# MT-MONITOR_V1_0_0.net
KiCad netlist of a schematic drawn in Altium Designer
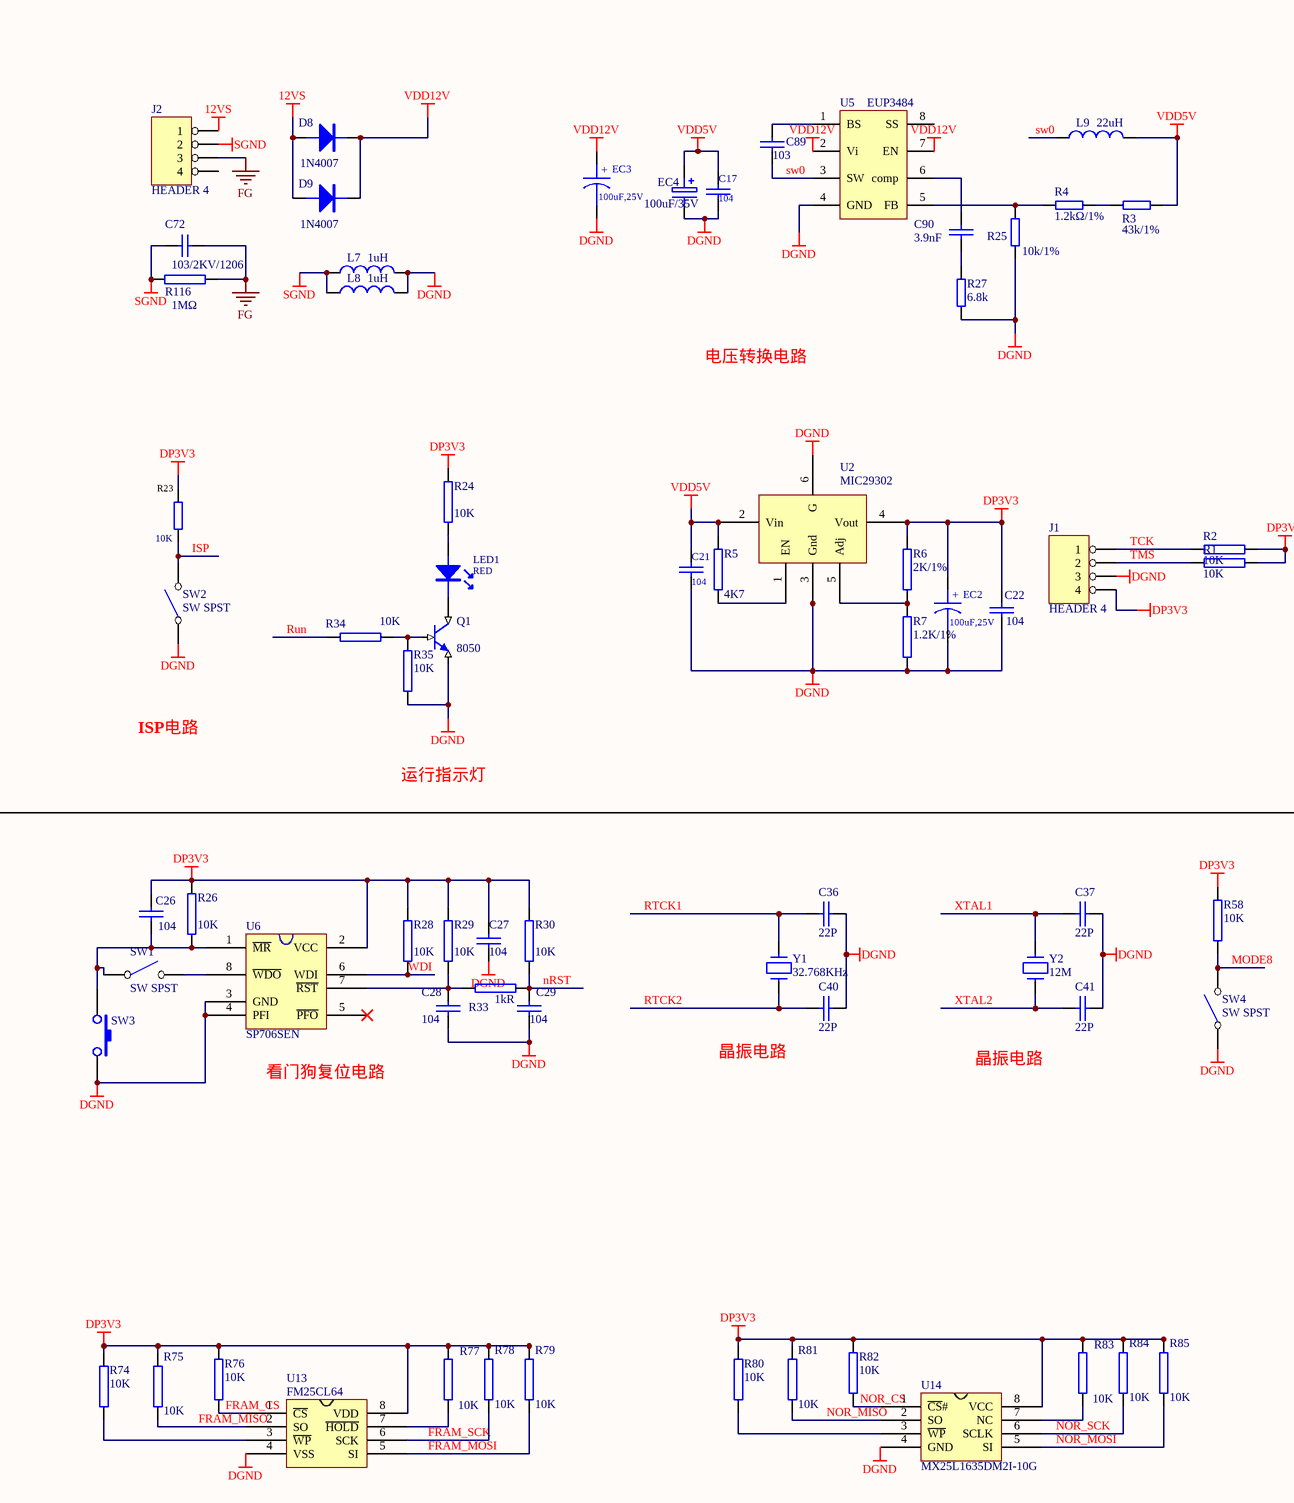
[diagram p0: MT-MONITOR V1.0.0.SchDoc, top left]
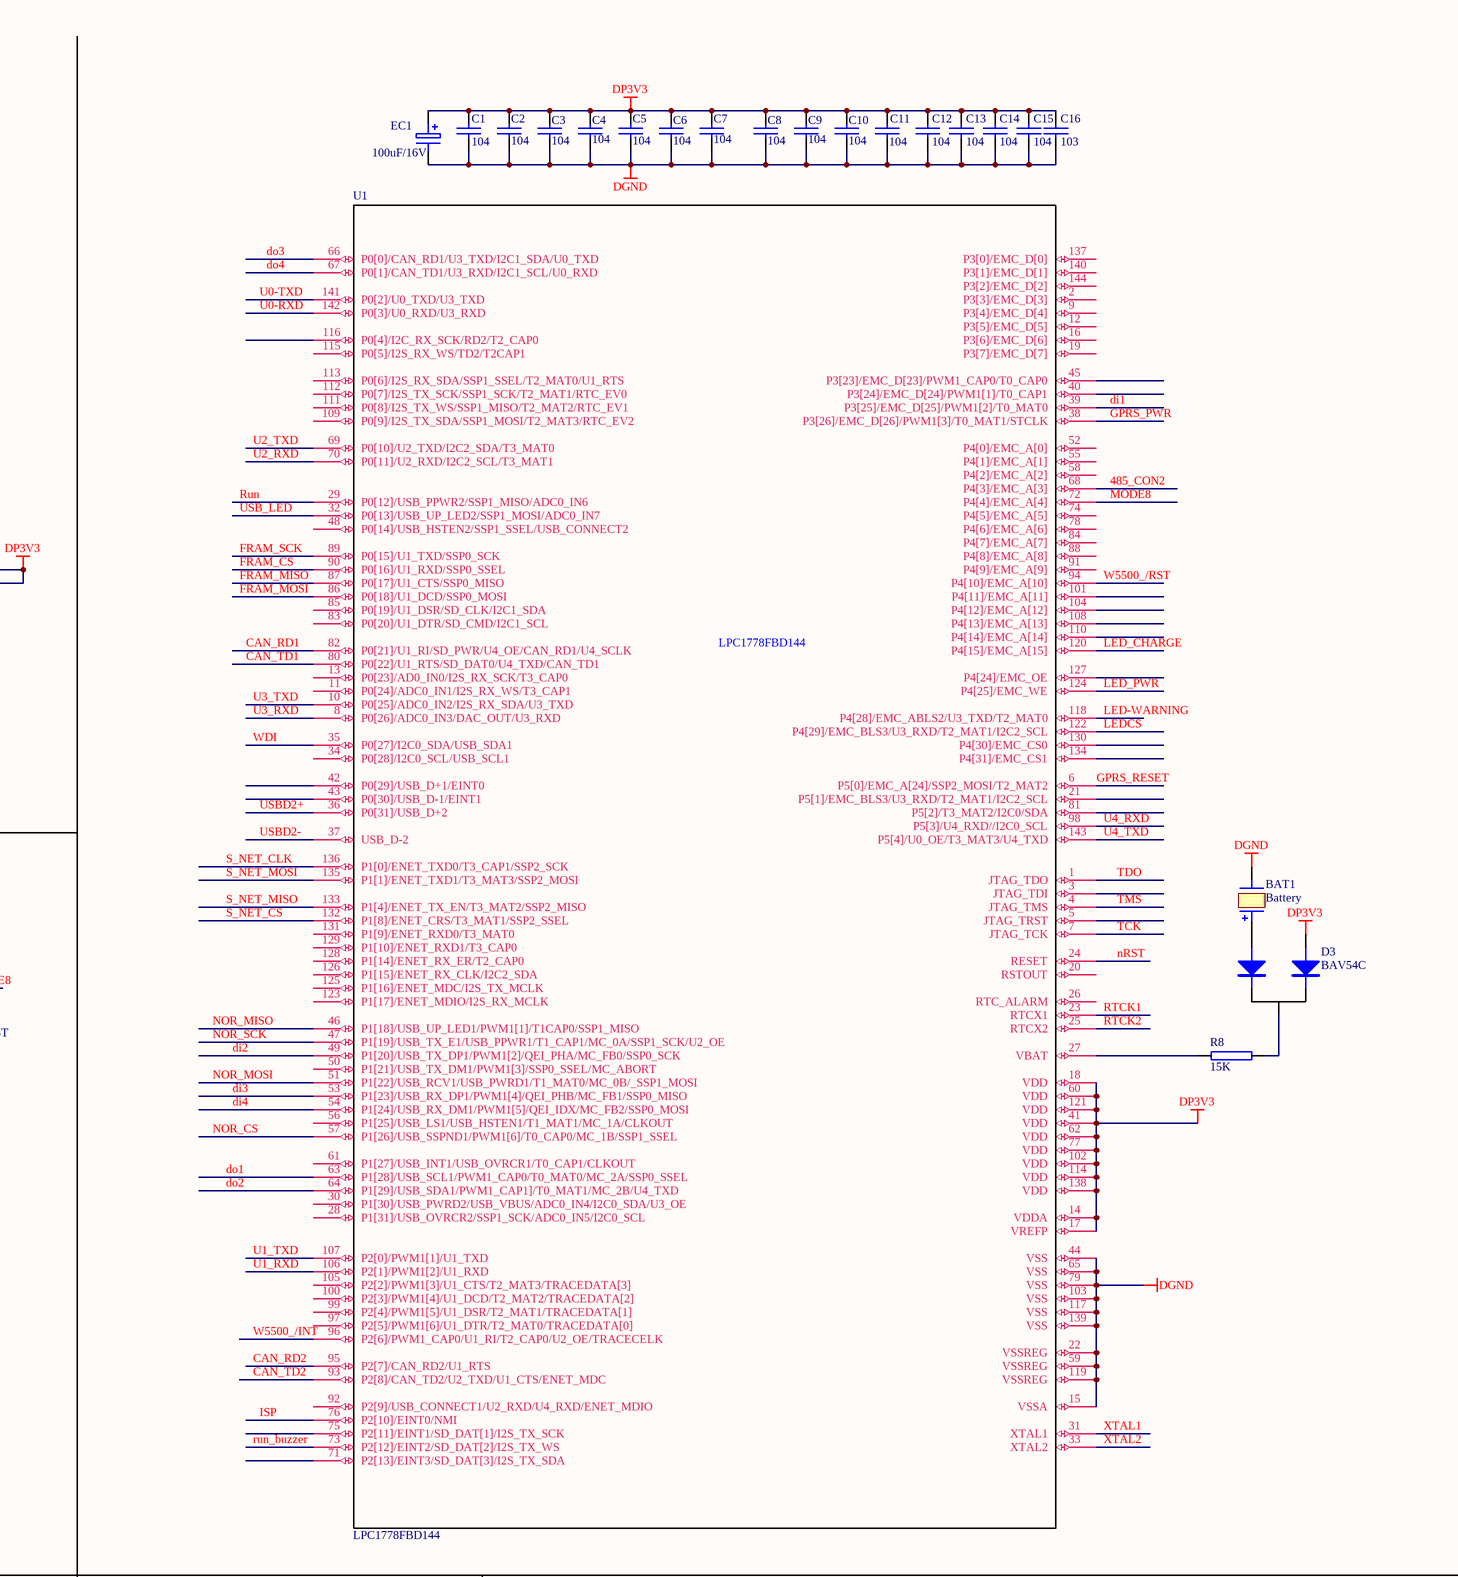
[diagram p1: MT-MONITOR V1.0.0.SchDoc, top middle]
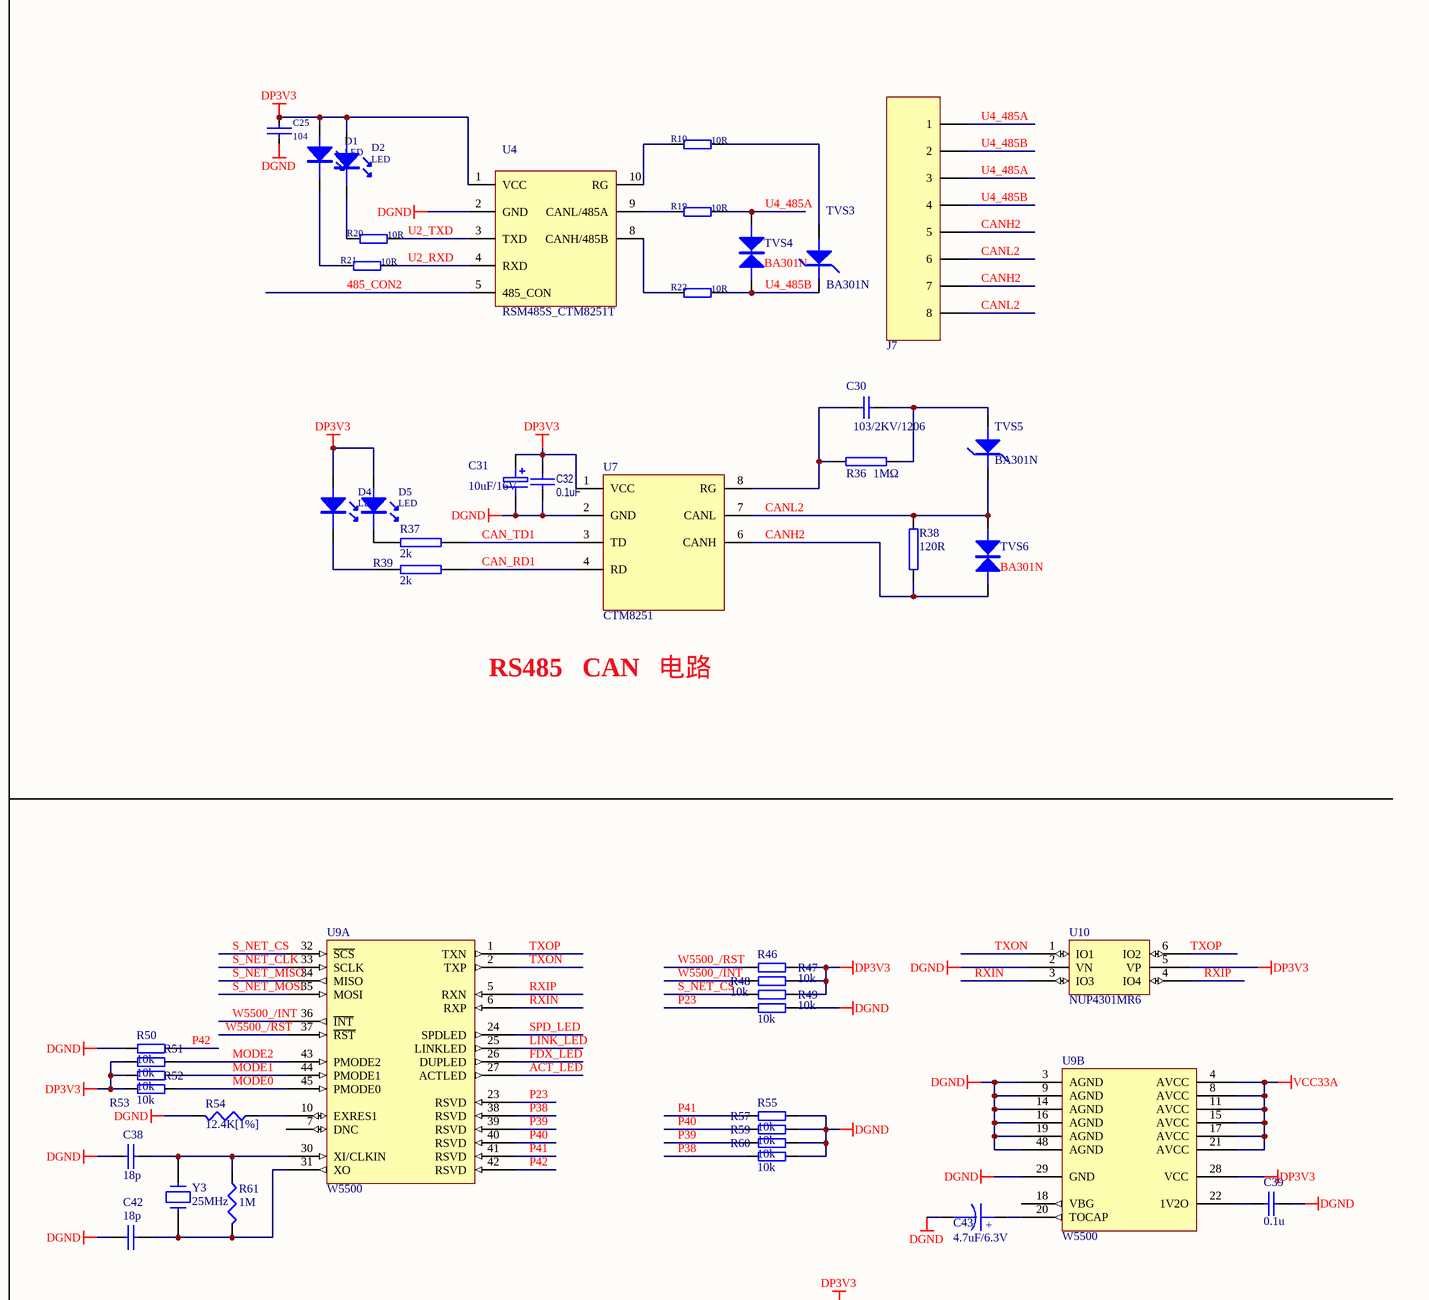
[diagram p2: MT-MONITOR V1.0.0.SchDoc, top right]
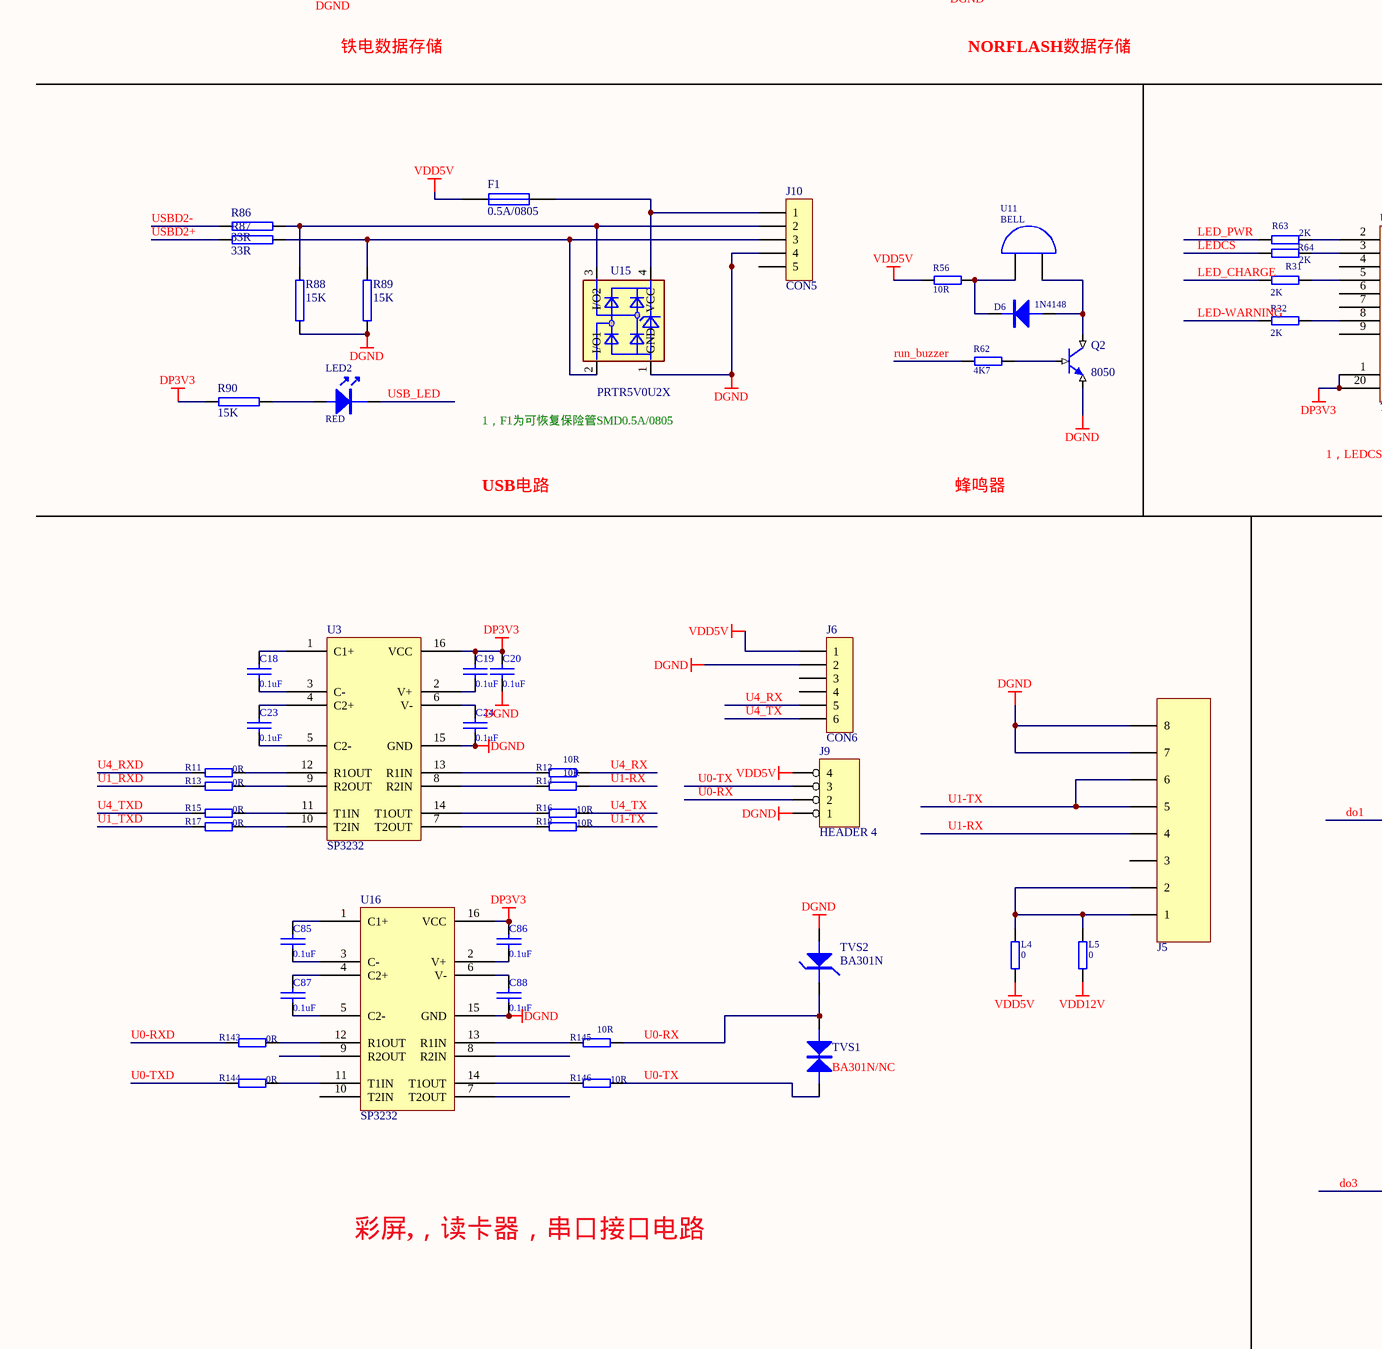
[diagram p3: MT-MONITOR V1.0.0.SchDoc, bottom left]
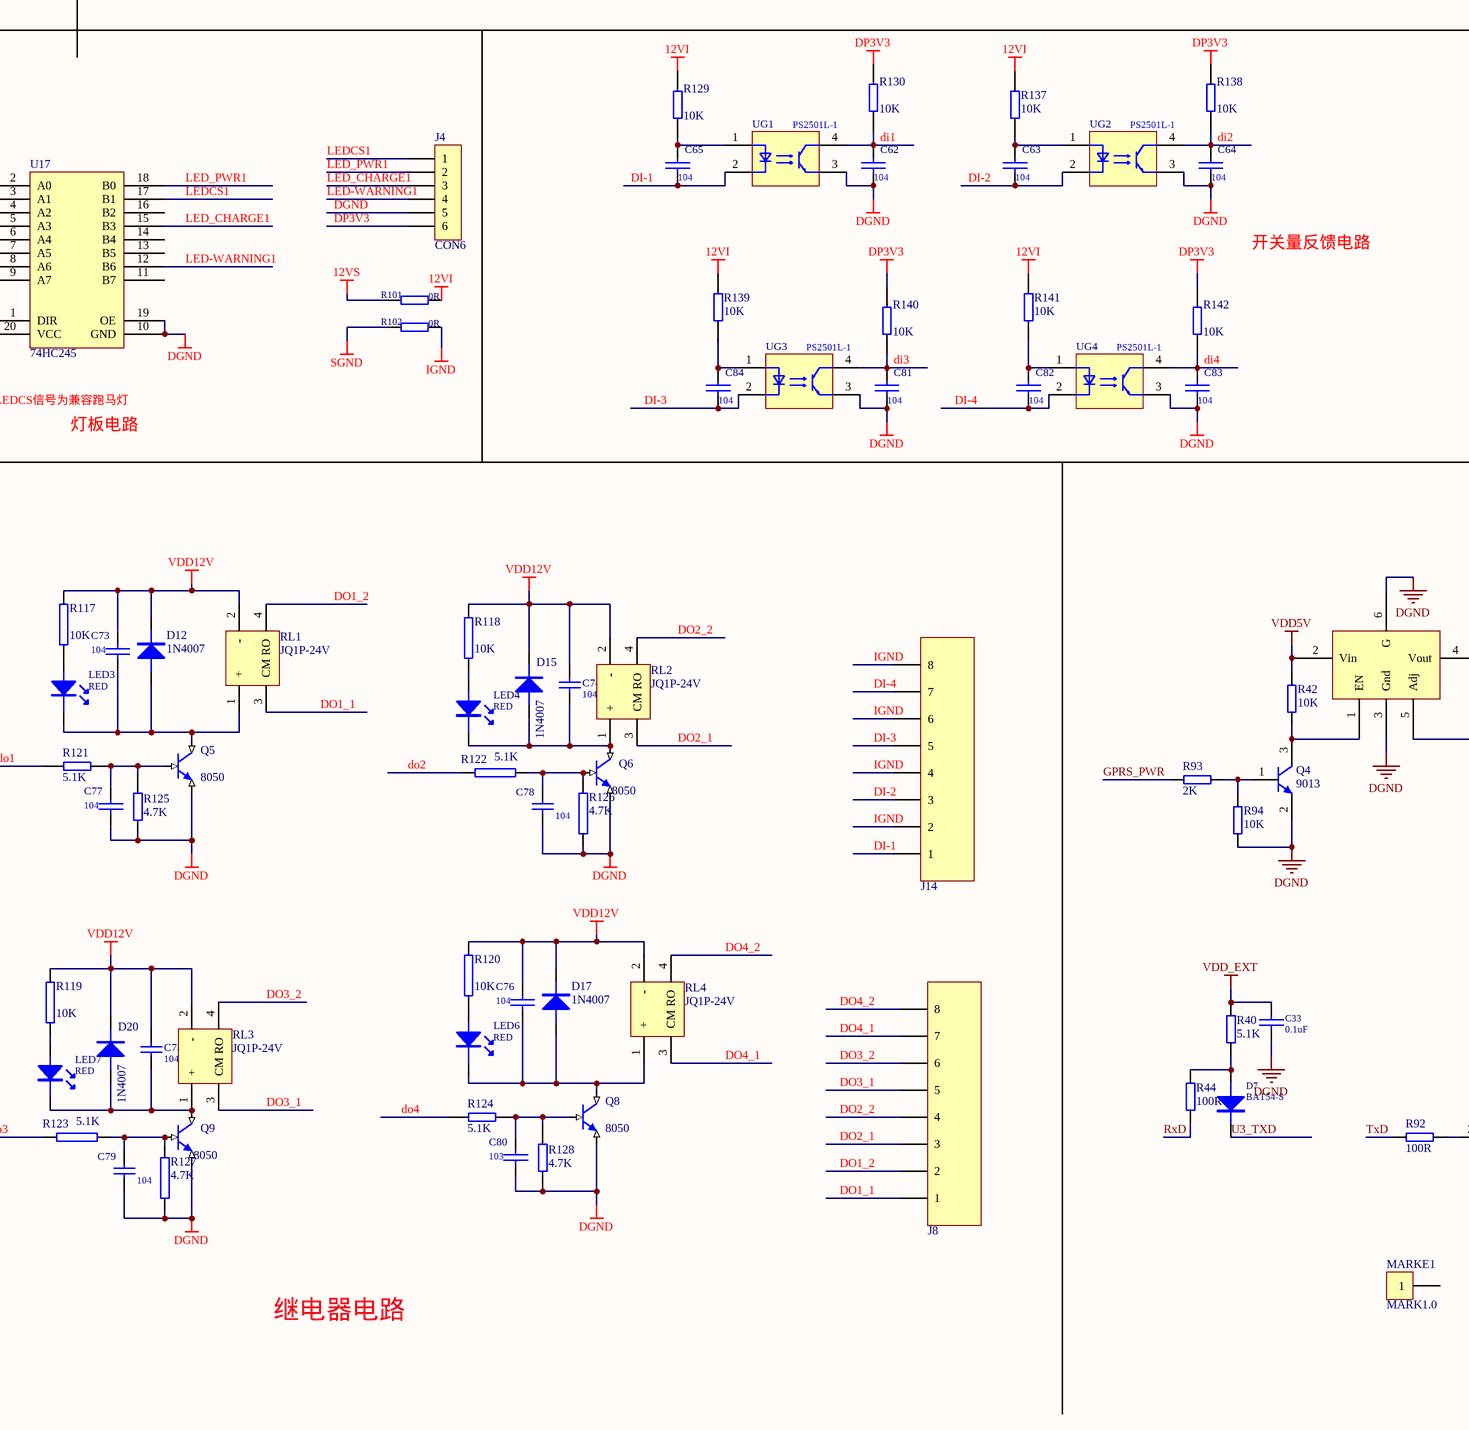
[diagram p4: MT-MONITOR V1.0.0.SchDoc, bottom middle]
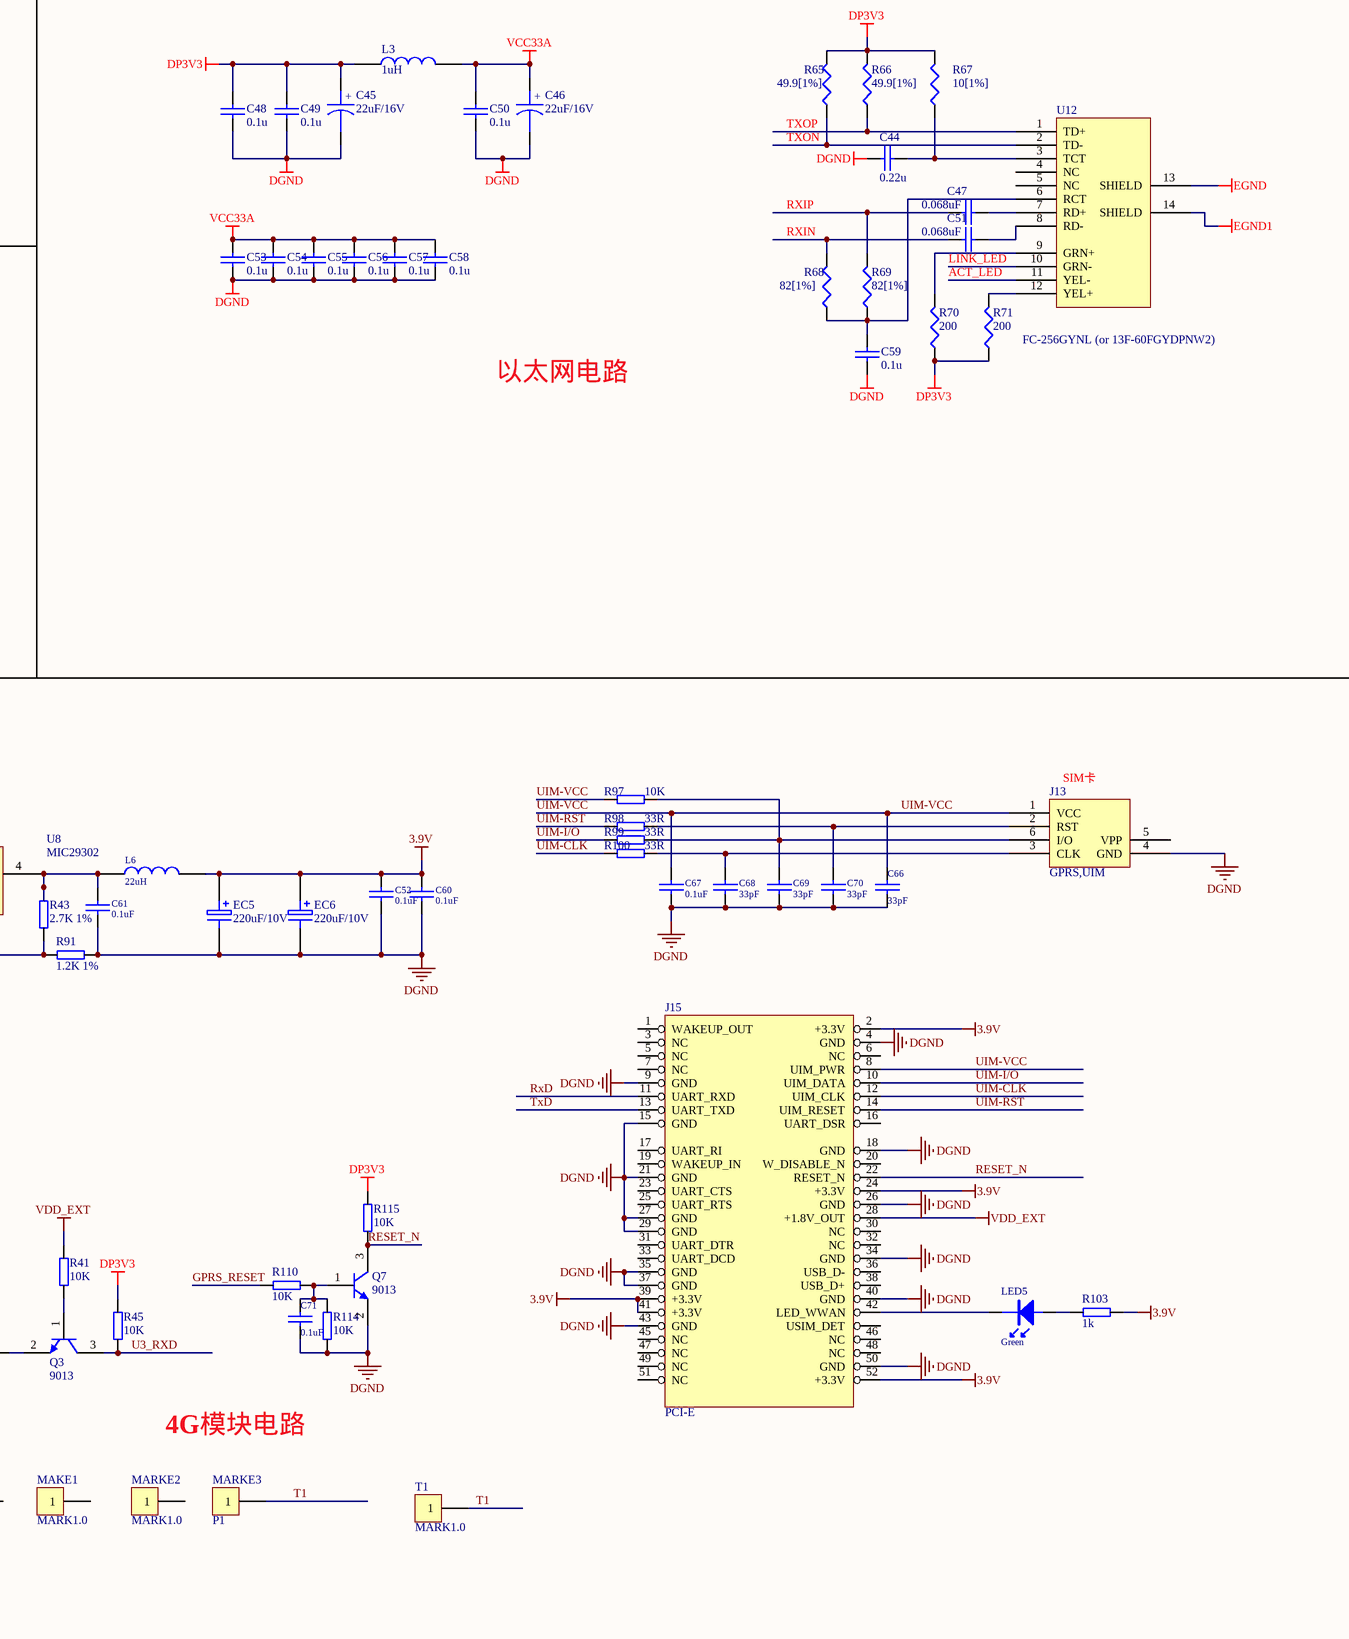
[diagram p5: MT-MONITOR V1.0.0.SchDoc, bottom right]

(export (version "E")
  (design (tool "Eeschema 10.0.6"))
  (components
    (comp (ref "BAT1") (value "Battery") (footprint "battery") (libsource (lib "MT") (part "Battery")))
    (comp (ref "C1") (value "104") (footprint "0603C") (libsource (lib "*") (part "CAP1")))
    (comp (ref "C2") (value "104") (footprint "0603C") (libsource (lib "*") (part "CAP1")))
    (comp (ref "C3") (value "104") (footprint "0603C") (libsource (lib "*") (part "CAP1")))
    (comp (ref "C4") (value "104") (footprint "0603C") (libsource (lib "*") (part "CAP1")))
    (comp (ref "C5") (value "104") (footprint "0603C") (libsource (lib "*") (part "CAP1")))
    (comp (ref "C6") (value "104") (footprint "0603C") (libsource (lib "*") (part "CAP1")))
    (comp (ref "C7") (value "104") (footprint "0603C") (libsource (lib "*") (part "CAP1")))
    (comp (ref "C8") (value "104") (footprint "0603C") (libsource (lib "*") (part "CAP1")))
    (comp (ref "C9") (value "104") (footprint "0603C") (libsource (lib "*") (part "CAP1")))
    (comp (ref "C10") (value "104") (footprint "0603C") (libsource (lib "*") (part "CAP1")))
    (comp (ref "C11") (value "104") (footprint "0603C") (libsource (lib "*") (part "CAP1")))
    (comp (ref "C12") (value "104") (footprint "0603C") (libsource (lib "") (part "CAP1_1")))
    (comp (ref "C13") (value "104") (footprint "0603C") (libsource (lib "*") (part "CAP1")))
    (comp (ref "C14") (value "104") (footprint "0603C") (libsource (lib "*") (part "CAP1")))
    (comp (ref "C15") (value "104") (footprint "0603C") (libsource (lib "*") (part "CAP1")))
    (comp (ref "C16") (value "103") (footprint "0603C") (libsource (lib "*") (part "CAP1")))
    (comp (ref "C17")
      (value "104")
      (footprint "0603C")
      (description "Capacitor")
      (libsource (lib "*") (part "CAP"))
    )
    (comp (ref "C18")
      (value "0.1uF")
      (footprint "0603C")
      (description "Capacitor")
      (libsource (lib "*") (part "CAP"))
    )
    (comp (ref "C19")
      (value "0.1uF")
      (footprint "0603C")
      (description "Capacitor")
      (libsource (lib "*") (part "CAP"))
    )
    (comp (ref "C20")
      (value "0.1uF")
      (footprint "0603C")
      (description "Capacitor")
      (libsource (lib "*") (part "CAP"))
    )
    (comp (ref "C21")
      (value "104")
      (footprint "0603C")
      (description "Capacitor")
      (libsource (lib "*") (part "CAP"))
    )
    (comp (ref "C22")
      (value "104")
      (footprint "0603C")
      (description "CAP")
      (libsource (lib "*") (part "CAP1"))
    )
    (comp (ref "C23")
      (value "0.1uF")
      (footprint "0603C")
      (description "Capacitor")
      (libsource (lib "*") (part "CAP"))
    )
    (comp (ref "C24")
      (value "0.1uF")
      (footprint "0603C")
      (description "Capacitor")
      (libsource (lib "*") (part "CAP"))
    )
    (comp (ref "C25") (value "104") (footprint "0603C") (libsource (lib "*") (part "CAP_1")))
    (comp (ref "C26")
      (value "104")
      (footprint "0603C")
      (description "CAP")
      (libsource (lib "*") (part "CAP1"))
    )
    (comp (ref "C27")
      (value "104")
      (footprint "0603C")
      (description "CAP")
      (libsource (lib "*") (part "CAP1"))
    )
    (comp (ref "C28")
      (value "104")
      (footprint "0603C")
      (description "CAP")
      (libsource (lib "*") (part "CAP1"))
    )
    (comp (ref "C29")
      (value "104")
      (footprint "0603C")
      (description "CAP")
      (libsource (lib "*") (part "CAP1"))
    )
    (comp (ref "C30")
      (value "103/2KV/1206")
      (footprint "1206C")
      (description "C0603")
      (fields (field (name "PUBLISHER") "*"))
      (libsource (lib "*") (part "0.1uF"))
    )
    (comp (ref "C31") (value "10uF/16V") (footprint "CA1206") (libsource (lib "*") (part "CAP2")))
    (comp (ref "C32")
      (value "0.1uF")
      (footprint "0603C")
      (description "Capacitor")
      (libsource (lib "*") (part "CAP"))
    )
    (comp (ref "C33")
      (value "0.1uF")
      (footprint "C0603")
      (description "CAP")
      (libsource (lib "MYSCHLIB") (part "CAP"))
    )
    (comp (ref "C36") (value "22P") (footprint "0603C") (libsource (lib "*") (part "CAP1")))
    (comp (ref "C37") (value "22P") (footprint "0603C") (libsource (lib "*") (part "CAP1")))
    (comp (ref "C38")
      (value "18p")
      (footprint "0603C")
      (description "Capacitor")
      (libsource (lib "*") (part "CAP"))
    )
    (comp (ref "C39")
      (value "0.1u")
      (footprint "0603C")
      (description "Capacitor")
      (libsource (lib "*") (part "CAP"))
    )
    (comp (ref "C40") (value "22P") (footprint "0603C") (libsource (lib "*") (part "CAP1")))
    (comp (ref "C41") (value "22P") (footprint "0603C") (libsource (lib "*") (part "CAP1")))
    (comp (ref "C42")
      (value "18p")
      (footprint "0603C")
      (description "Capacitor")
      (libsource (lib "*") (part "CAP"))
    )
    (comp (ref "C43")
      (value "4.7uF/6.3V")
      (footprint "CA1206")
      (description "Capacitor")
      (libsource (lib "*") (part "CAPACITOR POL"))
    )
    (comp (ref "C44")
      (value "0.22u")
      (footprint "0603C")
      (description "Capacitor")
      (libsource (lib "*") (part "CAP"))
    )
    (comp (ref "C45")
      (value "22uF/16V")
      (footprint "CA1206")
      (description "Capacitor")
      (libsource (lib "*") (part "CAPACITOR POL"))
    )
    (comp (ref "C46")
      (value "22uF/16V")
      (footprint "CA1206")
      (description "Capacitor")
      (libsource (lib "*") (part "CAPACITOR POL"))
    )
    (comp (ref "C47")
      (value "0.068uF")
      (footprint "0603C")
      (description "Capacitor")
      (libsource (lib "*") (part "CAP"))
    )
    (comp (ref "C48")
      (value "0.1u")
      (footprint "0603C")
      (description "Capacitor")
      (libsource (lib "*") (part "CAP"))
    )
    (comp (ref "C49")
      (value "0.1u")
      (footprint "0603C")
      (description "Capacitor")
      (libsource (lib "*") (part "CAP"))
    )
    (comp (ref "C50")
      (value "0.1u")
      (footprint "0603C")
      (description "Capacitor")
      (libsource (lib "*") (part "CAP"))
    )
    (comp (ref "C51")
      (value "0.068uF")
      (footprint "0603C")
      (description "Capacitor")
      (libsource (lib "*") (part "CAP"))
    )
    (comp (ref "C52")
      (value "0.1uF")
      (footprint "C0603")
      (description "CAP")
      (libsource (lib "MYSCHLIB") (part "CAP"))
    )
    (comp (ref "C53")
      (value "0.1u")
      (footprint "0603C")
      (description "Capacitor")
      (libsource (lib "*") (part "CAP"))
    )
    (comp (ref "C54")
      (value "0.1u")
      (footprint "0603C")
      (description "Capacitor")
      (libsource (lib "*") (part "CAP"))
    )
    (comp (ref "C55")
      (value "0.1u")
      (footprint "0603C")
      (description "Capacitor")
      (libsource (lib "*") (part "CAP"))
    )
    (comp (ref "C56")
      (value "0.1u")
      (footprint "0603C")
      (description "Capacitor")
      (libsource (lib "*") (part "CAP"))
    )
    (comp (ref "C57")
      (value "0.1u")
      (footprint "0603C")
      (description "Capacitor")
      (libsource (lib "*") (part "CAP"))
    )
    (comp (ref "C58")
      (value "0.1u")
      (footprint "0603C")
      (description "Capacitor")
      (libsource (lib "*") (part "CAP"))
    )
    (comp (ref "C59")
      (value "0.1u")
      (footprint "0603C")
      (description "Capacitor")
      (libsource (lib "*") (part "CAP"))
    )
    (comp (ref "C60")
      (value "0.1uF")
      (footprint "C0603")
      (description "CAP")
      (libsource (lib "MYSCHLIB") (part "CAP"))
    )
    (comp (ref "C61")
      (value "0.1uF")
      (footprint "C0603")
      (description "CAP")
      (libsource (lib "MYSCHLIB") (part "CAP"))
    )
    (comp (ref "C62")
      (value "104")
      (footprint "0603C")
      (description "Capacitor")
      (libsource (lib "*") (part "CAP"))
    )
    (comp (ref "C63")
      (value "104")
      (footprint "0603C")
      (description "Capacitor")
      (libsource (lib "*") (part "CAP"))
    )
    (comp (ref "C64")
      (value "104")
      (footprint "0603C")
      (description "Capacitor")
      (libsource (lib "*") (part "CAP"))
    )
    (comp (ref "C65")
      (value "104")
      (footprint "0603C")
      (description "Capacitor")
      (libsource (lib "*") (part "CAP"))
    )
    (comp (ref "C66")
      (value "33pF")
      (footprint "C0603")
      (description "CAP")
      (libsource (lib "MYSCHLIB") (part "CAP"))
    )
    (comp (ref "C67")
      (value "0.1uF")
      (footprint "C0603")
      (description "CAP")
      (libsource (lib "MYSCHLIB") (part "CAP"))
    )
    (comp (ref "C68")
      (value "33pF")
      (footprint "C0603")
      (description "CAP")
      (libsource (lib "MYSCHLIB") (part "CAP"))
    )
    (comp (ref "C69")
      (value "33pF")
      (footprint "C0603")
      (description "CAP")
      (libsource (lib "MYSCHLIB") (part "CAP"))
    )
    (comp (ref "C70")
      (value "33pF")
      (footprint "C0603")
      (description "CAP")
      (libsource (lib "MYSCHLIB") (part "CAP"))
    )
    (comp (ref "C71")
      (value "0.1uF")
      (footprint "C0603")
      (description "CAP")
      (libsource (lib "MYSCHLIB") (part "CAP"))
    )
    (comp (ref "C72")
      (value "103/2KV/1206")
      (footprint "1206C")
      (description "C0603")
      (fields (field (name "PUBLISHER") "*"))
      (libsource (lib "*") (part "0.1uF"))
    )
    (comp (ref "C73")
      (value "104")
      (footprint "0603C")
      (description "Capacitor")
      (libsource (lib "*") (part "CAP"))
    )
    (comp (ref "C74")
      (value "104")
      (footprint "0603C")
      (description "Capacitor")
      (fields (field (name "PUBLISHER") "*"))
      (libsource (lib "*") (part "Cap"))
    )
    (comp (ref "C75")
      (value "104")
      (footprint "0603C")
      (description "Capacitor")
      (fields (field (name "PUBLISHER") "*"))
      (libsource (lib "*") (part "Cap"))
    )
    (comp (ref "C76")
      (value "104")
      (footprint "0603C")
      (description "Capacitor")
      (libsource (lib "*") (part "CAP"))
    )
    (comp (ref "C77")
      (value "104")
      (footprint "0603C")
      (description "Capacitor")
      (libsource (lib "*") (part "CAP"))
    )
    (comp (ref "C78")
      (value "104")
      (footprint "0603C")
      (description "Capacitor")
      (fields (field (name "PUBLISHER") "*"))
      (libsource (lib "*") (part "Cap"))
    )
    (comp (ref "C79")
      (value "104")
      (footprint "0603C")
      (description "Capacitor")
      (fields (field (name "PUBLISHER") "*"))
      (libsource (lib "*") (part "Cap"))
    )
    (comp (ref "C80")
      (value "103")
      (footprint "0603C")
      (description "Capacitor")
      (libsource (lib "*") (part "CAP"))
    )
    (comp (ref "C81")
      (value "104")
      (footprint "0603C")
      (description "Capacitor")
      (libsource (lib "*") (part "CAP"))
    )
    (comp (ref "C82")
      (value "104")
      (footprint "0603C")
      (description "Capacitor")
      (libsource (lib "*") (part "CAP"))
    )
    (comp (ref "C83")
      (value "104")
      (footprint "0603C")
      (description "Capacitor")
      (libsource (lib "*") (part "CAP"))
    )
    (comp (ref "C84")
      (value "104")
      (footprint "0603C")
      (description "Capacitor")
      (libsource (lib "*") (part "CAP"))
    )
    (comp (ref "C85")
      (value "0.1uF")
      (footprint "0603C")
      (description "Capacitor")
      (libsource (lib "*") (part "CAP"))
    )
    (comp (ref "C86")
      (value "0.1uF")
      (footprint "0603C")
      (description "Capacitor")
      (libsource (lib "*") (part "CAP"))
    )
    (comp (ref "C87")
      (value "0.1uF")
      (footprint "0603C")
      (description "Capacitor")
      (libsource (lib "*") (part "CAP"))
    )
    (comp (ref "C88")
      (value "0.1uF")
      (footprint "0603C")
      (description "Capacitor")
      (libsource (lib "*") (part "CAP"))
    )
    (comp (ref "C89") (value "103") (footprint "0603C") (libsource (lib "*") (part "CAP")))
    (comp (ref "C90") (value "3.9nF") (footprint "0603C") (libsource (lib "*") (part "CAP")))
    (comp (ref "D1") (value "LED") (footprint "D0805") (libsource (lib "*") (part "LED")))
    (comp (ref "D2") (value "LED") (footprint "D0805") (libsource (lib "*") (part "LED")))
    (comp (ref "D3") (value "BAV54C") (footprint "SOT23") (libsource (lib "MT") (part "BAV54C")))
    (comp (ref "D4") (value "LED") (footprint "D0805") (libsource (lib "*") (part "LED")))
    (comp (ref "D5") (value "LED") (footprint "D0805") (libsource (lib "*") (part "LED")))
    (comp (ref "D6") (value "1N4148") (footprint "1206D") (libsource (lib "*") (part "DIODE")))
    (comp (ref "D7") (value "BAT54-S") (footprint "SOT23") (libsource (lib "MYSCHLIB") (part "DIODE")))
    (comp (ref "D8") (value "1N4007") (footprint "1206D") (libsource (lib "*") (part "DIODE")))
    (comp (ref "D9") (value "1N4007") (footprint "1206D") (libsource (lib "*") (part "DIODE")))
    (comp (ref "D12") (value "1N4007") (footprint "1206D") (libsource (lib "*") (part "DIODE")))
    (comp (ref "D15") (value "1N4007") (footprint "1206D") (libsource (lib "*") (part "DIODE")))
    (comp (ref "D17") (value "1N4007") (footprint "1206D") (libsource (lib "*") (part "DIODE")))
    (comp (ref "D20") (value "1N4007") (footprint "1206D") (libsource (lib "*") (part "DIODE")))
    (comp (ref "EC1") (value "100uF/16V") (footprint "C100UF16VEJ") (libsource (lib "*") (part "CAP2")))
    (comp (ref "EC2")
      (value "100uF,25V")
      (footprint "C100UF16VEJ")
      (description "Capacitor")
      (libsource (lib "*") (part "CAPACITOR POL"))
    )
    (comp (ref "EC3")
      (value "100uF,25V")
      (footprint "C100UF16VEJ")
      (description "Capacitor")
      (libsource (lib "*") (part "CAPACITOR POL"))
    )
    (comp (ref "EC4") (value "100uF/35V") (footprint "C100UF16VEJ") (libsource (lib "*") (part "CAP2")))
    (comp (ref "EC5")
      (value "220uF/10V")
      (footprint "C100UF16V")
      (libsource (lib "MYSCHLIB") (part "ELECTRO2"))
    )
    (comp (ref "EC6")
      (value "220uF/10V")
      (footprint "C100UF16V")
      (libsource (lib "MYSCHLIB") (part "ELECTRO2"))
    )
    (comp (ref "F1")
      (value "0.5A/0805")
      (footprint "0805R")
      (description "Fuse")
      (libsource (lib "EasyCortex M3-1752") (part "FUSE1"))
    )
    (comp (ref "J1")
      (value "HEADER 4")
      (footprint "COM-2.54mm-90")
      (description "4 Pin Header")
      (libsource (lib "") (part "4 HEADER_1"))
    )
    (comp (ref "J2")
      (value "HEADER 4")
      (footprint "KF2EDG-4P-3.81mm")
      (description "4 Pin Header")
      (libsource (lib "") (part "4 HEADER_1"))
    )
    (comp (ref "J4")
      (value "CON6")
      (footprint "CON6-2.54mm-90")
      (description "Connector")
      (libsource (lib "*") (part "CON6"))
    )
    (comp (ref "J5") (value "CON8") (footprint "HY-8A-2.00mm") (libsource (lib "ueee20160531") (part "CON8")))
    (comp (ref "J6")
      (value "CON6")
      (footprint "CON6-2.54mm-90")
      (description "Connector")
      (libsource (lib "*") (part "CON6"))
    )
    (comp (ref "J7") (value "CON8") (footprint "KF2EDG-8P-3.81mm") (libsource (lib "直流原理图库") (part "CON8")))
    (comp (ref "J8") (value "CON8") (footprint "KF2EDG-8P-3.81mm") (libsource (lib "") (part "CON8_1")))
    (comp (ref "J9")
      (value "HEADER 4")
      (footprint "KF2EDG-4P-3.81mm")
      (description "4 Pin Header")
      (libsource (lib "直流原理图库") (part "4 HEADER"))
    )
    (comp (ref "J10")
      (value "CON5")
      (footprint "USB-A")
      (description "Connector")
      (libsource (lib "*") (part "CON5"))
    )
    (comp (ref "J13") (value "GPRS,UIM") (footprint "SIM6-AUTO") (libsource (lib "MYSCHLIB") (part "UIM6")))
    (comp (ref "J14") (value "CON8") (footprint "KF2EDG-8P-3.81mm") (libsource (lib "") (part "CON8_1")))
    (comp (ref "J15") (value "PCI-E") (footprint "MC2716") (libsource (lib "直流原理图库") (part "PCI-E")))
    (comp (ref "L3") (value "1uH") (footprint "0805R") (libsource (lib "") (part "INDUCTOR_1")))
    (comp (ref "L4")
      (value "0")
      (footprint "CON02_2.54")
      (description "RES")
      (libsource (lib "*") (part "RES-1"))
    )
    (comp (ref "L5")
      (value "0")
      (footprint "CON02_2.54")
      (description "RES")
      (libsource (lib "*") (part "RES-1"))
    )
    (comp (ref "L6") (value "22uH") (footprint "LC7*7*3_L") (libsource (lib "MYSCHLIB") (part "INDUCTOR")))
    (comp (ref "L7") (value "1uH") (footprint "1206R") (libsource (lib "*") (part "INDUCTOR")))
    (comp (ref "L8") (value "1uH") (footprint "1206R") (libsource (lib "*") (part "INDUCTOR")))
    (comp (ref "L9") (value "22uH") (footprint "LC7*7*3_L") (libsource (lib "*") (part "INDUCTOR")))
    (comp (ref "LED1") (value "RED") (footprint "D0805") (libsource (lib "*") (part "LED")))
    (comp (ref "LED2") (value "RED") (footprint "D0805") (libsource (lib "*") (part "LED")))
    (comp (ref "LED3") (value "RED") (footprint "D0805") (libsource (lib "*") (part "LED")))
    (comp (ref "LED4") (value "RED") (footprint "D0805") (libsource (lib "*") (part "LED")))
    (comp (ref "LED5") (value "Green") (footprint "D0805") (libsource (lib "MYSCHLIB") (part "LED")))
    (comp (ref "LED6") (value "RED") (footprint "D0805") (libsource (lib "*") (part "LED")))
    (comp (ref "LED7") (value "RED") (footprint "D0805") (libsource (lib "*") (part "LED")))
    (comp (ref "MAKE1")
      (value "MARK1.0")
      (footprint "MARK1.0")
      (description "Connector")
      (libsource (lib "*") (part "CON1"))
    )
    (comp (ref "MARKE1")
      (value "MARK1.0")
      (footprint "MARK1.0")
      (description "Connector")
      (libsource (lib "*") (part "CON1"))
    )
    (comp (ref "MARKE2")
      (value "MARK1.0")
      (footprint "MARK1.0")
      (description "Connector")
      (libsource (lib "*") (part "CON1"))
    )
    (comp (ref "MARKE3")
      (value "P1")
      (footprint "IPEX")
      (description "Connector")
      (libsource (lib "*") (part "CON1"))
    )
    (comp (ref "Q1") (value "8050") (footprint "SOT23") (libsource (lib "*") (part "NPN")))
    (comp (ref "Q2") (value "8050") (footprint "SOT23") (libsource (lib "*") (part "NPN")))
    (comp (ref "Q3") (value "9013") (footprint "SOT23") (libsource (lib "MYSCHLIB") (part "NPN")))
    (comp (ref "Q4") (value "9013") (footprint "SOT23") (libsource (lib "MYSCHLIB") (part "NPN")))
    (comp (ref "Q5") (value "8050") (footprint "SOT23") (libsource (lib "*") (part "NPN")))
    (comp (ref "Q6") (value "8050") (footprint "SOT23") (libsource (lib "*") (part "NPN")))
    (comp (ref "Q7") (value "9013") (footprint "SOT23") (libsource (lib "MYSCHLIB") (part "NPN")))
    (comp (ref "Q8") (value "8050") (footprint "SOT23") (libsource (lib "*") (part "NPN")))
    (comp (ref "Q9") (value "8050") (footprint "SOT23") (libsource (lib "*") (part "NPN")))
    (comp (ref "R1") (value "10K") (footprint "0603R") (libsource (lib "*") (part "RES1")))
    (comp (ref "R2") (value "10K") (footprint "0603R") (libsource (lib "*") (part "RES1")))
    (comp (ref "R3") (value "43k/1%") (footprint "0603R") (libsource (lib "*") (part "R_S")))
    (comp (ref "R4") (value "1.2kΩ/1%") (footprint "0603R") (libsource (lib "*") (part "R_S")))
    (comp (ref "R5") (value "4K7") (footprint "0603R") (libsource (lib "*") (part "RES1")))
    (comp (ref "R6") (value "2K/1%") (footprint "0603R") (libsource (lib "*") (part "RES1")))
    (comp (ref "R7") (value "1.2K/1%") (footprint "0603R") (libsource (lib "*") (part "RES1")))
    (comp (ref "R8") (value "15K") (footprint "0603R") (libsource (lib "*") (part "RES1")))
    (comp (ref "R10")
      (value "10R")
      (footprint "0603R")
      (description "RES")
      (libsource (lib "*") (part "RES-1"))
    )
    (comp (ref "R11")
      (value "0R")
      (footprint "0603R")
      (description "RES")
      (libsource (lib "*") (part "RES-1"))
    )
    (comp (ref "R12")
      (value "10R")
      (footprint "0603R")
      (description "RES")
      (libsource (lib "*") (part "RES-1"))
    )
    (comp (ref "R13")
      (value "0R")
      (footprint "0603R")
      (description "RES")
      (libsource (lib "*") (part "RES-1"))
    )
    (comp (ref "R14")
      (value "10R")
      (footprint "0603R")
      (description "RES")
      (libsource (lib "*") (part "RES-1"))
    )
    (comp (ref "R15")
      (value "0R")
      (footprint "0603R")
      (description "RES")
      (libsource (lib "*") (part "RES-1"))
    )
    (comp (ref "R16")
      (value "10R")
      (footprint "0603R")
      (description "RES")
      (libsource (lib "*") (part "RES-1"))
    )
    (comp (ref "R17")
      (value "0R")
      (footprint "0603R")
      (description "RES")
      (libsource (lib "*") (part "RES-1"))
    )
    (comp (ref "R18")
      (value "10R")
      (footprint "0603R")
      (description "RES")
      (libsource (lib "*") (part "RES-1"))
    )
    (comp (ref "R19")
      (value "10R")
      (footprint "0603R")
      (description "RES")
      (libsource (lib "*") (part "RES-1"))
    )
    (comp (ref "R20")
      (value "10R")
      (footprint "0603R")
      (description "RES")
      (libsource (lib "*") (part "RES-1"))
    )
    (comp (ref "R21")
      (value "10R")
      (footprint "0603R")
      (description "RES")
      (libsource (lib "*") (part "RES-1"))
    )
    (comp (ref "R22")
      (value "10R")
      (footprint "0603R")
      (description "RES")
      (libsource (lib "*") (part "RES-1"))
    )
    (comp (ref "R23")
      (value "10K")
      (footprint "0603R")
      (description "RES")
      (libsource (lib "*") (part "RES-1"))
    )
    (comp (ref "R24") (value "10K") (footprint "0603R") (libsource (lib "*") (part "RES1")))
    (comp (ref "R25") (value "10k/1%") (footprint "0603R") (libsource (lib "*") (part "R_S")))
    (comp (ref "R26") (value "10K") (footprint "0603R") (libsource (lib "*") (part "RES1")))
    (comp (ref "R27") (value "6.8k") (footprint "0603R") (libsource (lib "*") (part "R_S")))
    (comp (ref "R28") (value "10K") (footprint "0603R") (libsource (lib "*") (part "RES1")))
    (comp (ref "R29") (value "10K") (footprint "0603R") (libsource (lib "*") (part "RES1")))
    (comp (ref "R30") (value "10K") (footprint "0603R") (libsource (lib "*") (part "RES1")))
    (comp (ref "R31")
      (value "2K")
      (footprint "0603R")
      (description "RES")
      (libsource (lib "*") (part "RES-1"))
    )
    (comp (ref "R32")
      (value "2K")
      (footprint "0603R")
      (description "RES")
      (libsource (lib "*") (part "RES-1"))
    )
    (comp (ref "R33") (value "1kR") (footprint "0603R") (libsource (lib "*") (part "RES1")))
    (comp (ref "R34") (value "10K") (footprint "0603R") (libsource (lib "*") (part "RES1")))
    (comp (ref "R35") (value "10K") (footprint "0603R") (libsource (lib "*") (part "RES1")))
    (comp (ref "R36")
      (value "1MΩ")
      (footprint "1206R")
      (fields (field (name "Comment") "1M"))
      (libsource (lib "") (part "RES2_1"))
    )
    (comp (ref "R37") (value "2k") (footprint "0603R") (libsource (lib "*") (part "RES2")))
    (comp (ref "R38") (value "120R") (footprint "1206R") (libsource (lib "") (part "RES2_1")))
    (comp (ref "R39") (value "2k") (footprint "0603R") (libsource (lib "*") (part "RES2")))
    (comp (ref "R40") (value "5.1K") (footprint "R0603") (libsource (lib "MYSCHLIB") (part "RES")))
    (comp (ref "R41") (value "10K") (footprint "R0603") (libsource (lib "MYSCHLIB") (part "RES")))
    (comp (ref "R42") (value "10K") (footprint "R0603") (libsource (lib "MYSCHLIB") (part "RES")))
    (comp (ref "R43") (value "2.7K 1%") (footprint "R0603") (libsource (lib "MYSCHLIB") (part "RES")))
    (comp (ref "R44") (value "100R") (footprint "R0603") (libsource (lib "MYSCHLIB") (part "RES")))
    (comp (ref "R45") (value "10K") (footprint "R0603") (libsource (lib "MYSCHLIB") (part "RES")))
    (comp (ref "R46")
      (value "10k")
      (footprint "0603R")
      (description "RES")
      (libsource (lib "*") (part "RES-1"))
    )
    (comp (ref "R47")
      (value "10k")
      (footprint "0603R")
      (description "RES")
      (libsource (lib "*") (part "RES-1"))
    )
    (comp (ref "R48")
      (value "10k")
      (footprint "0603R")
      (description "RES")
      (libsource (lib "*") (part "RES-1"))
    )
    (comp (ref "R49")
      (value "10k")
      (footprint "0603R")
      (description "RES")
      (libsource (lib "*") (part "RES-1"))
    )
    (comp (ref "R50")
      (value "10k")
      (footprint "0603R")
      (description "RES")
      (libsource (lib "*") (part "RES-1"))
    )
    (comp (ref "R51")
      (value "10k")
      (footprint "0603R")
      (description "RES")
      (libsource (lib "*") (part "RES-1"))
    )
    (comp (ref "R52")
      (value "10k")
      (footprint "0603R")
      (description "RES")
      (libsource (lib "*") (part "RES-1"))
    )
    (comp (ref "R53")
      (value "10k")
      (footprint "0603R")
      (description "RES")
      (libsource (lib "*") (part "RES-1"))
    )
    (comp (ref "R54") (value "12.4K[1%]") (footprint "0603R") (libsource (lib "") (part "RES1_2")))
    (comp (ref "R55")
      (value "10k")
      (footprint "0603R")
      (description "RES")
      (libsource (lib "*") (part "RES-1"))
    )
    (comp (ref "R56")
      (value "10R")
      (footprint "0603R")
      (description "RES")
      (libsource (lib "*") (part "RES-1"))
    )
    (comp (ref "R57")
      (value "10k")
      (footprint "0603R")
      (description "RES")
      (libsource (lib "*") (part "RES-1"))
    )
    (comp (ref "R58") (value "10K") (footprint "0603R") (libsource (lib "*") (part "RES1")))
    (comp (ref "R59")
      (value "10k")
      (footprint "0603R")
      (description "RES")
      (libsource (lib "*") (part "RES-1"))
    )
    (comp (ref "R60")
      (value "10k")
      (footprint "0603R")
      (description "RES")
      (libsource (lib "*") (part "RES-1"))
    )
    (comp (ref "R61") (value "1M") (footprint "0603R") (libsource (lib "") (part "RES1_2")))
    (comp (ref "R62")
      (value "4K7")
      (footprint "0603R")
      (description "RES")
      (libsource (lib "*") (part "RES-1"))
    )
    (comp (ref "R63")
      (value "2K")
      (footprint "0603R")
      (description "RES")
      (libsource (lib "*") (part "RES-1"))
    )
    (comp (ref "R64")
      (value "2K")
      (footprint "0603R")
      (description "RES")
      (libsource (lib "*") (part "RES-1"))
    )
    (comp (ref "R65") (value "49.9[1%]") (footprint "0603R") (libsource (lib "") (part "RES1_2")))
    (comp (ref "R66") (value "49.9[1%]") (footprint "0603R") (libsource (lib "") (part "RES1_2")))
    (comp (ref "R67") (value "10[1%]") (footprint "0603R") (libsource (lib "") (part "RES1_2")))
    (comp (ref "R68") (value "82[1%]") (footprint "0603R") (libsource (lib "") (part "RES1_2")))
    (comp (ref "R69") (value "82[1%]") (footprint "0603R") (libsource (lib "") (part "RES1_2")))
    (comp (ref "R70") (value "200") (footprint "0603R") (libsource (lib "") (part "RES1_2")))
    (comp (ref "R71") (value "200") (footprint "0603R") (libsource (lib "") (part "RES1_2")))
    (comp (ref "R74") (value "10K") (footprint "0603R") (libsource (lib "UEEE160329") (part "RES1")))
    (comp (ref "R75") (value "10K") (footprint "0603R") (libsource (lib "UEEE160329") (part "RES1")))
    (comp (ref "R76") (value "10K") (footprint "0603R") (libsource (lib "UEEE160329") (part "RES1")))
    (comp (ref "R77") (value "10K") (footprint "0603R") (libsource (lib "UEEE160329") (part "RES1")))
    (comp (ref "R78") (value "10K") (footprint "0603R") (libsource (lib "UEEE160329") (part "RES1")))
    (comp (ref "R79") (value "10K") (footprint "0603R") (libsource (lib "UEEE160329") (part "RES1")))
    (comp (ref "R80") (value "10K") (footprint "0603R") (libsource (lib "UEEE160329") (part "RES1")))
    (comp (ref "R81") (value "10K") (footprint "0603R") (libsource (lib "UEEE160329") (part "RES1")))
    (comp (ref "R82") (value "10K") (footprint "0603R") (libsource (lib "UEEE160329") (part "RES1")))
    (comp (ref "R83") (value "10K") (footprint "0603R") (libsource (lib "UEEE160329") (part "RES1")))
    (comp (ref "R84") (value "10K") (footprint "0603R") (libsource (lib "UEEE160329") (part "RES1")))
    (comp (ref "R85") (value "10K") (footprint "0603R") (libsource (lib "UEEE160329") (part "RES1")))
    (comp (ref "R86") (value "33R") (footprint "0603R") (libsource (lib "UEEE160329") (part "RES2")))
    (comp (ref "R87") (value "33R") (footprint "0603R") (libsource (lib "UEEE160329") (part "RES2")))
    (comp (ref "R88") (value "15K") (footprint "0603R") (libsource (lib "UEEE160329") (part "RES2")))
    (comp (ref "R89") (value "15K") (footprint "0603R") (libsource (lib "UEEE160329") (part "RES2")))
    (comp (ref "R90") (value "15K") (footprint "0603R") (libsource (lib "UEEE160329") (part "RES2")))
    (comp (ref "R91") (value "1.2K 1%") (footprint "R0603") (libsource (lib "MYSCHLIB") (part "RES")))
    (comp (ref "R92") (value "100R") (footprint "R0603") (libsource (lib "MYSCHLIB") (part "RES")))
    (comp (ref "R93") (value "2K") (footprint "R0603") (libsource (lib "MYSCHLIB") (part "RES")))
    (comp (ref "R94") (value "10K") (footprint "R0603") (libsource (lib "MYSCHLIB") (part "RES")))
    (comp (ref "R97") (value "10K") (footprint "R0603") (libsource (lib "MYSCHLIB") (part "RES")))
    (comp (ref "R98") (value "33R") (footprint "R0603") (libsource (lib "MYSCHLIB") (part "RES")))
    (comp (ref "R99") (value "33R") (footprint "R0603") (libsource (lib "MYSCHLIB") (part "RES")))
    (comp (ref "R100") (value "33R") (footprint "R0603") (libsource (lib "MYSCHLIB") (part "RES")))
    (comp (ref "R101")
      (value "0R")
      (footprint "0603R")
      (description "RES")
      (libsource (lib "*") (part "RES-1"))
    )
    (comp (ref "R102")
      (value "0R")
      (footprint "0603R")
      (description "RES")
      (libsource (lib "*") (part "RES-1"))
    )
    (comp (ref "R103") (value "1k") (footprint "R0603") (libsource (lib "MYSCHLIB") (part "RES")))
    (comp (ref "R110") (value "10K") (footprint "R0603") (libsource (lib "MYSCHLIB") (part "RES")))
    (comp (ref "R114") (value "10K") (footprint "R0603") (libsource (lib "MYSCHLIB") (part "RES")))
    (comp (ref "R115") (value "10K") (footprint "R0603") (libsource (lib "MYSCHLIB") (part "RES")))
    (comp (ref "R116")
      (value "1MΩ")
      (footprint "1206R")
      (fields (field (name "Comment") "1M"))
      (libsource (lib "") (part "RES2_1"))
    )
    (comp (ref "R117") (value "10K") (footprint "0603R") (libsource (lib "*") (part "RES1")))
    (comp (ref "R118") (value "10K") (footprint "0603R") (libsource (lib "*") (part "RES1")))
    (comp (ref "R119") (value "10K") (footprint "0603R") (libsource (lib "*") (part "RES1")))
    (comp (ref "R120") (value "10K") (footprint "0603R") (libsource (lib "*") (part "RES1")))
    (comp (ref "R121") (value "5.1K") (footprint "0603R") (libsource (lib "") (part "RES1_1")))
    (comp (ref "R122") (value "5.1K") (footprint "0603R") (libsource (lib "*") (part "RES1")))
    (comp (ref "R123") (value "5.1K") (footprint "0603R") (libsource (lib "*") (part "RES1")))
    (comp (ref "R124") (value "5.1K") (footprint "0603R") (libsource (lib "") (part "RES1_1")))
    (comp (ref "R125") (value "4.7K") (footprint "0603R") (libsource (lib "") (part "RES1_1")))
    (comp (ref "R126") (value "4.7K") (footprint "0603R") (libsource (lib "*") (part "RES1")))
    (comp (ref "R127") (value "4.7K") (footprint "0603R") (libsource (lib "*") (part "RES1")))
    (comp (ref "R128") (value "4.7K") (footprint "0603R") (libsource (lib "") (part "RES1_1")))
    (comp (ref "R129") (value "10K") (footprint "0603R") (libsource (lib "") (part "RES1_1")))
    (comp (ref "R130") (value "10K") (footprint "0603R") (libsource (lib "") (part "RES1_1")))
    (comp (ref "R137") (value "10K") (footprint "0603R") (libsource (lib "") (part "RES1_1")))
    (comp (ref "R138") (value "10K") (footprint "0603R") (libsource (lib "") (part "RES1_1")))
    (comp (ref "R139") (value "10K") (footprint "0603R") (libsource (lib "") (part "RES1_1")))
    (comp (ref "R140") (value "10K") (footprint "0603R") (libsource (lib "") (part "RES1_1")))
    (comp (ref "R141") (value "10K") (footprint "0603R") (libsource (lib "") (part "RES1_1")))
    (comp (ref "R142") (value "10K") (footprint "0603R") (libsource (lib "") (part "RES1_1")))
    (comp (ref "R143")
      (value "0R")
      (footprint "0603R")
      (description "RES")
      (libsource (lib "*") (part "RES-1"))
    )
    (comp (ref "R144")
      (value "0R")
      (footprint "0603R")
      (description "RES")
      (libsource (lib "*") (part "RES-1"))
    )
    (comp (ref "R145")
      (value "10R")
      (footprint "0603R")
      (description "RES")
      (libsource (lib "*") (part "RES-1"))
    )
    (comp (ref "R146")
      (value "10R")
      (footprint "0603R")
      (description "RES")
      (libsource (lib "*") (part "RES-1"))
    )
    (comp (ref "RL1")
      (value "JQ1P-24V")
      (footprint "HF32F-12V")
      (libsource (lib "UEEE20160408") (part "JQ1P-12V"))
    )
    (comp (ref "RL2")
      (value "JQ1P-24V")
      (footprint "HF32F-12V")
      (libsource (lib "UEEE20160408") (part "JQ1P-12V"))
    )
    (comp (ref "RL3")
      (value "JQ1P-24V")
      (footprint "HF32F-12V")
      (libsource (lib "UEEE20160408") (part "JQ1P-12V"))
    )
    (comp (ref "RL4")
      (value "JQ1P-24V")
      (footprint "HF32F-12V")
      (libsource (lib "UEEE20160408") (part "JQ1P-12V"))
    )
    (comp (ref "SW1") (value "SW SPST") (footprint "SW1") (libsource (lib "*") (part "SW SPST")))
    (comp (ref "SW2") (value "SW SPST") (footprint "SW1") (libsource (lib "*") (part "SW SPST")))
    (comp (ref "SW3") (value "按键") (footprint "SW") (libsource (lib "*") (part "SW-PB")))
    (comp (ref "SW4") (value "SW SPST") (footprint "SW1") (libsource (lib "*") (part "SW SPST")))
    (comp (ref "T1")
      (value "MARK1.0")
      (footprint "TXZ-GSM")
      (description "Connector")
      (libsource (lib "*") (part "CON1"))
    )
    (comp (ref "TVS1") (value "BA301N/NC") (footprint "3528TVS") (libsource (lib "*") (part "TVS")))
    (comp (ref "TVS2") (value "BA301N") (footprint "3528TVS") (libsource (lib "*") (part "TVS-D")))
    (comp (ref "TVS3") (value "BA301N") (footprint "3528TVS") (libsource (lib "*") (part "TVS-D")))
    (comp (ref "TVS4") (value "BA301N") (footprint "3528TVS") (libsource (lib "*") (part "TVS")))
    (comp (ref "TVS5") (value "BA301N") (footprint "3528TVS") (libsource (lib "*") (part "TVS-D")))
    (comp (ref "TVS6") (value "BA301N") (footprint "3528TVS") (libsource (lib "*") (part "TVS")))
    (comp (ref "U1")
      (value "LPC1778FBD144")
      (footprint "LC-LQFP-144_20x20x05P")
      (libsource (lib "直流原理图库") (part "LPC1778LQFP144"))
    )
    (comp (ref "U2") (value "MIC29302") (footprint "TO5B") (libsource (lib "*") (part "MIC29302")))
    (comp (ref "U3") (value "SP3232") (footprint "SO-16") (libsource (lib "*") (part "MAX232ESE")))
    (comp (ref "U4")
      (value "RSM485S_CTM8251T")
      (footprint "RSM485")
      (libsource (lib "*") (part "RSM485S_CTM8251T"))
    )
    (comp (ref "U5") (value "EUP3484") (footprint "SOP8") (libsource (lib "*") (part "EUP3484")))
    (comp (ref "U6") (value "SP706SEN") (footprint "SOP8") (libsource (lib "*") (part "SP706SEN")))
    (comp (ref "U7") (value "CTM8251") (footprint "CTM8251KT") (libsource (lib "直流原理图库") (part "CTM8251")))
    (comp (ref "U8") (value "MIC29302") (footprint "TO5B") (libsource (lib "MYSCHLIB") (part "MIC29302")))
    (comp (ref "U9") (value "W5500") (footprint "W5500") (libsource (lib "*") (part "W5500")))
    (comp (ref "U10")
      (value "NUP4301MR6")
      (footprint "TSOP-6")
      (description "NUP4301MR6T1")
      (libsource (lib "*") (part "NUP4301"))
    )
    (comp (ref "U11")
      (value "BELL")
      (footprint "BUZ")
      (description "Bell")
      (libsource (lib "*") (part "BELL"))
    )
    (comp (ref "U12")
      (value "FC-256GYNL (or 13F-60FGYDPNW2)")
      (footprint "RJ45-2")
      (description "LU1T516")
      (libsource (lib "*") (part "LU1T516"))
    )
    (comp (ref "U13") (value "FM25CL64") (footprint "SOP8") (libsource (lib "*") (part "FM25CL64")))
    (comp (ref "U14")
      (value "MX25L1635DM2I-10G")
      (footprint "MX25L1635E")
      (libsource (lib "*") (part "MX25L1635EM2I-10G"))
    )
    (comp (ref "U15") (value "PRTR5V0U2X") (footprint "SOT-143B") (libsource (lib "*") (part "PRTR5V0U2X_1")))
    (comp (ref "U16") (value "SP3232") (footprint "SO-16") (libsource (lib "*") (part "MAX232ESE")))
    (comp (ref "U17") (value "74HC245") (footprint "TSSOP20") (libsource (lib "*") (part "74HC245")))
    (comp (ref "UG1") (value "PS2501L-1") (footprint "DIP-4") (libsource (lib "*") (part "PS2501-1")))
    (comp (ref "UG2") (value "PS2501L-1") (footprint "DIP-4") (libsource (lib "*") (part "PS2501-1")))
    (comp (ref "UG3") (value "PS2501L-1") (footprint "DIP-4") (libsource (lib "*") (part "PS2501-1")))
    (comp (ref "UG4") (value "PS2501L-1") (footprint "DIP-4") (libsource (lib "*") (part "PS2501-1")))
    (comp (ref "Y1") (value "32.768KHz") (footprint "ZS-32.768") (libsource (lib "") (part "CRYSTAL_1")))
    (comp (ref "Y2") (value "12M") (footprint "ZS_SMD") (libsource (lib "") (part "CRYSTAL_1")))
    (comp (ref "Y3")
      (value "25MHz")
      (footprint "ZS_SMD")
      (description "Crystal")
      (libsource (lib "*") (part "CRYSTAL"))
    )
  )
  (nets
    (net (code "1") (name "/485_CON2") (class "Default")
      (node (ref "U1") (pin "68") (pinfunction "P4[3]/EMC_A[3]_68") (pintype "bidirectional"))
      (node (ref "U4") (pin "5") (pinfunction "485_CON_5") (pintype "passive"))
    )
    (net (code "2") (name "/ACT_LED") (class "Default")
      (node (ref "U12") (pin "11") (pinfunction "YEL-_11") (pintype "passive"))
      (node (ref "U9") (pin "27") (pinfunction "ACTLED_27") (pintype "output"))
    )
    (net (code "3") (name "/CANH2") (class "Default")
      (node (ref "J7") (pin "5") (pinfunction "5_5") (pintype "passive"))
      (node (ref "J7") (pin "7") (pinfunction "7_7") (pintype "passive"))
      (node (ref "R38") (pin "2") (pinfunction "2_2") (pintype "passive"))
      (node (ref "TVS6") (pin "1") (pintype "passive"))
      (node (ref "U7") (pin "6") (pinfunction "CANH_6") (pintype "passive"))
    )
    (net (code "4") (name "/CANL2") (class "Default")
      (node (ref "J7") (pin "6") (pinfunction "6_6") (pintype "passive"))
      (node (ref "J7") (pin "8") (pinfunction "8_8") (pintype "passive"))
      (node (ref "R38") (pin "1") (pinfunction "1_1") (pintype "passive"))
      (node (ref "TVS5") (pin "2") (pintype "passive"))
      (node (ref "TVS6") (pin "2") (pintype "passive"))
      (node (ref "U7") (pin "7") (pinfunction "CANL_7") (pintype "passive"))
    )
    (net (code "5") (name "/CAN_RD1") (class "Default")
      (node (ref "R39") (pin "2") (pinfunction "2_2") (pintype "passive"))
      (node (ref "U1") (pin "82") (pinfunction "P0[21]/U1_RI/SD_PWR/U4_OE/CAN_RD1/U4_SCLK_82") (pintype "bidirectional"))
      (node (ref "U7") (pin "4") (pinfunction "RD_4") (pintype "passive"))
    )
    (net (code "6") (name "/CAN_RD2") (class "Default")
      (node (ref "U1") (pin "95") (pinfunction "P2[7]/CAN_RD2/U1_RTS_95") (pintype "bidirectional"))
    )
    (net (code "7") (name "/CAN_TD1") (class "Default")
      (node (ref "R37") (pin "2") (pinfunction "2_2") (pintype "passive"))
      (node (ref "U1") (pin "80") (pinfunction "P0[22]/U1_RTS/SD_DAT0/U4_TXD/CAN_TD1_80") (pintype "bidirectional"))
      (node (ref "U7") (pin "3") (pinfunction "TD_3") (pintype "passive"))
    )
    (net (code "8") (name "/CAN_TD2") (class "Default")
      (node (ref "U1") (pin "93") (pinfunction "P2[8]/CAN_TD2/U2_TXD/U1_CTS/ENET_MDC_93") (pintype "bidirectional"))
    )
    (net (code "9") (name "/DI-1") (class "Default")
      (node (ref "C65") (pin "2") (pintype "passive"))
      (node (ref "J14") (pin "1") (pinfunction "1_1") (pintype "passive"))
      (node (ref "UG1") (pin "2") (pintype "passive"))
    )
    (net (code "10") (name "/DI-2") (class "Default")
      (node (ref "C63") (pin "2") (pintype "passive"))
      (node (ref "J14") (pin "3") (pinfunction "3_3") (pintype "passive"))
      (node (ref "UG2") (pin "2") (pintype "passive"))
    )
    (net (code "11") (name "/DI-3") (class "Default")
      (node (ref "C84") (pin "2") (pintype "passive"))
      (node (ref "J14") (pin "5") (pinfunction "5_5") (pintype "passive"))
      (node (ref "UG3") (pin "2") (pintype "passive"))
    )
    (net (code "12") (name "/DI-4") (class "Default")
      (node (ref "C82") (pin "2") (pintype "passive"))
      (node (ref "J14") (pin "7") (pinfunction "7_7") (pintype "passive"))
      (node (ref "UG4") (pin "2") (pintype "passive"))
    )
    (net (code "13") (name "/DO1_1") (class "Default")
      (node (ref "J8") (pin "1") (pinfunction "1_1") (pintype "passive"))
      (node (ref "RL1") (pin "3") (pinfunction "CM_3") (pintype "passive"))
    )
    (net (code "14") (name "/DO1_2") (class "Default")
      (node (ref "J8") (pin "2") (pinfunction "2_2") (pintype "passive"))
      (node (ref "RL1") (pin "4") (pinfunction "RO_4") (pintype "passive"))
    )
    (net (code "15") (name "/DO2_1") (class "Default")
      (node (ref "J8") (pin "3") (pinfunction "3_3") (pintype "passive"))
      (node (ref "RL2") (pin "3") (pinfunction "CM_3") (pintype "passive"))
    )
    (net (code "16") (name "/DO2_2") (class "Default")
      (node (ref "J8") (pin "4") (pinfunction "4_4") (pintype "passive"))
      (node (ref "RL2") (pin "4") (pinfunction "RO_4") (pintype "passive"))
    )
    (net (code "17") (name "/DO3_1") (class "Default")
      (node (ref "J8") (pin "5") (pinfunction "5_5") (pintype "passive"))
      (node (ref "RL3") (pin "3") (pinfunction "CM_3") (pintype "passive"))
    )
    (net (code "18") (name "/DO3_2") (class "Default")
      (node (ref "J8") (pin "6") (pinfunction "6_6") (pintype "passive"))
      (node (ref "RL3") (pin "4") (pinfunction "RO_4") (pintype "passive"))
    )
    (net (code "19") (name "/DO4_1") (class "Default")
      (node (ref "J8") (pin "7") (pinfunction "7_7") (pintype "passive"))
      (node (ref "RL4") (pin "3") (pinfunction "CM_3") (pintype "passive"))
    )
    (net (code "20") (name "/DO4_2") (class "Default")
      (node (ref "J8") (pin "8") (pinfunction "8_8") (pintype "passive"))
      (node (ref "RL4") (pin "4") (pinfunction "RO_4") (pintype "passive"))
    )
    (net (code "21") (name "/FDX_LED") (class "Default")
      (node (ref "U9") (pin "26") (pinfunction "DUPLED_26") (pintype "output"))
    )
    (net (code "22") (name "/FRAM_CS") (class "Default")
      (node (ref "R76") (pin "2") (pinfunction "2_2") (pintype "passive"))
      (node (ref "U1") (pin "90") (pinfunction "P0[16]/U1_RXD/SSP0_SSEL_90") (pintype "bidirectional"))
      (node (ref "U13") (pin "1") (pinfunction "~{CS}_1") (pintype "passive"))
    )
    (net (code "23") (name "/FRAM_MISO") (class "Default")
      (node (ref "R75") (pin "2") (pinfunction "2_2") (pintype "passive"))
      (node (ref "U1") (pin "87") (pinfunction "P0[17]/U1_CTS/SSP0_MISO_87") (pintype "bidirectional"))
      (node (ref "U13") (pin "2") (pinfunction "SO_2") (pintype "passive"))
    )
    (net (code "24") (name "/FRAM_MOSI") (class "Default")
      (node (ref "R79") (pin "2") (pinfunction "2_2") (pintype "passive"))
      (node (ref "U1") (pin "86") (pinfunction "P0[18]/U1_DCD/SSP0_MOSI_86") (pintype "bidirectional"))
      (node (ref "U13") (pin "5") (pinfunction "SI_5") (pintype "passive"))
    )
    (net (code "25") (name "/FRAM_SCK") (class "Default")
      (node (ref "R78") (pin "2") (pinfunction "2_2") (pintype "passive"))
      (node (ref "U1") (pin "89") (pinfunction "P0[15]/U1_TXD/SSP0_SCK_89") (pintype "bidirectional"))
      (node (ref "U13") (pin "6") (pinfunction "SCK_6") (pintype "passive"))
    )
    (net (code "26") (name "/GPRS_PWR") (class "Default")
      (node (ref "R93") (pin "1") (pintype "passive"))
      (node (ref "U1") (pin "38") (pinfunction "P3[26]/EMC_D[26]/PWM1[3]/T0_MAT1/STCLK_38") (pintype "bidirectional"))
    )
    (net (code "27") (name "/GPRS_RESET") (class "Default")
      (node (ref "R110") (pin "2") (pintype "passive"))
      (node (ref "U1") (pin "6") (pinfunction "P5[0]/EMC_A[24]/SSP2_MOSI/T2_MAT2_6") (pintype "bidirectional"))
    )
    (net (code "28") (name "/ISP") (class "Default")
      (node (ref "R23") (pin "1") (pintype "passive"))
      (node (ref "SW2") (pin "2") (pinfunction "NO_2") (pintype "passive"))
      (node (ref "U1") (pin "76") (pinfunction "P2[10]/EINT0/NMI_76") (pintype "bidirectional"))
    )
    (net (code "29") (name "/LED-WARNING") (class "Default")
      (node (ref "R32") (pin "1") (pintype "passive"))
      (node (ref "U1") (pin "118") (pinfunction "P4[28]/EMC_ABLS2/U3_TXD/T2_MAT0_118") (pintype "bidirectional"))
    )
    (net (code "30") (name "/LED-WARNING1") (class "Default")
      (node (ref "J4") (pin "4") (pinfunction "4_4") (pintype "passive"))
      (node (ref "U17") (pin "12") (pinfunction "B6_12") (pintype "passive"))
    )
    (net (code "31") (name "/LEDCS") (class "Default")
      (node (ref "R64") (pin "1") (pintype "passive"))
      (node (ref "U1") (pin "122") (pinfunction "P4[29]/EMC_BLS3/U3_RXD/T2_MAT1/I2C2_SCL_122") (pintype "bidirectional"))
    )
    (net (code "32") (name "/LEDCS1") (class "Default")
      (node (ref "J4") (pin "1") (pinfunction "1_1") (pintype "passive"))
      (node (ref "U17") (pin "17") (pinfunction "B1_17") (pintype "passive"))
    )
    (net (code "33") (name "/LED_CHARGE") (class "Default")
      (node (ref "R31") (pin "1") (pintype "passive"))
      (node (ref "U1") (pin "120") (pinfunction "P4[15]/EMC_A[15]_120") (pintype "bidirectional"))
    )
    (net (code "34") (name "/LED_CHARGE1") (class "Default")
      (node (ref "J4") (pin "3") (pinfunction "3_3") (pintype "passive"))
      (node (ref "U17") (pin "15") (pinfunction "B3_15") (pintype "passive"))
    )
    (net (code "35") (name "/LED_PWR") (class "Default")
      (node (ref "R63") (pin "1") (pintype "passive"))
      (node (ref "U1") (pin "124") (pinfunction "P4[25]/EMC_WE_124") (pintype "bidirectional"))
    )
    (net (code "36") (name "/LED_PWR1") (class "Default")
      (node (ref "J4") (pin "2") (pinfunction "2_2") (pintype "passive"))
      (node (ref "U17") (pin "18") (pinfunction "B0_18") (pintype "passive"))
    )
    (net (code "37") (name "/LINK_LED") (class "Default")
      (node (ref "U12") (pin "10") (pinfunction "GRN-_10") (pintype "passive"))
      (node (ref "U9") (pin "25") (pinfunction "LINKLED_25") (pintype "output"))
    )
    (net (code "38") (name "/MODE0") (class "Default")
      (node (ref "R53") (pin "2") (pintype "passive"))
      (node (ref "U9") (pin "45") (pinfunction "PMODE0_45") (pintype "input"))
    )
    (net (code "39") (name "/MODE1") (class "Default")
      (node (ref "R52") (pin "2") (pintype "passive"))
      (node (ref "U9") (pin "44") (pinfunction "PMODE1_44") (pintype "input"))
    )
    (net (code "40") (name "/MODE2") (class "Default")
      (node (ref "R51") (pin "2") (pintype "passive"))
      (node (ref "U9") (pin "43") (pinfunction "PMODE2_43") (pintype "input"))
    )
    (net (code "41") (name "/MODE8") (class "Default")
      (node (ref "R58") (pin "1") (pinfunction "1_1") (pintype "passive"))
      (node (ref "SW4") (pin "2") (pinfunction "NO_2") (pintype "passive"))
      (node (ref "U1") (pin "72") (pinfunction "P4[4]/EMC_A[4]_72") (pintype "bidirectional"))
    )
    (net (code "42") (name "/NOR_CS") (class "Default")
      (node (ref "R82") (pin "2") (pinfunction "2_2") (pintype "passive"))
      (node (ref "U1") (pin "57") (pinfunction "P1[26]/USB_SSPND1/PWM1[6]/T0_CAP0/MC_1B/SSP1_SSEL_57") (pintype "bidirectional"))
      (node (ref "U14") (pin "1") (pinfunction "~{CS}#_1") (pintype "passive"))
    )
    (net (code "43") (name "/NOR_MISO") (class "Default")
      (node (ref "R81") (pin "2") (pinfunction "2_2") (pintype "passive"))
      (node (ref "U1") (pin "46") (pinfunction "P1[18]/USB_UP_LED1/PWM1[1]/T1CAP0/SSP1_MISO_46") (pintype "bidirectional"))
      (node (ref "U14") (pin "2") (pinfunction "SO_2") (pintype "passive"))
    )
    (net (code "44") (name "/NOR_MOSI") (class "Default")
      (node (ref "R85") (pin "2") (pinfunction "2_2") (pintype "passive"))
      (node (ref "U1") (pin "51") (pinfunction "P1[22]/USB_RCV1/USB_PWRD1/T1_MAT0/MC_0B/_SSP1_MOSI_51") (pintype "bidirectional"))
      (node (ref "U14") (pin "5") (pinfunction "SI_5") (pintype "passive"))
    )
    (net (code "45") (name "/NOR_SCK") (class "Default")
      (node (ref "R84") (pin "2") (pinfunction "2_2") (pintype "passive"))
      (node (ref "U1") (pin "47") (pinfunction "P1[19]/USB_TX_E1/USB_PPWR1/T1_CAP1/MC_0A/SSP1_SCK/U2_OE_47") (pintype "bidirectional"))
      (node (ref "U14") (pin "6") (pinfunction "SCLK_6") (pintype "passive"))
    )
    (net (code "46") (name "/P23") (class "Default")
      (node (ref "R49") (pin "1") (pintype "passive"))
      (node (ref "U9") (pin "23") (pinfunction "RSVD_23") (pintype "input"))
    )
    (net (code "47") (name "/P38") (class "Default")
      (node (ref "R60") (pin "1") (pintype "passive"))
      (node (ref "U9") (pin "38") (pinfunction "RSVD_38") (pintype "input"))
    )
    (net (code "48") (name "/P39") (class "Default")
      (node (ref "R59") (pin "1") (pintype "passive"))
      (node (ref "U9") (pin "39") (pinfunction "RSVD_39") (pintype "input"))
    )
    (net (code "49") (name "/P40") (class "Default")
      (node (ref "R57") (pin "1") (pintype "passive"))
      (node (ref "U9") (pin "40") (pinfunction "RSVD_40") (pintype "input"))
    )
    (net (code "50") (name "/P41") (class "Default")
      (node (ref "R55") (pin "1") (pintype "passive"))
      (node (ref "U9") (pin "41") (pinfunction "RSVD_41") (pintype "input"))
    )
    (net (code "51") (name "/P42") (class "Default")
      (node (ref "R50") (pin "2") (pintype "passive"))
      (node (ref "U9") (pin "42") (pinfunction "RSVD_42") (pintype "input"))
    )
    (net (code "52") (name "/RESET_N") (class "Default")
      (node (ref "J15") (pin "22") (pinfunction "RESET_N_22") (pintype "passive"))
      (node (ref "Q7") (pin "3") (pinfunction "C_3") (pintype "passive"))
      (node (ref "R115") (pin "2") (pintype "passive"))
    )
    (net (code "53") (name "/RTCK1") (class "Default")
      (node (ref "C36") (pin "1") (pinfunction "1_1") (pintype "passive"))
      (node (ref "U1") (pin "23") (pinfunction "RTCX1_23") (pintype "bidirectional"))
      (node (ref "Y1") (pin "1") (pinfunction "1_1") (pintype "passive"))
    )
    (net (code "54") (name "/RTCK2") (class "Default")
      (node (ref "C40") (pin "1") (pinfunction "1_1") (pintype "passive"))
      (node (ref "U1") (pin "25") (pinfunction "RTCX2_25") (pintype "bidirectional"))
      (node (ref "Y1") (pin "2") (pinfunction "2_2") (pintype "passive"))
    )
    (net (code "55") (name "/RXIN") (class "Default")
      (node (ref "C51") (pin "1") (pintype "passive"))
      (node (ref "R68") (pin "2") (pinfunction "2_2") (pintype "passive"))
      (node (ref "U10") (pin "3") (pinfunction "IO3_3") (pintype "bidirectional"))
      (node (ref "U9") (pin "6") (pinfunction "RXP_6") (pintype "input"))
    )
    (net (code "56") (name "/RXIP") (class "Default")
      (node (ref "C47") (pin "1") (pintype "passive"))
      (node (ref "R69") (pin "2") (pinfunction "2_2") (pintype "passive"))
      (node (ref "U10") (pin "4") (pinfunction "IO4_4") (pintype "bidirectional"))
      (node (ref "U9") (pin "5") (pinfunction "RXN_5") (pintype "input"))
    )
    (net (code "57") (name "/Run") (class "Default")
      (node (ref "R34") (pin "1") (pinfunction "1_1") (pintype "passive"))
      (node (ref "U1") (pin "29") (pinfunction "P0[12]/USB_PPWR2/SSP1_MISO/ADC0_IN6_29") (pintype "bidirectional"))
    )
    (net (code "58") (name "/RxD") (class "Default")
      (node (ref "J15") (pin "11") (pinfunction "UART_RXD_11") (pintype "passive"))
      (node (ref "R44") (pin "1") (pintype "passive"))
    )
    (net (code "59") (name "/SPD_LED") (class "Default")
      (node (ref "U9") (pin "24") (pinfunction "SPDLED_24") (pintype "output"))
    )
    (net (code "60") (name "/S_NET_CLK") (class "Default")
      (node (ref "U1") (pin "136") (pinfunction "P1[0]/ENET_TXD0/T3_CAP1/SSP2_SCK_136") (pintype "bidirectional"))
      (node (ref "U9") (pin "33") (pinfunction "SCLK_33") (pintype "input"))
    )
    (net (code "61") (name "/S_NET_CS") (class "Default")
      (node (ref "R48") (pin "1") (pintype "passive"))
      (node (ref "U1") (pin "132") (pinfunction "P1[8]/ENET_CRS/T3_MAT1/SSP2_SSEL_132") (pintype "bidirectional"))
      (node (ref "U9") (pin "32") (pinfunction "~{SCS}_32") (pintype "input"))
    )
    (net (code "62") (name "/S_NET_MISO") (class "Default")
      (node (ref "U1") (pin "133") (pinfunction "P1[4]/ENET_TX_EN/T3_MAT2/SSP2_MISO_133") (pintype "bidirectional"))
      (node (ref "U9") (pin "34") (pinfunction "MISO_34") (pintype "output"))
    )
    (net (code "63") (name "/S_NET_MOSI") (class "Default")
      (node (ref "U1") (pin "135") (pinfunction "P1[1]/ENET_TXD1/T3_MAT3/SSP2_MOSI_135") (pintype "bidirectional"))
      (node (ref "U9") (pin "35") (pinfunction "MOSI_35") (pintype "input"))
    )
    (net (code "64") (name "/T1") (class "Default")
      (node (ref "MARKE3") (pin "1") (pinfunction "1_1") (pintype "passive"))
      (node (ref "T1") (pin "1") (pinfunction "1_1") (pintype "passive"))
    )
    (net (code "65") (name "/TCK") (class "Default")
      (node (ref "J1") (pin "1") (pinfunction "1_1") (pintype "passive"))
      (node (ref "R2") (pin "1") (pinfunction "1_1") (pintype "passive"))
      (node (ref "U1") (pin "7") (pinfunction "JTAG_TCK_7") (pintype "bidirectional"))
    )
    (net (code "66") (name "/TDO") (class "Default")
      (node (ref "U1") (pin "1") (pinfunction "JTAG_TDO_1") (pintype "bidirectional"))
    )
    (net (code "67") (name "/TMS") (class "Default")
      (node (ref "J1") (pin "2") (pinfunction "2_2") (pintype "passive"))
      (node (ref "R1") (pin "1") (pinfunction "1_1") (pintype "passive"))
      (node (ref "U1") (pin "4") (pinfunction "JTAG_TMS_4") (pintype "bidirectional"))
    )
    (net (code "68") (name "/TXON") (class "Default")
      (node (ref "R65") (pin "1") (pinfunction "1_1") (pintype "passive"))
      (node (ref "U10") (pin "1") (pinfunction "IO1_1") (pintype "bidirectional"))
      (node (ref "U12") (pin "2") (pinfunction "TD-_2") (pintype "passive"))
      (node (ref "U9") (pin "2") (pinfunction "TXP_2") (pintype "output"))
    )
    (net (code "69") (name "/TXOP") (class "Default")
      (node (ref "R66") (pin "1") (pinfunction "1_1") (pintype "passive"))
      (node (ref "U10") (pin "6") (pinfunction "IO2_6") (pintype "bidirectional"))
      (node (ref "U12") (pin "1") (pinfunction "TD+_1") (pintype "passive"))
      (node (ref "U9") (pin "1") (pinfunction "TXN_1") (pintype "output"))
    )
    (net (code "70") (name "/TxD") (class "Default")
      (node (ref "J15") (pin "13") (pinfunction "UART_TXD_13") (pintype "passive"))
      (node (ref "R92") (pin "2") (pintype "passive"))
    )
    (net (code "71") (name "/U0-RX") (class "Default")
      (node (ref "J9") (pin "2") (pinfunction "2_2") (pintype "passive"))
      (node (ref "R145") (pin "2") (pintype "passive"))
      (node (ref "TVS1") (pin "2") (pintype "passive"))
      (node (ref "TVS2") (pin "2") (pintype "passive"))
    )
    (net (code "72") (name "/U0-RXD") (class "Default")
      (node (ref "R143") (pin "1") (pintype "passive"))
      (node (ref "U1") (pin "142") (pinfunction "P0[3]/U0_RXD/U3_RXD_142") (pintype "bidirectional"))
    )
    (net (code "73") (name "/U0-TX") (class "Default")
      (node (ref "J9") (pin "3") (pinfunction "3_3") (pintype "passive"))
      (node (ref "R146") (pin "2") (pintype "passive"))
      (node (ref "TVS1") (pin "1") (pintype "passive"))
    )
    (net (code "74") (name "/U0-TXD") (class "Default")
      (node (ref "R144") (pin "1") (pintype "passive"))
      (node (ref "U1") (pin "141") (pinfunction "P0[2]/U0_TXD/U3_TXD_141") (pintype "bidirectional"))
    )
    (net (code "75") (name "/U1-RX") (class "Default")
      (node (ref "J5") (pin "4") (pinfunction "4_4") (pintype "passive"))
      (node (ref "R14") (pin "2") (pintype "passive"))
    )
    (net (code "76") (name "/U1-TX") (class "Default")
      (node (ref "J5") (pin "5") (pinfunction "5_5") (pintype "passive"))
      (node (ref "J5") (pin "6") (pinfunction "6_6") (pintype "passive"))
      (node (ref "R18") (pin "2") (pintype "passive"))
    )
    (net (code "77") (name "/U1_RXD") (class "Default")
      (node (ref "R13") (pin "1") (pintype "passive"))
      (node (ref "U1") (pin "106") (pinfunction "P2[1]/PWM1[2]/U1_RXD_106") (pintype "bidirectional"))
    )
    (net (code "78") (name "/U1_TXD") (class "Default")
      (node (ref "R17") (pin "1") (pintype "passive"))
      (node (ref "U1") (pin "107") (pinfunction "P2[0]/PWM1[1]/U1_TXD_107") (pintype "bidirectional"))
    )
    (net (code "79") (name "/U2_RXD") (class "Default")
      (node (ref "R21") (pin "2") (pintype "passive"))
      (node (ref "U1") (pin "70") (pinfunction "P0[11]/U2_RXD/I2C2_SCL/T3_MAT1_70") (pintype "bidirectional"))
      (node (ref "U4") (pin "4") (pinfunction "RXD_4") (pintype "passive"))
    )
    (net (code "80") (name "/U2_TXD") (class "Default")
      (node (ref "R20") (pin "2") (pintype "passive"))
      (node (ref "U1") (pin "69") (pinfunction "P0[10]/U2_TXD/I2C2_SDA/T3_MAT0_69") (pintype "bidirectional"))
      (node (ref "U4") (pin "3") (pinfunction "TXD_3") (pintype "passive"))
    )
    (net (code "81") (name "/U3_RXD") (class "Default")
      (node (ref "Q3") (pin "3") (pinfunction "C_3") (pintype "passive"))
      (node (ref "R45") (pin "2") (pintype "passive"))
      (node (ref "U1") (pin "8") (pinfunction "P0[26]/ADC0_IN3/DAC_OUT/U3_RXD_8") (pintype "bidirectional"))
    )
    (net (code "82") (name "/U3_TXD") (class "Default")
      (node (ref "D7") (pin "2") (pinfunction "K_2") (pintype "passive"))
      (node (ref "U1") (pin "10") (pinfunction "P0[25]/ADC0_IN2/I2S_RX_SDA/U3_TXD_10") (pintype "bidirectional"))
    )
    (net (code "83") (name "/U4_485A") (class "Default")
      (node (ref "J7") (pin "1") (pinfunction "1_1") (pintype "passive"))
      (node (ref "J7") (pin "3") (pinfunction "3_3") (pintype "passive"))
      (node (ref "R19") (pin "2") (pintype "passive"))
      (node (ref "TVS4") (pin "2") (pintype "passive"))
    )
    (net (code "84") (name "/U4_485B") (class "Default")
      (node (ref "J7") (pin "2") (pinfunction "2_2") (pintype "passive"))
      (node (ref "J7") (pin "4") (pinfunction "4_4") (pintype "passive"))
      (node (ref "R22") (pin "2") (pintype "passive"))
      (node (ref "TVS3") (pin "2") (pintype "passive"))
      (node (ref "TVS4") (pin "1") (pintype "passive"))
    )
    (net (code "85") (name "/U4_RX") (class "Default")
      (node (ref "J6") (pin "5") (pinfunction "5_5") (pintype "passive"))
      (node (ref "R12") (pin "2") (pintype "passive"))
    )
    (net (code "86") (name "/U4_RXD") (class "Default")
      (node (ref "R11") (pin "1") (pintype "passive"))
      (node (ref "U1") (pin "98") (pinfunction "P5[3]/U4_RXD//I2C0_SCL_98") (pintype "bidirectional"))
    )
    (net (code "87") (name "/U4_TX") (class "Default")
      (node (ref "J6") (pin "6") (pinfunction "6_6") (pintype "passive"))
      (node (ref "R16") (pin "2") (pintype "passive"))
    )
    (net (code "88") (name "/U4_TXD") (class "Default")
      (node (ref "R15") (pin "1") (pintype "passive"))
      (node (ref "U1") (pin "143") (pinfunction "P5[4]/U0_OE/T3_MAT3/U4_TXD_143") (pintype "bidirectional"))
    )
    (net (code "89") (name "/UIM-CLK") (class "Default")
      (node (ref "J15") (pin "12") (pinfunction "UIM_CLK_12") (pintype "passive"))
      (node (ref "R100") (pin "2") (pintype "passive"))
    )
    (net (code "90") (name "/UIM-I{slash}O") (class "Default")
      (node (ref "J15") (pin "10") (pinfunction "UIM_DATA_10") (pintype "passive"))
      (node (ref "R99") (pin "2") (pintype "passive"))
    )
    (net (code "91") (name "/UIM-RST") (class "Default")
      (node (ref "J15") (pin "14") (pinfunction "UIM_RESET_14") (pintype "passive"))
      (node (ref "R98") (pin "2") (pintype "passive"))
    )
    (net (code "92") (name "/UIM-VCC") (class "Default")
      (node (ref "C66") (pin "1") (pinfunction "1_1") (pintype "passive"))
      (node (ref "C67") (pin "1") (pinfunction "1_1") (pintype "passive"))
      (node (ref "J13") (pin "1") (pinfunction "VCC_1") (pintype "passive"))
      (node (ref "J15") (pin "8") (pinfunction "UIM_PWR_8") (pintype "passive"))
      (node (ref "R97") (pin "2") (pintype "passive"))
    )
    (net (code "93") (name "/USBD2+") (class "Default")
      (node (ref "R87") (pin "2") (pintype "passive"))
      (node (ref "U1") (pin "36") (pinfunction "P0[31]/USB_D+2_36") (pintype "bidirectional"))
    )
    (net (code "94") (name "/USBD2-") (class "Default")
      (node (ref "R86") (pin "2") (pintype "passive"))
      (node (ref "U1") (pin "37") (pinfunction "USB_D-2_37") (pintype "bidirectional"))
    )
    (net (code "95") (name "/USB_LED") (class "Default")
      (node (ref "LED2") (pin "2") (pintype "passive"))
      (node (ref "U1") (pin "32") (pinfunction "P0[13]/USB_UP_LED2/SSP1_MOSI/ADC0_IN7_32") (pintype "bidirectional"))
    )
    (net (code "96") (name "/W5500_{slash}INT") (class "Default")
      (node (ref "R47") (pin "1") (pintype "passive"))
      (node (ref "U1") (pin "96") (pinfunction "P2[6]/PWM1_CAP0/U1_RI/T2_CAP0/U2_OE/TRACECELK_96") (pintype "bidirectional"))
      (node (ref "U9") (pin "36") (pinfunction "~{INT}_36") (pintype "output"))
    )
    (net (code "97") (name "/W5500_{slash}RST") (class "Default")
      (node (ref "R46") (pin "1") (pintype "passive"))
      (node (ref "U1") (pin "94") (pinfunction "P4[10]/EMC_A[10]_94") (pintype "bidirectional"))
      (node (ref "U9") (pin "37") (pinfunction "~{RST}_37") (pintype "input"))
    )
    (net (code "98") (name "/WDI") (class "Default")
      (node (ref "R28") (pin "2") (pinfunction "2_2") (pintype "passive"))
      (node (ref "U1") (pin "35") (pinfunction "P0[27]/I2C0_SDA/USB_SDA1_35") (pintype "bidirectional"))
      (node (ref "U6") (pin "6") (pinfunction "WDI_6") (pintype "passive"))
    )
    (net (code "99") (name "/XTAL1") (class "Default")
      (node (ref "C37") (pin "1") (pinfunction "1_1") (pintype "passive"))
      (node (ref "U1") (pin "31") (pinfunction "XTAL1_31") (pintype "bidirectional"))
      (node (ref "Y2") (pin "2") (pinfunction "2_2") (pintype "passive"))
    )
    (net (code "100") (name "/XTAL2") (class "Default")
      (node (ref "C41") (pin "1") (pinfunction "1_1") (pintype "passive"))
      (node (ref "U1") (pin "33") (pinfunction "XTAL2_33") (pintype "bidirectional"))
      (node (ref "Y2") (pin "1") (pinfunction "1_1") (pintype "passive"))
    )
    (net (code "101") (name "/di1") (class "Default")
      (node (ref "C62") (pin "1") (pintype "passive"))
      (node (ref "R130") (pin "2") (pinfunction "2_2") (pintype "passive"))
      (node (ref "U1") (pin "39") (pinfunction "P3[25]/EMC_D[25]/PWM1[2]/T0_MAT0_39") (pintype "bidirectional"))
      (node (ref "UG1") (pin "4") (pintype "passive"))
    )
    (net (code "102") (name "/di2") (class "Default")
      (node (ref "C64") (pin "1") (pintype "passive"))
      (node (ref "R138") (pin "2") (pinfunction "2_2") (pintype "passive"))
      (node (ref "U1") (pin "49") (pinfunction "P1[20]/USB_TX_DP1/PWM1[2]/QEI_PHA/MC_FB0/SSP0_SCK_49") (pintype "bidirectional"))
      (node (ref "UG2") (pin "4") (pintype "passive"))
    )
    (net (code "103") (name "/di3") (class "Default")
      (node (ref "C81") (pin "1") (pintype "passive"))
      (node (ref "R140") (pin "2") (pinfunction "2_2") (pintype "passive"))
      (node (ref "U1") (pin "53") (pinfunction "P1[23]/USB_RX_DP1/PWM1[4]/QEI_PHB/MC_FB1/SSP0_MISO_53") (pintype "bidirectional"))
      (node (ref "UG3") (pin "4") (pintype "passive"))
    )
    (net (code "104") (name "/di4") (class "Default")
      (node (ref "C83") (pin "1") (pintype "passive"))
      (node (ref "R142") (pin "2") (pinfunction "2_2") (pintype "passive"))
      (node (ref "U1") (pin "54") (pinfunction "P1[24]/USB_RX_DM1/PWM1[5]/QEI_IDX/MC_FB2/SSP0_MOSI_54") (pintype "bidirectional"))
      (node (ref "UG4") (pin "4") (pintype "passive"))
    )
    (net (code "105") (name "/do1") (class "Default")
      (node (ref "R121") (pin "1") (pinfunction "1_1") (pintype "passive"))
      (node (ref "U1") (pin "63") (pinfunction "P1[28]/USB_SCL1/PWM1_CAP0/T0_MAT0/MC_2A/SSP0_SSEL_63") (pintype "bidirectional"))
    )
    (net (code "106") (name "/do2") (class "Default")
      (node (ref "R122") (pin "1") (pinfunction "1_1") (pintype "passive"))
      (node (ref "U1") (pin "64") (pinfunction "P1[29]/USB_SDA1/PWM1_CAP1]/T0_MAT1/MC_2B/U4_TXD_64") (pintype "bidirectional"))
    )
    (net (code "107") (name "/do3") (class "Default")
      (node (ref "R123") (pin "1") (pinfunction "1_1") (pintype "passive"))
      (node (ref "U1") (pin "66") (pinfunction "P0[0]/CAN_RD1/U3_TXD/I2C1_SDA/U0_TXD_66") (pintype "bidirectional"))
    )
    (net (code "108") (name "/do4") (class "Default")
      (node (ref "R124") (pin "1") (pinfunction "1_1") (pintype "passive"))
      (node (ref "U1") (pin "67") (pinfunction "P0[1]/CAN_TD1/U3_RXD/I2C1_SCL/U0_RXD_67") (pintype "bidirectional"))
    )
    (net (code "109") (name "/nRST") (class "Default")
      (node (ref "C29") (pin "2") (pinfunction "2_2") (pintype "passive"))
      (node (ref "R30") (pin "2") (pinfunction "2_2") (pintype "passive"))
      (node (ref "R33") (pin "2") (pinfunction "2_2") (pintype "passive"))
      (node (ref "U1") (pin "24") (pinfunction "RESET_24") (pintype "bidirectional"))
    )
    (net (code "110") (name "/run_buzzer") (class "Default")
      (node (ref "R62") (pin "2") (pintype "passive"))
      (node (ref "U1") (pin "73") (pinfunction "P2[12]/EINT2/SD_DAT[2]/I2S_TX_WS_73") (pintype "bidirectional"))
    )
    (net (code "111") (name "/sw0") (class "Default")
      (node (ref "C89") (pin "1") (pintype "passive"))
      (node (ref "L9") (pin "1") (pinfunction "1_1") (pintype "passive"))
      (node (ref "U5") (pin "3") (pinfunction "SW_3") (pintype "passive"))
    )
    (net (code "112") (name "3.9V") (class "Default")
      (node (ref "C52") (pin "1") (pinfunction "1_1") (pintype "passive"))
      (node (ref "C60") (pin "1") (pinfunction "1_1") (pintype "passive"))
      (node (ref "EC5") (pin "1") (pinfunction "1_1") (pintype "passive"))
      (node (ref "EC6") (pin "1") (pinfunction "1_1") (pintype "passive"))
      (node (ref "J15") (pin "2") (pinfunction "+3.3V_2") (pintype "passive"))
      (node (ref "J15") (pin "24") (pinfunction "+3.3V_24") (pintype "passive"))
      (node (ref "J15") (pin "39") (pinfunction "+3.3V_39") (pintype "passive"))
      (node (ref "J15") (pin "41") (pinfunction "+3.3V_41") (pintype "passive"))
      (node (ref "J15") (pin "52") (pinfunction "+3.3V_52") (pintype "passive"))
      (node (ref "L6") (pin "2") (pinfunction "2_2") (pintype "passive"))
      (node (ref "R103") (pin "1") (pintype "passive"))
    )
    (net (code "113") (name "12VI") (class "Default")
      (node (ref "R101") (pin "2") (pintype "passive"))
      (node (ref "R129") (pin "1") (pinfunction "1_1") (pintype "passive"))
      (node (ref "R137") (pin "1") (pinfunction "1_1") (pintype "passive"))
      (node (ref "R139") (pin "1") (pinfunction "1_1") (pintype "passive"))
      (node (ref "R141") (pin "1") (pinfunction "1_1") (pintype "passive"))
    )
    (net (code "114") (name "12VS") (class "Default")
      (node (ref "D8") (pin "1") (pinfunction "A_1") (pintype "passive"))
      (node (ref "D9") (pin "1") (pinfunction "A_1") (pintype "passive"))
      (node (ref "J2") (pin "1") (pinfunction "1_1") (pintype "passive"))
      (node (ref "R101") (pin "1") (pintype "passive"))
    )
    (net (code "115") (name "DGND") (class "Default")
      (node (ref "BAT1") (pin "2") (pinfunction "2_2") (pintype "passive"))
      (node (ref "C1") (pin "2") (pinfunction "2_2") (pintype "passive"))
      (node (ref "C10") (pin "2") (pinfunction "2_2") (pintype "passive"))
      (node (ref "C11") (pin "2") (pinfunction "2_2") (pintype "passive"))
      (node (ref "C12") (pin "1") (pinfunction "1_1") (pintype "passive"))
      (node (ref "C13") (pin "2") (pinfunction "2_2") (pintype "passive"))
      (node (ref "C14") (pin "2") (pinfunction "2_2") (pintype "passive"))
      (node (ref "C15") (pin "2") (pinfunction "2_2") (pintype "passive"))
      (node (ref "C16") (pin "2") (pinfunction "2_2") (pintype "passive"))
      (node (ref "C17") (pin "1") (pintype "passive"))
      (node (ref "C2") (pin "2") (pinfunction "2_2") (pintype "passive"))
      (node (ref "C20") (pin "1") (pintype "passive"))
      (node (ref "C21") (pin "1") (pintype "passive"))
      (node (ref "C22") (pin "2") (pinfunction "2_2") (pintype "passive"))
      (node (ref "C24") (pin "1") (pintype "passive"))
      (node (ref "C25") (pin "2") (pintype "passive"))
      (node (ref "C27") (pin "2") (pinfunction "2_2") (pintype "passive"))
      (node (ref "C28") (pin "1") (pinfunction "1_1") (pintype "passive"))
      (node (ref "C29") (pin "1") (pinfunction "1_1") (pintype "passive"))
      (node (ref "C3") (pin "2") (pinfunction "2_2") (pintype "passive"))
      (node (ref "C31") (pin "2") (pinfunction "2_2") (pintype "passive"))
      (node (ref "C32") (pin "1") (pintype "passive"))
      (node (ref "C33") (pin "2") (pinfunction "2_2") (pintype "passive"))
      (node (ref "C36") (pin "2") (pinfunction "2_2") (pintype "passive"))
      (node (ref "C37") (pin "2") (pinfunction "2_2") (pintype "passive"))
      (node (ref "C38") (pin "2") (pintype "passive"))
      (node (ref "C39") (pin "1") (pintype "passive"))
      (node (ref "C4") (pin "2") (pinfunction "2_2") (pintype "passive"))
      (node (ref "C40") (pin "2") (pinfunction "2_2") (pintype "passive"))
      (node (ref "C41") (pin "2") (pinfunction "2_2") (pintype "passive"))
      (node (ref "C42") (pin "2") (pintype "passive"))
      (node (ref "C43") (pin "2") (pinfunction "2_2") (pintype "passive"))
      (node (ref "C44") (pin "1") (pintype "passive"))
      (node (ref "C45") (pin "2") (pinfunction "2_2") (pintype "passive"))
      (node (ref "C46") (pin "2") (pinfunction "2_2") (pintype "passive"))
      (node (ref "C48") (pin "2") (pintype "passive"))
      (node (ref "C49") (pin "2") (pintype "passive"))
      (node (ref "C5") (pin "2") (pinfunction "2_2") (pintype "passive"))
      (node (ref "C50") (pin "2") (pintype "passive"))
      (node (ref "C52") (pin "2") (pinfunction "2_2") (pintype "passive"))
      (node (ref "C53") (pin "2") (pintype "passive"))
      (node (ref "C54") (pin "2") (pintype "passive"))
      (node (ref "C55") (pin "2") (pintype "passive"))
      (node (ref "C56") (pin "2") (pintype "passive"))
      (node (ref "C57") (pin "2") (pintype "passive"))
      (node (ref "C58") (pin "2") (pintype "passive"))
      (node (ref "C59") (pin "2") (pintype "passive"))
      (node (ref "C6") (pin "2") (pinfunction "2_2") (pintype "passive"))
      (node (ref "C60") (pin "2") (pinfunction "2_2") (pintype "passive"))
      (node (ref "C61") (pin "2") (pinfunction "2_2") (pintype "passive"))
      (node (ref "C62") (pin "2") (pintype "passive"))
      (node (ref "C64") (pin "2") (pintype "passive"))
      (node (ref "C66") (pin "2") (pinfunction "2_2") (pintype "passive"))
      (node (ref "C67") (pin "2") (pinfunction "2_2") (pintype "passive"))
      (node (ref "C68") (pin "2") (pinfunction "2_2") (pintype "passive"))
      (node (ref "C69") (pin "2") (pinfunction "2_2") (pintype "passive"))
      (node (ref "C7") (pin "2") (pinfunction "2_2") (pintype "passive"))
      (node (ref "C70") (pin "2") (pinfunction "2_2") (pintype "passive"))
      (node (ref "C71") (pin "2") (pinfunction "2_2") (pintype "passive"))
      (node (ref "C77") (pin "2") (pintype "passive"))
      (node (ref "C78") (pin "1") (pinfunction "1_1") (pintype "passive"))
      (node (ref "C79") (pin "1") (pinfunction "1_1") (pintype "passive"))
      (node (ref "C8") (pin "2") (pinfunction "2_2") (pintype "passive"))
      (node (ref "C80") (pin "2") (pintype "passive"))
      (node (ref "C81") (pin "2") (pintype "passive"))
      (node (ref "C83") (pin "2") (pintype "passive"))
      (node (ref "C88") (pin "1") (pintype "passive"))
      (node (ref "C9") (pin "2") (pinfunction "2_2") (pintype "passive"))
      (node (ref "EC1") (pin "2") (pinfunction "2_2") (pintype "passive"))
      (node (ref "EC2") (pin "2") (pinfunction "2_2") (pintype "passive"))
      (node (ref "EC3") (pin "2") (pinfunction "2_2") (pintype "passive"))
      (node (ref "EC4") (pin "2") (pinfunction "2_2") (pintype "passive"))
      (node (ref "EC5") (pin "2") (pinfunction "2_2") (pintype "passive"))
      (node (ref "EC6") (pin "2") (pinfunction "2_2") (pintype "passive"))
      (node (ref "J1") (pin "3") (pinfunction "3_3") (pintype "passive"))
      (node (ref "J10") (pin "4") (pinfunction "4_4") (pintype "passive"))
      (node (ref "J13") (pin "4") (pinfunction "GND_4") (pintype "passive"))
      (node (ref "J15") (pin "15") (pinfunction "GND_15") (pintype "passive"))
      (node (ref "J15") (pin "18") (pinfunction "GND_18") (pintype "passive"))
      (node (ref "J15") (pin "21") (pinfunction "GND_21") (pintype "passive"))
      (node (ref "J15") (pin "26") (pinfunction "GND_26") (pintype "passive"))
      (node (ref "J15") (pin "27") (pinfunction "GND_27") (pintype "passive"))
      (node (ref "J15") (pin "29") (pinfunction "GND_29") (pintype "passive"))
      (node (ref "J15") (pin "34") (pinfunction "GND_34") (pintype "passive"))
      (node (ref "J15") (pin "35") (pinfunction "GND_35") (pintype "passive"))
      (node (ref "J15") (pin "37") (pinfunction "GND_37") (pintype "passive"))
      (node (ref "J15") (pin "4") (pinfunction "GND_4") (pintype "passive"))
      (node (ref "J15") (pin "40") (pinfunction "GND_40") (pintype "passive"))
      (node (ref "J15") (pin "43") (pinfunction "GND_43") (pintype "passive"))
      (node (ref "J15") (pin "50") (pinfunction "GND_50") (pintype "passive"))
      (node (ref "J15") (pin "9") (pinfunction "GND_9") (pintype "passive"))
      (node (ref "J4") (pin "5") (pinfunction "5_5") (pintype "passive"))
      (node (ref "J5") (pin "7") (pinfunction "7_7") (pintype "passive"))
      (node (ref "J5") (pin "8") (pinfunction "8_8") (pintype "passive"))
      (node (ref "J6") (pin "2") (pinfunction "2_2") (pintype "passive"))
      (node (ref "J9") (pin "1") (pinfunction "1_1") (pintype "passive"))
      (node (ref "L7") (pin "2") (pinfunction "2_2") (pintype "passive"))
      (node (ref "L8") (pin "2") (pinfunction "2_2") (pintype "passive"))
      (node (ref "Q1") (pin "3") (pinfunction "E_3") (pintype "input"))
      (node (ref "Q2") (pin "3") (pinfunction "E_3") (pintype "input"))
      (node (ref "Q4") (pin "2") (pinfunction "E_2") (pintype "passive"))
      (node (ref "Q5") (pin "3") (pinfunction "E_3") (pintype "input"))
      (node (ref "Q6") (pin "3") (pinfunction "E_3") (pintype "input"))
      (node (ref "Q7") (pin "2") (pinfunction "E_2") (pintype "passive"))
      (node (ref "Q8") (pin "3") (pinfunction "E_3") (pintype "input"))
      (node (ref "Q9") (pin "3") (pinfunction "E_3") (pintype "input"))
      (node (ref "R114") (pin "2") (pintype "passive"))
      (node (ref "R125") (pin "1") (pinfunction "1_1") (pintype "passive"))
      (node (ref "R126") (pin "1") (pinfunction "1_1") (pintype "passive"))
      (node (ref "R127") (pin "1") (pinfunction "1_1") (pintype "passive"))
      (node (ref "R128") (pin "1") (pinfunction "1_1") (pintype "passive"))
      (node (ref "R25") (pin "2") (pintype "passive"))
      (node (ref "R27") (pin "2") (pintype "passive"))
      (node (ref "R35") (pin "1") (pinfunction "1_1") (pintype "passive"))
      (node (ref "R49") (pin "2") (pintype "passive"))
      (node (ref "R50") (pin "1") (pintype "passive"))
      (node (ref "R54") (pin "2") (pinfunction "2_2") (pintype "passive"))
      (node (ref "R55") (pin "2") (pintype "passive"))
      (node (ref "R57") (pin "2") (pintype "passive"))
      (node (ref "R59") (pin "2") (pintype "passive"))
      (node (ref "R60") (pin "2") (pintype "passive"))
      (node (ref "R7") (pin "1") (pinfunction "1_1") (pintype "passive"))
      (node (ref "R88") (pin "1") (pintype "passive"))
      (node (ref "R89") (pin "1") (pintype "passive"))
      (node (ref "R91") (pin "2") (pintype "passive"))
      (node (ref "R94") (pin "1") (pintype "passive"))
      (node (ref "SW2") (pin "1") (pinfunction "COMMON_1") (pintype "passive"))
      (node (ref "SW3") (pin "2") (pinfunction "2_2") (pintype "passive"))
      (node (ref "SW4") (pin "1") (pinfunction "COMMON_1") (pintype "passive"))
      (node (ref "TVS2") (pin "1") (pintype "passive"))
      (node (ref "U1") (pin "103") (pinfunction "VSS_103") (pintype "bidirectional"))
      (node (ref "U1") (pin "117") (pinfunction "VSS_117") (pintype "bidirectional"))
      (node (ref "U1") (pin "119") (pinfunction "VSSREG_119") (pintype "bidirectional"))
      (node (ref "U1") (pin "139") (pinfunction "VSS_139") (pintype "bidirectional"))
      (node (ref "U1") (pin "15") (pinfunction "VSSA_15") (pintype "bidirectional"))
      (node (ref "U1") (pin "22") (pinfunction "VSSREG_22") (pintype "bidirectional"))
      (node (ref "U1") (pin "44") (pinfunction "VSS_44") (pintype "bidirectional"))
      (node (ref "U1") (pin "59") (pinfunction "VSSREG_59") (pintype "bidirectional"))
      (node (ref "U1") (pin "65") (pinfunction "VSS_65") (pintype "bidirectional"))
      (node (ref "U1") (pin "79") (pinfunction "VSS_79") (pintype "bidirectional"))
      (node (ref "U10") (pin "2") (pinfunction "VN_2") (pintype "passive"))
      (node (ref "U13") (pin "4") (pinfunction "VSS_4") (pintype "passive"))
      (node (ref "U14") (pin "4") (pinfunction "GND_4") (pintype "passive"))
      (node (ref "U15") (pin "1") (pinfunction "GND_1") (pintype "passive"))
      (node (ref "U16") (pin "15") (pinfunction "GND_15") (pintype "passive"))
      (node (ref "U17") (pin "10") (pinfunction "GND_10") (pintype "passive"))
      (node (ref "U17") (pin "19") (pinfunction "OE_19") (pintype "passive"))
      (node (ref "U2") (pin "3") (pinfunction "Gnd_3") (pintype "passive"))
      (node (ref "U2") (pin "6") (pinfunction "G_6") (pintype "passive"))
      (node (ref "U3") (pin "15") (pinfunction "GND_15") (pintype "passive"))
      (node (ref "U4") (pin "2") (pinfunction "GND_2") (pintype "passive"))
      (node (ref "U5") (pin "4") (pinfunction "GND_4") (pintype "passive"))
      (node (ref "U6") (pin "3") (pinfunction "GND_3") (pintype "passive"))
      (node (ref "U6") (pin "4") (pinfunction "PFI_4") (pintype "passive"))
      (node (ref "U7") (pin "2") (pinfunction "GND_2") (pintype "passive"))
      (node (ref "U8") (pin "3") (pinfunction "Gnd_3") (pintype "passive"))
      (node (ref "U8") (pin "6") (pinfunction "G_6") (pintype "passive"))
      (node (ref "U9") (pin "14") (pinfunction "AGND_14") (pintype "power_in"))
      (node (ref "U9") (pin "16") (pinfunction "AGND_16") (pintype "power_in"))
      (node (ref "U9") (pin "19") (pinfunction "AGND_19") (pintype "power_in"))
      (node (ref "U9") (pin "29") (pinfunction "GND_29") (pintype "power_in"))
      (node (ref "U9") (pin "3") (pinfunction "AGND_3") (pintype "power_in"))
      (node (ref "U9") (pin "48") (pinfunction "AGND_48") (pintype "power_in"))
      (node (ref "U9") (pin "9") (pinfunction "AGND_9") (pintype "power_in"))
      (node (ref "UG1") (pin "3") (pintype "passive"))
      (node (ref "UG2") (pin "3") (pintype "passive"))
      (node (ref "UG3") (pin "3") (pintype "passive"))
      (node (ref "UG4") (pin "3") (pintype "passive"))
    )
    (net (code "116") (name "DP3V3") (class "Default")
      (node (ref "C1") (pin "1") (pinfunction "1_1") (pintype "passive"))
      (node (ref "C10") (pin "1") (pinfunction "1_1") (pintype "passive"))
      (node (ref "C11") (pin "1") (pinfunction "1_1") (pintype "passive"))
      (node (ref "C12") (pin "2") (pinfunction "2_2") (pintype "passive"))
      (node (ref "C13") (pin "1") (pinfunction "1_1") (pintype "passive"))
      (node (ref "C14") (pin "1") (pinfunction "1_1") (pintype "passive"))
      (node (ref "C15") (pin "1") (pinfunction "1_1") (pintype "passive"))
      (node (ref "C16") (pin "1") (pinfunction "1_1") (pintype "passive"))
      (node (ref "C19") (pin "2") (pintype "passive"))
      (node (ref "C2") (pin "1") (pinfunction "1_1") (pintype "passive"))
      (node (ref "C20") (pin "2") (pintype "passive"))
      (node (ref "C22") (pin "1") (pinfunction "1_1") (pintype "passive"))
      (node (ref "C25") (pin "1") (pintype "passive"))
      (node (ref "C26") (pin "1") (pinfunction "1_1") (pintype "passive"))
      (node (ref "C27") (pin "1") (pinfunction "1_1") (pintype "passive"))
      (node (ref "C3") (pin "1") (pinfunction "1_1") (pintype "passive"))
      (node (ref "C31") (pin "1") (pinfunction "1_1") (pintype "passive"))
      (node (ref "C32") (pin "2") (pintype "passive"))
      (node (ref "C4") (pin "1") (pinfunction "1_1") (pintype "passive"))
      (node (ref "C45") (pin "1") (pinfunction "1_1") (pintype "passive"))
      (node (ref "C48") (pin "1") (pintype "passive"))
      (node (ref "C49") (pin "1") (pintype "passive"))
      (node (ref "C5") (pin "1") (pinfunction "1_1") (pintype "passive"))
      (node (ref "C6") (pin "1") (pinfunction "1_1") (pintype "passive"))
      (node (ref "C7") (pin "1") (pinfunction "1_1") (pintype "passive"))
      (node (ref "C8") (pin "1") (pinfunction "1_1") (pintype "passive"))
      (node (ref "C86") (pin "2") (pintype "passive"))
      (node (ref "C9") (pin "1") (pinfunction "1_1") (pintype "passive"))
      (node (ref "D1") (pin "1") (pintype "passive"))
      (node (ref "D2") (pin "1") (pintype "passive"))
      (node (ref "D3") (pin "1") (pinfunction "A_1") (pintype "passive"))
      (node (ref "D4") (pin "1") (pintype "passive"))
      (node (ref "D5") (pin "1") (pintype "passive"))
      (node (ref "EC1") (pin "1") (pinfunction "1_1") (pintype "passive"))
      (node (ref "EC2") (pin "1") (pinfunction "1_1") (pintype "passive"))
      (node (ref "J1") (pin "4") (pinfunction "4_4") (pintype "passive"))
      (node (ref "J4") (pin "6") (pinfunction "6_6") (pintype "passive"))
      (node (ref "L3") (pin "1") (pinfunction "1_1") (pintype "passive"))
      (node (ref "R1") (pin "2") (pinfunction "2_2") (pintype "passive"))
      (node (ref "R115") (pin "1") (pintype "passive"))
      (node (ref "R130") (pin "1") (pinfunction "1_1") (pintype "passive"))
      (node (ref "R138") (pin "1") (pinfunction "1_1") (pintype "passive"))
      (node (ref "R140") (pin "1") (pinfunction "1_1") (pintype "passive"))
      (node (ref "R142") (pin "1") (pinfunction "1_1") (pintype "passive"))
      (node (ref "R2") (pin "2") (pinfunction "2_2") (pintype "passive"))
      (node (ref "R23") (pin "2") (pintype "passive"))
      (node (ref "R24") (pin "2") (pinfunction "2_2") (pintype "passive"))
      (node (ref "R26") (pin "2") (pinfunction "2_2") (pintype "passive"))
      (node (ref "R28") (pin "1") (pinfunction "1_1") (pintype "passive"))
      (node (ref "R29") (pin "1") (pinfunction "1_1") (pintype "passive"))
      (node (ref "R30") (pin "1") (pinfunction "1_1") (pintype "passive"))
      (node (ref "R45") (pin "1") (pintype "passive"))
      (node (ref "R46") (pin "2") (pintype "passive"))
      (node (ref "R47") (pin "2") (pintype "passive"))
      (node (ref "R48") (pin "2") (pintype "passive"))
      (node (ref "R51") (pin "1") (pintype "passive"))
      (node (ref "R52") (pin "1") (pintype "passive"))
      (node (ref "R53") (pin "1") (pintype "passive"))
      (node (ref "R58") (pin "2") (pinfunction "2_2") (pintype "passive"))
      (node (ref "R6") (pin "2") (pinfunction "2_2") (pintype "passive"))
      (node (ref "R65") (pin "2") (pinfunction "2_2") (pintype "passive"))
      (node (ref "R66") (pin "2") (pinfunction "2_2") (pintype "passive"))
      (node (ref "R67") (pin "2") (pinfunction "2_2") (pintype "passive"))
      (node (ref "R70") (pin "1") (pinfunction "1_1") (pintype "passive"))
      (node (ref "R71") (pin "1") (pinfunction "1_1") (pintype "passive"))
      (node (ref "R74") (pin "1") (pinfunction "1_1") (pintype "passive"))
      (node (ref "R75") (pin "1") (pinfunction "1_1") (pintype "passive"))
      (node (ref "R76") (pin "1") (pinfunction "1_1") (pintype "passive"))
      (node (ref "R77") (pin "1") (pinfunction "1_1") (pintype "passive"))
      (node (ref "R78") (pin "1") (pinfunction "1_1") (pintype "passive"))
      (node (ref "R79") (pin "1") (pinfunction "1_1") (pintype "passive"))
      (node (ref "R80") (pin "1") (pinfunction "1_1") (pintype "passive"))
      (node (ref "R81") (pin "1") (pinfunction "1_1") (pintype "passive"))
      (node (ref "R82") (pin "1") (pinfunction "1_1") (pintype "passive"))
      (node (ref "R83") (pin "1") (pinfunction "1_1") (pintype "passive"))
      (node (ref "R84") (pin "1") (pinfunction "1_1") (pintype "passive"))
      (node (ref "R85") (pin "1") (pinfunction "1_1") (pintype "passive"))
      (node (ref "R90") (pin "2") (pintype "passive"))
      (node (ref "U1") (pin "102") (pinfunction "VDD_102") (pintype "bidirectional"))
      (node (ref "U1") (pin "114") (pinfunction "VDD_114") (pintype "bidirectional"))
      (node (ref "U1") (pin "121") (pinfunction "VDD_121") (pintype "bidirectional"))
      (node (ref "U1") (pin "138") (pinfunction "VDD_138") (pintype "bidirectional"))
      (node (ref "U1") (pin "14") (pinfunction "VDDA_14") (pintype "bidirectional"))
      (node (ref "U1") (pin "17") (pinfunction "VREFP_17") (pintype "bidirectional"))
      (node (ref "U1") (pin "18") (pinfunction "VDD_18") (pintype "bidirectional"))
      (node (ref "U1") (pin "41") (pinfunction "VDD_41") (pintype "bidirectional"))
      (node (ref "U1") (pin "60") (pinfunction "VDD_60") (pintype "bidirectional"))
      (node (ref "U1") (pin "62") (pinfunction "VDD_62") (pintype "bidirectional"))
      (node (ref "U1") (pin "77") (pinfunction "VDD_77") (pintype "bidirectional"))
      (node (ref "U10") (pin "5") (pinfunction "VP_5") (pintype "passive"))
      (node (ref "U13") (pin "8") (pinfunction "VDD_8") (pintype "passive"))
      (node (ref "U14") (pin "8") (pinfunction "VCC_8") (pintype "passive"))
      (node (ref "U16") (pin "16") (pinfunction "VCC_16") (pintype "passive"))
      (node (ref "U17") (pin "1") (pinfunction "DIR_1") (pintype "passive"))
      (node (ref "U17") (pin "20") (pinfunction "VCC_20") (pintype "passive"))
      (node (ref "U2") (pin "4") (pinfunction "Vout_4") (pintype "passive"))
      (node (ref "U3") (pin "16") (pinfunction "VCC_16") (pintype "passive"))
      (node (ref "U4") (pin "1") (pinfunction "VCC_1") (pintype "passive"))
      (node (ref "U6") (pin "2") (pinfunction "VCC_2") (pintype "passive"))
      (node (ref "U7") (pin "1") (pinfunction "VCC_1") (pintype "passive"))
      (node (ref "U9") (pin "28") (pinfunction "VCC_28") (pintype "power_in"))
    )
    (net (code "117") (name "EGND") (class "Default")
      (node (ref "U12") (pin "13") (pinfunction "SHIELD_13") (pintype "passive"))
    )
    (net (code "118") (name "EGND1") (class "Default")
      (node (ref "U12") (pin "14") (pinfunction "SHIELD_14") (pintype "passive"))
    )
    (net (code "119") (name "FG") (class "Default")
      (node (ref "C72") (pin "2") (pinfunction "2_2") (pintype "passive"))
      (node (ref "J2") (pin "3") (pinfunction "3_3") (pintype "passive"))
      (node (ref "R116") (pin "2") (pinfunction "2_2") (pintype "passive"))
    )
    (net (code "120") (name "IGND") (class "Default")
      (node (ref "J14") (pin "2") (pinfunction "2_2") (pintype "passive"))
      (node (ref "J14") (pin "4") (pinfunction "4_4") (pintype "passive"))
      (node (ref "J14") (pin "6") (pinfunction "6_6") (pintype "passive"))
      (node (ref "J14") (pin "8") (pinfunction "8_8") (pintype "passive"))
      (node (ref "R102") (pin "2") (pintype "passive"))
    )
    (net (code "121") (name "Net-(BAT1-Pad1)") (class "Default")
      (node (ref "BAT1") (pin "1") (pinfunction "1_1") (pintype "passive"))
      (node (ref "D3") (pin "3") (pinfunction "A_3") (pintype "passive"))
    )
    (net (code "122") (name "Net-(C30-Pad2)") (class "Default")
      (node (ref "C30") (pin "2") (pinfunction "2_2") (pintype "passive"))
      (node (ref "R36") (pin "2") (pinfunction "2_2") (pintype "passive"))
      (node (ref "TVS5") (pin "1") (pintype "passive"))
    )
    (net (code "123") (name "Net-(C63-Pad1)") (class "Default")
      (node (ref "C63") (pin "1") (pintype "passive"))
      (node (ref "R137") (pin "2") (pinfunction "2_2") (pintype "passive"))
      (node (ref "UG2") (pin "1") (pintype "passive"))
    )
    (net (code "124") (name "Net-(C65-Pad1)") (class "Default")
      (node (ref "C65") (pin "1") (pintype "passive"))
      (node (ref "R129") (pin "2") (pinfunction "2_2") (pintype "passive"))
      (node (ref "UG1") (pin "1") (pintype "passive"))
    )
    (net (code "125") (name "Net-(C82-Pad1)") (class "Default")
      (node (ref "C82") (pin "1") (pintype "passive"))
      (node (ref "R141") (pin "2") (pinfunction "2_2") (pintype "passive"))
      (node (ref "UG4") (pin "1") (pintype "passive"))
    )
    (net (code "126") (name "Net-(C84-Pad1)") (class "Default")
      (node (ref "C84") (pin "1") (pintype "passive"))
      (node (ref "R139") (pin "2") (pinfunction "2_2") (pintype "passive"))
      (node (ref "UG3") (pin "1") (pintype "passive"))
    )
    (net (code "127") (name "Net-(C90-Pad2)") (class "Default")
      (node (ref "C90") (pin "2") (pintype "passive"))
      (node (ref "R27") (pin "1") (pintype "passive"))
    )
    (net (code "128") (name "Net-(D1-Pad2)") (class "Default")
      (node (ref "D1") (pin "2") (pintype "passive"))
      (node (ref "R21") (pin "1") (pintype "passive"))
    )
    (net (code "129") (name "Net-(D2-Pad2)") (class "Default")
      (node (ref "D2") (pin "2") (pintype "passive"))
      (node (ref "R20") (pin "1") (pintype "passive"))
    )
    (net (code "130") (name "Net-(D3-K)") (class "Default")
      (node (ref "D3") (pin "2") (pinfunction "K_2") (pintype "passive"))
      (node (ref "R8") (pin "1") (pinfunction "1_1") (pintype "passive"))
    )
    (net (code "131") (name "Net-(D4-Pad2)") (class "Default")
      (node (ref "D4") (pin "2") (pintype "passive"))
      (node (ref "R39") (pin "1") (pinfunction "1_1") (pintype "passive"))
    )
    (net (code "132") (name "Net-(D5-Pad2)") (class "Default")
      (node (ref "D5") (pin "2") (pintype "passive"))
      (node (ref "R37") (pin "1") (pinfunction "1_1") (pintype "passive"))
    )
    (net (code "133") (name "Net-(D6-A)") (class "Default")
      (node (ref "D6") (pin "1") (pinfunction "A_1") (pintype "passive"))
      (node (ref "Q2") (pin "2") (pinfunction "C_2") (pintype "input"))
      (node (ref "U11") (pin "2") (pinfunction "B_2") (pintype "passive"))
    )
    (net (code "134") (name "Net-(D6-K)") (class "Default")
      (node (ref "D6") (pin "2") (pinfunction "K_2") (pintype "passive"))
      (node (ref "R56") (pin "1") (pintype "passive"))
      (node (ref "U11") (pin "1") (pinfunction "A_1") (pintype "passive"))
    )
    (net (code "135") (name "Net-(D7-A)") (class "Default")
      (node (ref "D7") (pin "1") (pinfunction "A_1") (pintype "passive"))
      (node (ref "R40") (pin "1") (pintype "passive"))
      (node (ref "R44") (pin "2") (pintype "passive"))
    )
    (net (code "136") (name "Net-(D12-A)") (class "Default")
      (node (ref "C73") (pin "2") (pintype "passive"))
      (node (ref "D12") (pin "1") (pinfunction "A_1") (pintype "passive"))
      (node (ref "LED3") (pin "2") (pintype "passive"))
      (node (ref "Q5") (pin "2") (pinfunction "C_2") (pintype "input"))
      (node (ref "RL1") (pin "1") (pinfunction "+_1") (pintype "passive"))
    )
    (net (code "137") (name "Net-(D15-A)") (class "Default")
      (node (ref "C74") (pin "1") (pinfunction "1_1") (pintype "passive"))
      (node (ref "D15") (pin "1") (pinfunction "A_1") (pintype "passive"))
      (node (ref "LED4") (pin "2") (pintype "passive"))
      (node (ref "Q6") (pin "2") (pinfunction "C_2") (pintype "input"))
      (node (ref "RL2") (pin "1") (pinfunction "+_1") (pintype "passive"))
    )
    (net (code "138") (name "Net-(D17-A)") (class "Default")
      (node (ref "C76") (pin "2") (pintype "passive"))
      (node (ref "D17") (pin "1") (pinfunction "A_1") (pintype "passive"))
      (node (ref "LED6") (pin "2") (pintype "passive"))
      (node (ref "Q8") (pin "2") (pinfunction "C_2") (pintype "input"))
      (node (ref "RL4") (pin "1") (pinfunction "+_1") (pintype "passive"))
    )
    (net (code "139") (name "Net-(D20-A)") (class "Default")
      (node (ref "C75") (pin "1") (pinfunction "1_1") (pintype "passive"))
      (node (ref "D20") (pin "1") (pinfunction "A_1") (pintype "passive"))
      (node (ref "LED7") (pin "2") (pintype "passive"))
      (node (ref "Q9") (pin "2") (pinfunction "C_2") (pintype "input"))
      (node (ref "RL3") (pin "1") (pinfunction "+_1") (pintype "passive"))
    )
    (net (code "140") (name "Net-(J5-Pad1)") (class "Default")
      (node (ref "J5") (pin "1") (pinfunction "1_1") (pintype "passive"))
      (node (ref "J5") (pin "2") (pinfunction "2_2") (pintype "passive"))
      (node (ref "L4") (pin "2") (pintype "passive"))
      (node (ref "L5") (pin "1") (pintype "passive"))
    )
    (net (code "141") (name "Net-(J13-CLK)") (class "Default")
      (node (ref "C68") (pin "1") (pinfunction "1_1") (pintype "passive"))
      (node (ref "J13") (pin "3") (pinfunction "CLK_3") (pintype "passive"))
      (node (ref "R100") (pin "1") (pintype "passive"))
    )
    (net (code "142") (name "Net-(J13-I{slash}O)") (class "Default")
      (node (ref "C69") (pin "1") (pinfunction "1_1") (pintype "passive"))
      (node (ref "J13") (pin "6") (pinfunction "I/O_6") (pintype "passive"))
      (node (ref "R97") (pin "1") (pintype "passive"))
      (node (ref "R99") (pin "1") (pintype "passive"))
    )
    (net (code "143") (name "Net-(J13-RST)") (class "Default")
      (node (ref "C70") (pin "1") (pinfunction "1_1") (pintype "passive"))
      (node (ref "J13") (pin "2") (pinfunction "RST_2") (pintype "passive"))
      (node (ref "R98") (pin "1") (pintype "passive"))
    )
    (net (code "144") (name "Net-(J15-LED_WWAN)") (class "Default")
      (node (ref "J15") (pin "42") (pinfunction "LED_WWAN_42") (pintype "passive"))
      (node (ref "LED5") (pin "2") (pintype "passive"))
    )
    (net (code "145") (name "Net-(LED1-Pad1)") (class "Default")
      (node (ref "LED1") (pin "1") (pintype "passive"))
      (node (ref "R24") (pin "1") (pinfunction "1_1") (pintype "passive"))
    )
    (net (code "146") (name "Net-(LED2-Pad1)") (class "Default")
      (node (ref "LED2") (pin "1") (pintype "passive"))
      (node (ref "R90") (pin "1") (pintype "passive"))
    )
    (net (code "147") (name "Net-(LED3-Pad1)") (class "Default")
      (node (ref "LED3") (pin "1") (pintype "passive"))
      (node (ref "R117") (pin "1") (pinfunction "1_1") (pintype "passive"))
    )
    (net (code "148") (name "Net-(LED4-Pad1)") (class "Default")
      (node (ref "LED4") (pin "1") (pintype "passive"))
      (node (ref "R118") (pin "1") (pinfunction "1_1") (pintype "passive"))
    )
    (net (code "149") (name "Net-(LED5-Pad1)") (class "Default")
      (node (ref "LED5") (pin "1") (pintype "passive"))
      (node (ref "R103") (pin "2") (pintype "passive"))
    )
    (net (code "150") (name "Net-(LED6-Pad1)") (class "Default")
      (node (ref "LED6") (pin "1") (pintype "passive"))
      (node (ref "R120") (pin "1") (pinfunction "1_1") (pintype "passive"))
    )
    (net (code "151") (name "Net-(LED7-Pad1)") (class "Default")
      (node (ref "LED7") (pin "1") (pintype "passive"))
      (node (ref "R119") (pin "1") (pinfunction "1_1") (pintype "passive"))
    )
    (net (code "152") (name "Net-(Q1-B)") (class "Default")
      (node (ref "Q1") (pin "1") (pinfunction "B_1") (pintype "input"))
      (node (ref "R34") (pin "2") (pinfunction "2_2") (pintype "passive"))
      (node (ref "R35") (pin "2") (pinfunction "2_2") (pintype "passive"))
    )
    (net (code "153") (name "Net-(Q1-C)") (class "Default")
      (node (ref "LED1") (pin "2") (pintype "passive"))
      (node (ref "Q1") (pin "2") (pinfunction "C_2") (pintype "input"))
    )
    (net (code "154") (name "Net-(Q2-B)") (class "Default")
      (node (ref "Q2") (pin "1") (pinfunction "B_1") (pintype "input"))
      (node (ref "R62") (pin "1") (pintype "passive"))
    )
    (net (code "155") (name "Net-(Q3-B)") (class "Default")
      (node (ref "Q3") (pin "1") (pinfunction "B_1") (pintype "passive"))
      (node (ref "R41") (pin "1") (pintype "passive"))
    )
    (net (code "156") (name "Net-(Q3-E)") (class "Default")
      (node (ref "Q3") (pin "2") (pinfunction "E_2") (pintype "passive"))
      (node (ref "R92") (pin "1") (pintype "passive"))
    )
    (net (code "157") (name "Net-(Q4-B)") (class "Default")
      (node (ref "Q4") (pin "1") (pinfunction "B_1") (pintype "passive"))
      (node (ref "R93") (pin "2") (pintype "passive"))
      (node (ref "R94") (pin "2") (pintype "passive"))
    )
    (net (code "158") (name "Net-(Q4-C)") (class "Default")
      (node (ref "Q4") (pin "3") (pinfunction "C_3") (pintype "passive"))
      (node (ref "R42") (pin "1") (pintype "passive"))
      (node (ref "U8") (pin "1") (pinfunction "EN_1") (pintype "passive"))
    )
    (net (code "159") (name "Net-(Q5-B)") (class "Default")
      (node (ref "C77") (pin "1") (pintype "passive"))
      (node (ref "Q5") (pin "1") (pinfunction "B_1") (pintype "input"))
      (node (ref "R121") (pin "2") (pinfunction "2_2") (pintype "passive"))
      (node (ref "R125") (pin "2") (pinfunction "2_2") (pintype "passive"))
    )
    (net (code "160") (name "Net-(Q6-B)") (class "Default")
      (node (ref "C78") (pin "2") (pinfunction "2_2") (pintype "passive"))
      (node (ref "Q6") (pin "1") (pinfunction "B_1") (pintype "input"))
      (node (ref "R122") (pin "2") (pinfunction "2_2") (pintype "passive"))
      (node (ref "R126") (pin "2") (pinfunction "2_2") (pintype "passive"))
    )
    (net (code "161") (name "Net-(Q7-B)") (class "Default")
      (node (ref "C71") (pin "1") (pinfunction "1_1") (pintype "passive"))
      (node (ref "Q7") (pin "1") (pinfunction "B_1") (pintype "passive"))
      (node (ref "R110") (pin "1") (pintype "passive"))
      (node (ref "R114") (pin "1") (pintype "passive"))
    )
    (net (code "162") (name "Net-(Q8-B)") (class "Default")
      (node (ref "C80") (pin "1") (pintype "passive"))
      (node (ref "Q8") (pin "1") (pinfunction "B_1") (pintype "input"))
      (node (ref "R124") (pin "2") (pinfunction "2_2") (pintype "passive"))
      (node (ref "R128") (pin "2") (pinfunction "2_2") (pintype "passive"))
    )
    (net (code "163") (name "Net-(Q9-B)") (class "Default")
      (node (ref "C79") (pin "2") (pinfunction "2_2") (pintype "passive"))
      (node (ref "Q9") (pin "1") (pinfunction "B_1") (pintype "input"))
      (node (ref "R123") (pin "2") (pinfunction "2_2") (pintype "passive"))
      (node (ref "R127") (pin "2") (pinfunction "2_2") (pintype "passive"))
    )
    (net (code "164") (name "Net-(R3-Pad2)") (class "Default")
      (node (ref "R3") (pin "2") (pintype "passive"))
      (node (ref "R4") (pin "1") (pintype "passive"))
    )
    (net (code "165") (name "Net-(R10-Pad2)") (class "Default")
      (node (ref "R10") (pin "2") (pintype "passive"))
      (node (ref "TVS3") (pin "1") (pintype "passive"))
    )
    (net (code "166") (name "Net-(SW1-COMMON)") (class "Default")
      (node (ref "C26") (pin "2") (pinfunction "2_2") (pintype "passive"))
      (node (ref "R26") (pin "1") (pinfunction "1_1") (pintype "passive"))
      (node (ref "SW1") (pin "1") (pinfunction "COMMON_1") (pintype "passive"))
      (node (ref "SW3") (pin "1") (pinfunction "1_1") (pintype "passive"))
      (node (ref "U6") (pin "1") (pinfunction "~{MR}_1") (pintype "passive"))
    )
    (net (code "167") (name "Net-(SW1-NO)") (class "Default")
      (node (ref "SW1") (pin "2") (pinfunction "NO_2") (pintype "passive"))
      (node (ref "U6") (pin "8") (pinfunction "~{WDO}_8") (pintype "passive"))
    )
    (net (code "168") (name "Net-(U1-VBAT)") (class "Default")
      (node (ref "R8") (pin "2") (pinfunction "2_2") (pintype "passive"))
      (node (ref "U1") (pin "27") (pinfunction "VBAT_27") (pintype "bidirectional"))
    )
    (net (code "169") (name "Net-(U2-Adj)") (class "Default")
      (node (ref "R6") (pin "1") (pinfunction "1_1") (pintype "passive"))
      (node (ref "R7") (pin "2") (pinfunction "2_2") (pintype "passive"))
      (node (ref "U2") (pin "5") (pinfunction "Adj_5") (pintype "passive"))
    )
    (net (code "170") (name "Net-(U2-EN)") (class "Default")
      (node (ref "R5") (pin "2") (pinfunction "2_2") (pintype "passive"))
      (node (ref "U2") (pin "1") (pinfunction "EN_1") (pintype "passive"))
    )
    (net (code "171") (name "Net-(U3-C-)") (class "Default")
      (node (ref "C18") (pin "1") (pintype "passive"))
      (node (ref "U3") (pin "3") (pinfunction "C-_3") (pintype "passive"))
    )
    (net (code "172") (name "Net-(U3-C1+)") (class "Default")
      (node (ref "C18") (pin "2") (pintype "passive"))
      (node (ref "U3") (pin "1") (pinfunction "C1+_1") (pintype "passive"))
    )
    (net (code "173") (name "Net-(U3-C2+)") (class "Default")
      (node (ref "C23") (pin "2") (pintype "passive"))
      (node (ref "U3") (pin "4") (pinfunction "C2+_4") (pintype "passive"))
    )
    (net (code "174") (name "Net-(U3-C2-)") (class "Default")
      (node (ref "C23") (pin "1") (pintype "passive"))
      (node (ref "U3") (pin "5") (pinfunction "C2-_5") (pintype "passive"))
    )
    (net (code "175") (name "Net-(U3-R1IN)") (class "Default")
      (node (ref "R12") (pin "1") (pintype "passive"))
      (node (ref "U3") (pin "13") (pinfunction "R1IN_13") (pintype "passive"))
    )
    (net (code "176") (name "Net-(U3-R1OUT)") (class "Default")
      (node (ref "R11") (pin "2") (pintype "passive"))
      (node (ref "U3") (pin "12") (pinfunction "R1OUT_12") (pintype "passive"))
    )
    (net (code "177") (name "Net-(U3-R2IN)") (class "Default")
      (node (ref "R14") (pin "1") (pintype "passive"))
      (node (ref "U3") (pin "8") (pinfunction "R2IN_8") (pintype "passive"))
    )
    (net (code "178") (name "Net-(U3-R2OUT)") (class "Default")
      (node (ref "R13") (pin "2") (pintype "passive"))
      (node (ref "U3") (pin "9") (pinfunction "R2OUT_9") (pintype "passive"))
    )
    (net (code "179") (name "Net-(U3-T1IN)") (class "Default")
      (node (ref "R15") (pin "2") (pintype "passive"))
      (node (ref "U3") (pin "11") (pinfunction "T1IN_11") (pintype "passive"))
    )
    (net (code "180") (name "Net-(U3-T1OUT)") (class "Default")
      (node (ref "R16") (pin "1") (pintype "passive"))
      (node (ref "U3") (pin "14") (pinfunction "T1OUT_14") (pintype "passive"))
    )
    (net (code "181") (name "Net-(U3-T2IN)") (class "Default")
      (node (ref "R17") (pin "2") (pintype "passive"))
      (node (ref "U3") (pin "10") (pinfunction "T2IN_10") (pintype "passive"))
    )
    (net (code "182") (name "Net-(U3-T2OUT)") (class "Default")
      (node (ref "R18") (pin "1") (pintype "passive"))
      (node (ref "U3") (pin "7") (pinfunction "T2OUT_7") (pintype "passive"))
    )
    (net (code "183") (name "Net-(U3-V+)") (class "Default")
      (node (ref "C19") (pin "1") (pintype "passive"))
      (node (ref "U3") (pin "2") (pinfunction "V+_2") (pintype "passive"))
    )
    (net (code "184") (name "Net-(U3-V-)") (class "Default")
      (node (ref "C24") (pin "2") (pintype "passive"))
      (node (ref "U3") (pin "6") (pinfunction "V-_6") (pintype "passive"))
    )
    (net (code "185") (name "Net-(U4-CANH{slash}485B)") (class "Default")
      (node (ref "R22") (pin "1") (pintype "passive"))
      (node (ref "U4") (pin "8") (pinfunction "CANH/485B_8") (pintype "passive"))
    )
    (net (code "186") (name "Net-(U4-CANL{slash}485A)") (class "Default")
      (node (ref "R19") (pin "1") (pintype "passive"))
      (node (ref "U4") (pin "9") (pinfunction "CANL/485A_9") (pintype "passive"))
    )
    (net (code "187") (name "Net-(U4-RG)") (class "Default")
      (node (ref "R10") (pin "1") (pintype "passive"))
      (node (ref "U4") (pin "10") (pinfunction "RG_10") (pintype "passive"))
    )
    (net (code "188") (name "Net-(U5-BS)") (class "Default")
      (node (ref "C89") (pin "2") (pintype "passive"))
      (node (ref "U5") (pin "1") (pinfunction "BS_1") (pintype "passive"))
    )
    (net (code "189") (name "Net-(U5-FB)") (class "Default")
      (node (ref "R25") (pin "1") (pintype "passive"))
      (node (ref "R4") (pin "2") (pintype "passive"))
      (node (ref "U5") (pin "5") (pinfunction "FB_5") (pintype "passive"))
    )
    (net (code "190") (name "Net-(U5-comp)") (class "Default")
      (node (ref "C90") (pin "1") (pintype "passive"))
      (node (ref "U5") (pin "6") (pinfunction "comp_6") (pintype "passive"))
    )
    (net (code "191") (name "Net-(U6-~{RST})") (class "Default")
      (node (ref "C28") (pin "2") (pinfunction "2_2") (pintype "passive"))
      (node (ref "R29") (pin "2") (pinfunction "2_2") (pintype "passive"))
      (node (ref "R33") (pin "1") (pinfunction "1_1") (pintype "passive"))
      (node (ref "U6") (pin "7") (pinfunction "~{RST}_7") (pintype "passive"))
    )
    (net (code "192") (name "Net-(U7-RG)") (class "Default")
      (node (ref "C30") (pin "1") (pinfunction "1_1") (pintype "passive"))
      (node (ref "R36") (pin "1") (pinfunction "1_1") (pintype "passive"))
      (node (ref "U7") (pin "8") (pinfunction "RG_8") (pintype "passive"))
    )
    (net (code "193") (name "Net-(U8-Adj)") (class "Default")
      (node (ref "R43") (pin "1") (pintype "passive"))
      (node (ref "R91") (pin "1") (pintype "passive"))
      (node (ref "U8") (pin "5") (pinfunction "Adj_5") (pintype "passive"))
    )
    (net (code "194") (name "Net-(U8-Vout)") (class "Default")
      (node (ref "C61") (pin "1") (pinfunction "1_1") (pintype "passive"))
      (node (ref "L6") (pin "1") (pinfunction "1_1") (pintype "passive"))
      (node (ref "R43") (pin "2") (pintype "passive"))
      (node (ref "U8") (pin "4") (pinfunction "Vout_4") (pintype "passive"))
    )
    (net (code "195") (name "Net-(U9A-EXRES1)") (class "Default")
      (node (ref "R54") (pin "1") (pinfunction "1_1") (pintype "passive"))
      (node (ref "U9") (pin "10") (pinfunction "EXRES1_10") (pintype "bidirectional"))
    )
    (net (code "196") (name "Net-(U9A-XI{slash}CLKIN)") (class "Default")
      (node (ref "C38") (pin "1") (pintype "passive"))
      (node (ref "R61") (pin "1") (pinfunction "1_1") (pintype "passive"))
      (node (ref "U9") (pin "30") (pinfunction "XI/CLKIN_30") (pintype "input"))
      (node (ref "Y3") (pin "1") (pinfunction "1_1") (pintype "passive"))
    )
    (net (code "197") (name "Net-(U9A-XO)") (class "Default")
      (node (ref "C42") (pin "1") (pintype "passive"))
      (node (ref "R61") (pin "2") (pinfunction "2_2") (pintype "passive"))
      (node (ref "U9") (pin "31") (pinfunction "XO_31") (pintype "output"))
      (node (ref "Y3") (pin "2") (pinfunction "2_2") (pintype "passive"))
    )
    (net (code "198") (name "Net-(U9B-1V2O)") (class "Default")
      (node (ref "C39") (pin "2") (pintype "passive"))
      (node (ref "U9") (pin "22") (pinfunction "1V2O_22") (pintype "power_in"))
    )
    (net (code "199") (name "Net-(U9B-TOCAP)") (class "Default")
      (node (ref "C43") (pin "1") (pinfunction "1_1") (pintype "passive"))
      (node (ref "U9") (pin "20") (pinfunction "TOCAP_20") (pintype "output"))
    )
    (net (code "200") (name "Net-(U12-GRN+)") (class "Default")
      (node (ref "R70") (pin "2") (pinfunction "2_2") (pintype "passive"))
      (node (ref "U12") (pin "9") (pinfunction "GRN+_9") (pintype "passive"))
    )
    (net (code "201") (name "Net-(U12-RCT)") (class "Default")
      (node (ref "C59") (pin "1") (pintype "passive"))
      (node (ref "R68") (pin "1") (pinfunction "1_1") (pintype "passive"))
      (node (ref "R69") (pin "1") (pinfunction "1_1") (pintype "passive"))
      (node (ref "U12") (pin "6") (pinfunction "RCT_6") (pintype "passive"))
    )
    (net (code "202") (name "Net-(U12-RD+)") (class "Default")
      (node (ref "C47") (pin "2") (pintype "passive"))
      (node (ref "U12") (pin "7") (pinfunction "RD+_7") (pintype "passive"))
    )
    (net (code "203") (name "Net-(U12-RD-)") (class "Default")
      (node (ref "C51") (pin "2") (pintype "passive"))
      (node (ref "U12") (pin "8") (pinfunction "RD-_8") (pintype "passive"))
    )
    (net (code "204") (name "Net-(U12-TCT)") (class "Default")
      (node (ref "C44") (pin "2") (pintype "passive"))
      (node (ref "R67") (pin "1") (pinfunction "1_1") (pintype "passive"))
      (node (ref "U12") (pin "3") (pinfunction "TCT_3") (pintype "passive"))
    )
    (net (code "205") (name "Net-(U12-YEL+)") (class "Default")
      (node (ref "R71") (pin "2") (pinfunction "2_2") (pintype "passive"))
      (node (ref "U12") (pin "12") (pinfunction "YEL+_12") (pintype "passive"))
    )
    (net (code "206") (name "Net-(U13-~{HOLD})") (class "Default")
      (node (ref "R77") (pin "2") (pinfunction "2_2") (pintype "passive"))
      (node (ref "U13") (pin "7") (pinfunction "~{HOLD}_7") (pintype "passive"))
    )
    (net (code "207") (name "Net-(U13-~{WP})") (class "Default")
      (node (ref "R74") (pin "2") (pinfunction "2_2") (pintype "passive"))
      (node (ref "U13") (pin "3") (pinfunction "~{WP}_3") (pintype "passive"))
    )
    (net (code "208") (name "Net-(U14-NC)") (class "Default")
      (node (ref "R83") (pin "2") (pinfunction "2_2") (pintype "passive"))
      (node (ref "U14") (pin "7") (pinfunction "NC_7") (pintype "passive"))
    )
    (net (code "209") (name "Net-(U14-~{WP})") (class "Default")
      (node (ref "R80") (pin "2") (pinfunction "2_2") (pintype "passive"))
      (node (ref "U14") (pin "3") (pinfunction "~{WP}_3") (pintype "passive"))
    )
    (net (code "210") (name "Net-(U15-I{slash}O1)") (class "Default")
      (node (ref "J10") (pin "3") (pinfunction "3_3") (pintype "passive"))
      (node (ref "R87") (pin "1") (pintype "passive"))
      (node (ref "R89") (pin "2") (pintype "passive"))
      (node (ref "U15") (pin "2") (pinfunction "I/O1_2") (pintype "passive"))
    )
    (net (code "211") (name "Net-(U15-I{slash}O2)") (class "Default")
      (node (ref "J10") (pin "2") (pinfunction "2_2") (pintype "passive"))
      (node (ref "R86") (pin "1") (pintype "passive"))
      (node (ref "R88") (pin "2") (pintype "passive"))
      (node (ref "U15") (pin "3") (pinfunction "I/O2_3") (pintype "passive"))
    )
    (net (code "212") (name "Net-(U15-VCC)") (class "Default")
      (node (ref "F1") (pin "2") (pinfunction "2_2") (pintype "passive"))
      (node (ref "J10") (pin "1") (pinfunction "1_1") (pintype "passive"))
      (node (ref "U15") (pin "4") (pinfunction "VCC_4") (pintype "passive"))
    )
    (net (code "213") (name "Net-(U16-C-)") (class "Default")
      (node (ref "C85") (pin "1") (pintype "passive"))
      (node (ref "U16") (pin "3") (pinfunction "C-_3") (pintype "passive"))
    )
    (net (code "214") (name "Net-(U16-C1+)") (class "Default")
      (node (ref "C85") (pin "2") (pintype "passive"))
      (node (ref "U16") (pin "1") (pinfunction "C1+_1") (pintype "passive"))
    )
    (net (code "215") (name "Net-(U16-C2+)") (class "Default")
      (node (ref "C87") (pin "2") (pintype "passive"))
      (node (ref "U16") (pin "4") (pinfunction "C2+_4") (pintype "passive"))
    )
    (net (code "216") (name "Net-(U16-C2-)") (class "Default")
      (node (ref "C87") (pin "1") (pintype "passive"))
      (node (ref "U16") (pin "5") (pinfunction "C2-_5") (pintype "passive"))
    )
    (net (code "217") (name "Net-(U16-R1IN)") (class "Default")
      (node (ref "R145") (pin "1") (pintype "passive"))
      (node (ref "U16") (pin "13") (pinfunction "R1IN_13") (pintype "passive"))
    )
    (net (code "218") (name "Net-(U16-R1OUT)") (class "Default")
      (node (ref "R143") (pin "2") (pintype "passive"))
      (node (ref "U16") (pin "12") (pinfunction "R1OUT_12") (pintype "passive"))
    )
    (net (code "219") (name "Net-(U16-T1IN)") (class "Default")
      (node (ref "R144") (pin "2") (pintype "passive"))
      (node (ref "U16") (pin "11") (pinfunction "T1IN_11") (pintype "passive"))
    )
    (net (code "220") (name "Net-(U16-T1OUT)") (class "Default")
      (node (ref "R146") (pin "1") (pintype "passive"))
      (node (ref "U16") (pin "14") (pinfunction "T1OUT_14") (pintype "passive"))
    )
    (net (code "221") (name "Net-(U16-V+)") (class "Default")
      (node (ref "C86") (pin "1") (pintype "passive"))
      (node (ref "U16") (pin "2") (pinfunction "V+_2") (pintype "passive"))
    )
    (net (code "222") (name "Net-(U16-V-)") (class "Default")
      (node (ref "C88") (pin "2") (pintype "passive"))
      (node (ref "U16") (pin "6") (pinfunction "V-_6") (pintype "passive"))
    )
    (net (code "223") (name "Net-(U17-A0)") (class "Default")
      (node (ref "R63") (pin "2") (pintype "passive"))
      (node (ref "U17") (pin "2") (pinfunction "A0_2") (pintype "passive"))
    )
    (net (code "224") (name "Net-(U17-A1)") (class "Default")
      (node (ref "R64") (pin "2") (pintype "passive"))
      (node (ref "U17") (pin "3") (pinfunction "A1_3") (pintype "passive"))
    )
    (net (code "225") (name "Net-(U17-A3)") (class "Default")
      (node (ref "R31") (pin "2") (pintype "passive"))
      (node (ref "U17") (pin "5") (pinfunction "A3_5") (pintype "passive"))
    )
    (net (code "226") (name "Net-(U17-A6)") (class "Default")
      (node (ref "R32") (pin "2") (pintype "passive"))
      (node (ref "U17") (pin "8") (pinfunction "A6_8") (pintype "passive"))
    )
    (net (code "227") (name "SGND") (class "Default")
      (node (ref "C72") (pin "1") (pinfunction "1_1") (pintype "passive"))
      (node (ref "J2") (pin "2") (pinfunction "2_2") (pintype "passive"))
      (node (ref "L7") (pin "1") (pinfunction "1_1") (pintype "passive"))
      (node (ref "L8") (pin "1") (pinfunction "1_1") (pintype "passive"))
      (node (ref "R102") (pin "1") (pintype "passive"))
      (node (ref "R116") (pin "1") (pinfunction "1_1") (pintype "passive"))
    )
    (net (code "228") (name "VCC33A") (class "Default")
      (node (ref "C46") (pin "1") (pinfunction "1_1") (pintype "passive"))
      (node (ref "C50") (pin "1") (pintype "passive"))
      (node (ref "C53") (pin "1") (pintype "passive"))
      (node (ref "C54") (pin "1") (pintype "passive"))
      (node (ref "C55") (pin "1") (pintype "passive"))
      (node (ref "C56") (pin "1") (pintype "passive"))
      (node (ref "C57") (pin "1") (pintype "passive"))
      (node (ref "C58") (pin "1") (pintype "passive"))
      (node (ref "L3") (pin "2") (pinfunction "2_2") (pintype "passive"))
      (node (ref "U9") (pin "11") (pinfunction "AVCC_11") (pintype "power_in"))
      (node (ref "U9") (pin "15") (pinfunction "AVCC_15") (pintype "power_in"))
      (node (ref "U9") (pin "17") (pinfunction "AVCC_17") (pintype "power_in"))
      (node (ref "U9") (pin "21") (pinfunction "AVCC_21") (pintype "power_in"))
      (node (ref "U9") (pin "4") (pinfunction "AVCC_4") (pintype "power_in"))
      (node (ref "U9") (pin "8") (pinfunction "AVCC_8") (pintype "power_in"))
    )
    (net (code "229") (name "VDD5V") (class "Default")
      (node (ref "C17") (pin "2") (pintype "passive"))
      (node (ref "C21") (pin "2") (pintype "passive"))
      (node (ref "EC4") (pin "1") (pinfunction "1_1") (pintype "passive"))
      (node (ref "F1") (pin "1") (pinfunction "1_1") (pintype "passive"))
      (node (ref "J6") (pin "1") (pinfunction "1_1") (pintype "passive"))
      (node (ref "J9") (pin "4") (pinfunction "4_4") (pintype "passive"))
      (node (ref "L4") (pin "1") (pintype "passive"))
      (node (ref "L9") (pin "2") (pinfunction "2_2") (pintype "passive"))
      (node (ref "R3") (pin "1") (pintype "passive"))
      (node (ref "R42") (pin "2") (pintype "passive"))
      (node (ref "R5") (pin "1") (pinfunction "1_1") (pintype "passive"))
      (node (ref "R56") (pin "2") (pintype "passive"))
      (node (ref "U2") (pin "2") (pinfunction "Vin_2") (pintype "passive"))
      (node (ref "U8") (pin "2") (pinfunction "Vin_2") (pintype "passive"))
    )
    (net (code "230") (name "VDD12V") (class "Default")
      (node (ref "C73") (pin "1") (pintype "passive"))
      (node (ref "C74") (pin "2") (pinfunction "2_2") (pintype "passive"))
      (node (ref "C75") (pin "2") (pinfunction "2_2") (pintype "passive"))
      (node (ref "C76") (pin "1") (pintype "passive"))
      (node (ref "D12") (pin "2") (pinfunction "K_2") (pintype "passive"))
      (node (ref "D15") (pin "2") (pinfunction "K_2") (pintype "passive"))
      (node (ref "D17") (pin "2") (pinfunction "K_2") (pintype "passive"))
      (node (ref "D20") (pin "2") (pinfunction "K_2") (pintype "passive"))
      (node (ref "D8") (pin "2") (pinfunction "K_2") (pintype "passive"))
      (node (ref "D9") (pin "2") (pinfunction "K_2") (pintype "passive"))
      (node (ref "EC3") (pin "1") (pinfunction "1_1") (pintype "passive"))
      (node (ref "L5") (pin "2") (pintype "passive"))
      (node (ref "R117") (pin "2") (pinfunction "2_2") (pintype "passive"))
      (node (ref "R118") (pin "2") (pinfunction "2_2") (pintype "passive"))
      (node (ref "R119") (pin "2") (pinfunction "2_2") (pintype "passive"))
      (node (ref "R120") (pin "2") (pinfunction "2_2") (pintype "passive"))
      (node (ref "RL1") (pin "2") (pinfunction "-_2") (pintype "passive"))
      (node (ref "RL2") (pin "2") (pinfunction "-_2") (pintype "passive"))
      (node (ref "RL3") (pin "2") (pinfunction "-_2") (pintype "passive"))
      (node (ref "RL4") (pin "2") (pinfunction "-_2") (pintype "passive"))
      (node (ref "U5") (pin "2") (pinfunction "Vi_2") (pintype "passive"))
      (node (ref "U5") (pin "7") (pinfunction "EN_7") (pintype "passive"))
    )
    (net (code "231") (name "VDD_EXT") (class "Default")
      (node (ref "C33") (pin "1") (pinfunction "1_1") (pintype "passive"))
      (node (ref "J15") (pin "28") (pinfunction "+1.8V_OUT_28") (pintype "passive"))
      (node (ref "R40") (pin "2") (pintype "passive"))
      (node (ref "R41") (pin "2") (pintype "passive"))
    )
    (net (code "232") (name "unconnected-(J2-Pad4)") (class "Default")
      (node (ref "J2") (pin "4") (pinfunction "4_4") (pintype "passive"))
    )
    (net (code "233") (name "unconnected-(J5-Pad3)") (class "Default")
      (node (ref "J5") (pin "3") (pinfunction "3_3") (pintype "passive"))
    )
    (net (code "234") (name "unconnected-(J6-Pad3)") (class "Default")
      (node (ref "J6") (pin "3") (pinfunction "3_3") (pintype "passive"))
    )
    (net (code "235") (name "unconnected-(J6-Pad4)") (class "Default")
      (node (ref "J6") (pin "4") (pinfunction "4_4") (pintype "passive"))
    )
    (net (code "236") (name "unconnected-(J10-Pad5)") (class "Default")
      (node (ref "J10") (pin "5") (pinfunction "5_5") (pintype "passive"))
    )
    (net (code "237") (name "unconnected-(J13-VPP-Pad5)") (class "Default")
      (node (ref "J13") (pin "5") (pinfunction "VPP_5") (pintype "passive"))
    )
    (net (code "238") (name "unconnected-(J15-NC-Pad3)") (class "Default")
      (node (ref "J15") (pin "3") (pinfunction "NC_3") (pintype "passive"))
    )
    (net (code "239") (name "unconnected-(J15-NC-Pad5)") (class "Default")
      (node (ref "J15") (pin "5") (pinfunction "NC_5") (pintype "passive"))
    )
    (net (code "240") (name "unconnected-(J15-NC-Pad6)") (class "Default")
      (node (ref "J15") (pin "6") (pinfunction "NC_6") (pintype "passive"))
    )
    (net (code "241") (name "unconnected-(J15-NC-Pad7)") (class "Default")
      (node (ref "J15") (pin "7") (pinfunction "NC_7") (pintype "passive"))
    )
    (net (code "242") (name "unconnected-(J15-NC-Pad30)") (class "Default")
      (node (ref "J15") (pin "30") (pinfunction "NC_30") (pintype "passive"))
    )
    (net (code "243") (name "unconnected-(J15-NC-Pad32)") (class "Default")
      (node (ref "J15") (pin "32") (pinfunction "NC_32") (pintype "passive"))
    )
    (net (code "244") (name "unconnected-(J15-NC-Pad45)") (class "Default")
      (node (ref "J15") (pin "45") (pinfunction "NC_45") (pintype "passive"))
    )
    (net (code "245") (name "unconnected-(J15-NC-Pad46)") (class "Default")
      (node (ref "J15") (pin "46") (pinfunction "NC_46") (pintype "passive"))
    )
    (net (code "246") (name "unconnected-(J15-NC-Pad47)") (class "Default")
      (node (ref "J15") (pin "47") (pinfunction "NC_47") (pintype "passive"))
    )
    (net (code "247") (name "unconnected-(J15-NC-Pad48)") (class "Default")
      (node (ref "J15") (pin "48") (pinfunction "NC_48") (pintype "passive"))
    )
    (net (code "248") (name "unconnected-(J15-NC-Pad49)") (class "Default")
      (node (ref "J15") (pin "49") (pinfunction "NC_49") (pintype "passive"))
    )
    (net (code "249") (name "unconnected-(J15-NC-Pad51)") (class "Default")
      (node (ref "J15") (pin "51") (pinfunction "NC_51") (pintype "passive"))
    )
    (net (code "250") (name "unconnected-(J15-UART_CTS-Pad23)") (class "Default")
      (node (ref "J15") (pin "23") (pinfunction "UART_CTS_23") (pintype "passive"))
    )
    (net (code "251") (name "unconnected-(J15-UART_DCD-Pad33)") (class "Default")
      (node (ref "J15") (pin "33") (pinfunction "UART_DCD_33") (pintype "passive"))
    )
    (net (code "252") (name "unconnected-(J15-UART_DSR-Pad16)") (class "Default")
      (node (ref "J15") (pin "16") (pinfunction "UART_DSR_16") (pintype "passive"))
    )
    (net (code "253") (name "unconnected-(J15-UART_DTR-Pad31)") (class "Default")
      (node (ref "J15") (pin "31") (pinfunction "UART_DTR_31") (pintype "passive"))
    )
    (net (code "254") (name "unconnected-(J15-UART_RI-Pad17)") (class "Default")
      (node (ref "J15") (pin "17") (pinfunction "UART_RI_17") (pintype "passive"))
    )
    (net (code "255") (name "unconnected-(J15-UART_RTS-Pad25)") (class "Default")
      (node (ref "J15") (pin "25") (pinfunction "UART_RTS_25") (pintype "passive"))
    )
    (net (code "256") (name "unconnected-(J15-USB_D+-Pad38)") (class "Default")
      (node (ref "J15") (pin "38") (pinfunction "USB_D+_38") (pintype "passive"))
    )
    (net (code "257") (name "unconnected-(J15-USB_D--Pad36)") (class "Default")
      (node (ref "J15") (pin "36") (pinfunction "USB_D-_36") (pintype "passive"))
    )
    (net (code "258") (name "unconnected-(J15-USIM_DET-Pad44)") (class "Default")
      (node (ref "J15") (pin "44") (pinfunction "USIM_DET_44") (pintype "passive"))
    )
    (net (code "259") (name "unconnected-(J15-WAKEUP_IN-Pad19)") (class "Default")
      (node (ref "J15") (pin "19") (pinfunction "WAKEUP_IN_19") (pintype "passive"))
    )
    (net (code "260") (name "unconnected-(J15-WAKEUP_OUT-Pad1)") (class "Default")
      (node (ref "J15") (pin "1") (pinfunction "WAKEUP_OUT_1") (pintype "passive"))
    )
    (net (code "261") (name "unconnected-(J15-W_DISABLE_N-Pad20)") (class "Default")
      (node (ref "J15") (pin "20") (pinfunction "W_DISABLE_N_20") (pintype "passive"))
    )
    (net (code "262") (name "unconnected-(MAKE1-Pad1)") (class "Default")
      (node (ref "MAKE1") (pin "1") (pinfunction "1_1") (pintype "passive"))
    )
    (net (code "263") (name "unconnected-(MARKE1-Pad1)") (class "Default")
      (node (ref "MARKE1") (pin "1") (pinfunction "1_1") (pintype "passive"))
    )
    (net (code "264") (name "unconnected-(MARKE2-Pad1)") (class "Default")
      (node (ref "MARKE2") (pin "1") (pinfunction "1_1") (pintype "passive"))
    )
    (net (code "265") (name "unconnected-(U1-JTAG_TDI-Pad3)") (class "Default")
      (node (ref "U1") (pin "3") (pinfunction "JTAG_TDI_3") (pintype "bidirectional"))
    )
    (net (code "266") (name "unconnected-(U1-JTAG_TRST-Pad5)") (class "Default")
      (node (ref "U1") (pin "5") (pinfunction "JTAG_TRST_5") (pintype "bidirectional"))
    )
    (net (code "267") (name "unconnected-(U1-P0[4]{slash}I2C_RX_SCK{slash}RD2{slash}T2_CAP0-Pad116)") (class "Default")
      (node (ref "U1") (pin "116") (pinfunction "P0[4]/I2C_RX_SCK/RD2/T2_CAP0_116") (pintype "bidirectional"))
    )
    (net (code "268") (name "unconnected-(U1-P0[5]{slash}I2S_RX_WS{slash}TD2{slash}T2CAP1-Pad115)") (class "Default")
      (node (ref "U1") (pin "115") (pinfunction "P0[5]/I2S_RX_WS/TD2/T2CAP1_115") (pintype "bidirectional"))
    )
    (net (code "269") (name "unconnected-(U1-P0[6]{slash}I2S_RX_SDA{slash}SSP1_SSEL{slash}T2_MAT0{slash}U1_RTS-Pad113)") (class "Default")
      (node (ref "U1") (pin "113") (pinfunction "P0[6]/I2S_RX_SDA/SSP1_SSEL/T2_MAT0/U1_RTS_113") (pintype "bidirectional"))
    )
    (net (code "270") (name "unconnected-(U1-P0[7]{slash}I2S_TX_SCK{slash}SSP1_SCK{slash}T2_MAT1{slash}RTC_EV0-Pad112)") (class "Default")
      (node (ref "U1") (pin "112") (pinfunction "P0[7]/I2S_TX_SCK/SSP1_SCK/T2_MAT1/RTC_EV0_112") (pintype "bidirectional"))
    )
    (net (code "271") (name "unconnected-(U1-P0[8]{slash}I2S_TX_WS{slash}SSP1_MISO{slash}T2_MAT2{slash}RTC_EV1-Pad111)") (class "Default")
      (node (ref "U1") (pin "111") (pinfunction "P0[8]/I2S_TX_WS/SSP1_MISO/T2_MAT2/RTC_EV1_111") (pintype "bidirectional"))
    )
    (net (code "272") (name "unconnected-(U1-P0[9]{slash}I2S_TX_SDA{slash}SSP1_MOSI{slash}T2_MAT3{slash}RTC_EV2-Pad109)") (class "Default")
      (node (ref "U1") (pin "109") (pinfunction "P0[9]/I2S_TX_SDA/SSP1_MOSI/T2_MAT3/RTC_EV2_109") (pintype "bidirectional"))
    )
    (net (code "273") (name "unconnected-(U1-P0[14]{slash}USB_HSTEN2{slash}SSP1_SSEL{slash}USB_CONNECT2-Pad48)") (class "Default")
      (node (ref "U1") (pin "48") (pinfunction "P0[14]/USB_HSTEN2/SSP1_SSEL/USB_CONNECT2_48") (pintype "bidirectional"))
    )
    (net (code "274") (name "unconnected-(U1-P0[19]{slash}U1_DSR{slash}SD_CLK{slash}I2C1_SDA-Pad85)") (class "Default")
      (node (ref "U1") (pin "85") (pinfunction "P0[19]/U1_DSR/SD_CLK/I2C1_SDA_85") (pintype "bidirectional"))
    )
    (net (code "275") (name "unconnected-(U1-P0[20]{slash}U1_DTR{slash}SD_CMD{slash}I2C1_SCL-Pad83)") (class "Default")
      (node (ref "U1") (pin "83") (pinfunction "P0[20]/U1_DTR/SD_CMD/I2C1_SCL_83") (pintype "bidirectional"))
    )
    (net (code "276") (name "unconnected-(U1-P0[23]{slash}AD0_IN0{slash}I2S_RX_SCK{slash}T3_CAP0-Pad13)") (class "Default")
      (node (ref "U1") (pin "13") (pinfunction "P0[23]/AD0_IN0/I2S_RX_SCK/T3_CAP0_13") (pintype "bidirectional"))
    )
    (net (code "277") (name "unconnected-(U1-P0[24]{slash}ADC0_IN1{slash}I2S_RX_WS{slash}T3_CAP1-Pad11)") (class "Default")
      (node (ref "U1") (pin "11") (pinfunction "P0[24]/ADC0_IN1/I2S_RX_WS/T3_CAP1_11") (pintype "bidirectional"))
    )
    (net (code "278") (name "unconnected-(U1-P0[28]{slash}I2C0_SCL{slash}USB_SCL1-Pad34)") (class "Default")
      (node (ref "U1") (pin "34") (pinfunction "P0[28]/I2C0_SCL/USB_SCL1_34") (pintype "bidirectional"))
    )
    (net (code "279") (name "unconnected-(U1-P0[29]{slash}USB_D+1{slash}EINT0-Pad42)") (class "Default")
      (node (ref "U1") (pin "42") (pinfunction "P0[29]/USB_D+1/EINT0_42") (pintype "bidirectional"))
    )
    (net (code "280") (name "unconnected-(U1-P0[30]{slash}USB_D-1{slash}EINT1-Pad43)") (class "Default")
      (node (ref "U1") (pin "43") (pinfunction "P0[30]/USB_D-1/EINT1_43") (pintype "bidirectional"))
    )
    (net (code "281") (name "unconnected-(U1-P1[9]{slash}ENET_RXD0{slash}T3_MAT0-Pad131)") (class "Default")
      (node (ref "U1") (pin "131") (pinfunction "P1[9]/ENET_RXD0/T3_MAT0_131") (pintype "bidirectional"))
    )
    (net (code "282") (name "unconnected-(U1-P1[10]{slash}ENET_RXD1{slash}T3_CAP0-Pad129)") (class "Default")
      (node (ref "U1") (pin "129") (pinfunction "P1[10]/ENET_RXD1/T3_CAP0_129") (pintype "bidirectional"))
    )
    (net (code "283") (name "unconnected-(U1-P1[14]{slash}ENET_RX_ER{slash}T2_CAP0-Pad128)") (class "Default")
      (node (ref "U1") (pin "128") (pinfunction "P1[14]/ENET_RX_ER/T2_CAP0_128") (pintype "bidirectional"))
    )
    (net (code "284") (name "unconnected-(U1-P1[15]{slash}ENET_RX_CLK{slash}I2C2_SDA-Pad126)") (class "Default")
      (node (ref "U1") (pin "126") (pinfunction "P1[15]/ENET_RX_CLK/I2C2_SDA_126") (pintype "bidirectional"))
    )
    (net (code "285") (name "unconnected-(U1-P1[16]{slash}ENET_MDC{slash}I2S_TX_MCLK-Pad125)") (class "Default")
      (node (ref "U1") (pin "125") (pinfunction "P1[16]/ENET_MDC/I2S_TX_MCLK_125") (pintype "bidirectional"))
    )
    (net (code "286") (name "unconnected-(U1-P1[17]{slash}ENET_MDIO{slash}I2S_RX_MCLK-Pad123)") (class "Default")
      (node (ref "U1") (pin "123") (pinfunction "P1[17]/ENET_MDIO/I2S_RX_MCLK_123") (pintype "bidirectional"))
    )
    (net (code "287") (name "unconnected-(U1-P1[21]{slash}USB_TX_DM1{slash}PWM1[3]{slash}SSP0_SSEL{slash}MC_ABORT-Pad50)") (class "Default")
      (node (ref "U1") (pin "50") (pinfunction "P1[21]/USB_TX_DM1/PWM1[3]/SSP0_SSEL/MC_ABORT_50") (pintype "bidirectional"))
    )
    (net (code "288") (name "unconnected-(U1-P1[25]{slash}USB_LS1{slash}USB_HSTEN1{slash}T1_MAT1{slash}MC_1A{slash}CLKOUT-Pad56)") (class "Default")
      (node (ref "U1") (pin "56") (pinfunction "P1[25]/USB_LS1/USB_HSTEN1/T1_MAT1/MC_1A/CLKOUT_56") (pintype "bidirectional"))
    )
    (net (code "289") (name "unconnected-(U1-P1[27]{slash}USB_INT1{slash}USB_OVRCR1{slash}T0_CAP1{slash}CLKOUT-Pad61)") (class "Default")
      (node (ref "U1") (pin "61") (pinfunction "P1[27]/USB_INT1/USB_OVRCR1/T0_CAP1/CLKOUT_61") (pintype "bidirectional"))
    )
    (net (code "290") (name "unconnected-(U1-P1[30]{slash}USB_PWRD2{slash}USB_VBUS{slash}ADC0_IN4{slash}I2C0_SDA{slash}U3_OE-Pad30)") (class "Default")
      (node (ref "U1") (pin "30") (pinfunction "P1[30]/USB_PWRD2/USB_VBUS/ADC0_IN4/I2C0_SDA/U3_OE_30") (pintype "bidirectional"))
    )
    (net (code "291") (name "unconnected-(U1-P1[31]{slash}USB_OVRCR2{slash}SSP1_SCK{slash}ADC0_IN5{slash}I2C0_SCL-Pad28)") (class "Default")
      (node (ref "U1") (pin "28") (pinfunction "P1[31]/USB_OVRCR2/SSP1_SCK/ADC0_IN5/I2C0_SCL_28") (pintype "bidirectional"))
    )
    (net (code "292") (name "unconnected-(U1-P2[2]{slash}PWM1[3]{slash}U1_CTS{slash}T2_MAT3{slash}TRACEDATA[3]-Pad105)") (class "Default")
      (node (ref "U1") (pin "105") (pinfunction "P2[2]/PWM1[3]/U1_CTS/T2_MAT3/TRACEDATA[3]_105") (pintype "bidirectional"))
    )
    (net (code "293") (name "unconnected-(U1-P2[3]{slash}PWM1[4]{slash}U1_DCD{slash}T2_MAT2{slash}TRACEDATA[2]-Pad100)") (class "Default")
      (node (ref "U1") (pin "100") (pinfunction "P2[3]/PWM1[4]/U1_DCD/T2_MAT2/TRACEDATA[2]_100") (pintype "bidirectional"))
    )
    (net (code "294") (name "unconnected-(U1-P2[4]{slash}PWM1[5]{slash}U1_DSR{slash}T2_MAT1{slash}TRACEDATA[1]-Pad99)") (class "Default")
      (node (ref "U1") (pin "99") (pinfunction "P2[4]/PWM1[5]/U1_DSR/T2_MAT1/TRACEDATA[1]_99") (pintype "bidirectional"))
    )
    (net (code "295") (name "unconnected-(U1-P2[5]{slash}PWM1[6]{slash}U1_DTR{slash}T2_MAT0{slash}TRACEDATA[0]-Pad97)") (class "Default")
      (node (ref "U1") (pin "97") (pinfunction "P2[5]/PWM1[6]/U1_DTR/T2_MAT0/TRACEDATA[0]_97") (pintype "bidirectional"))
    )
    (net (code "296") (name "unconnected-(U1-P2[9]{slash}USB_CONNECT1{slash}U2_RXD{slash}U4_RXD{slash}ENET_MDIO-Pad92)") (class "Default")
      (node (ref "U1") (pin "92") (pinfunction "P2[9]/USB_CONNECT1/U2_RXD/U4_RXD/ENET_MDIO_92") (pintype "bidirectional"))
    )
    (net (code "297") (name "unconnected-(U1-P2[11]{slash}EINT1{slash}SD_DAT[1]{slash}I2S_TX_SCK-Pad75)") (class "Default")
      (node (ref "U1") (pin "75") (pinfunction "P2[11]/EINT1/SD_DAT[1]/I2S_TX_SCK_75") (pintype "bidirectional"))
    )
    (net (code "298") (name "unconnected-(U1-P2[13]{slash}EINT3{slash}SD_DAT[3]{slash}I2S_TX_SDA-Pad71)") (class "Default")
      (node (ref "U1") (pin "71") (pinfunction "P2[13]/EINT3/SD_DAT[3]/I2S_TX_SDA_71") (pintype "bidirectional"))
    )
    (net (code "299") (name "unconnected-(U1-P3[0]{slash}EMC_D[0]-Pad137)") (class "Default")
      (node (ref "U1") (pin "137") (pinfunction "P3[0]/EMC_D[0]_137") (pintype "bidirectional"))
    )
    (net (code "300") (name "unconnected-(U1-P3[1]{slash}EMC_D[1]-Pad140)") (class "Default")
      (node (ref "U1") (pin "140") (pinfunction "P3[1]/EMC_D[1]_140") (pintype "bidirectional"))
    )
    (net (code "301") (name "unconnected-(U1-P3[2]{slash}EMC_D[2]-Pad144)") (class "Default")
      (node (ref "U1") (pin "144") (pinfunction "P3[2]/EMC_D[2]_144") (pintype "bidirectional"))
    )
    (net (code "302") (name "unconnected-(U1-P3[3]{slash}EMC_D[3]-Pad2)") (class "Default")
      (node (ref "U1") (pin "2") (pinfunction "P3[3]/EMC_D[3]_2") (pintype "bidirectional"))
    )
    (net (code "303") (name "unconnected-(U1-P3[4]{slash}EMC_D[4]-Pad9)") (class "Default")
      (node (ref "U1") (pin "9") (pinfunction "P3[4]/EMC_D[4]_9") (pintype "bidirectional"))
    )
    (net (code "304") (name "unconnected-(U1-P3[5]{slash}EMC_D[5]-Pad12)") (class "Default")
      (node (ref "U1") (pin "12") (pinfunction "P3[5]/EMC_D[5]_12") (pintype "bidirectional"))
    )
    (net (code "305") (name "unconnected-(U1-P3[6]{slash}EMC_D[6]-Pad16)") (class "Default")
      (node (ref "U1") (pin "16") (pinfunction "P3[6]/EMC_D[6]_16") (pintype "bidirectional"))
    )
    (net (code "306") (name "unconnected-(U1-P3[7]{slash}EMC_D[7]-Pad19)") (class "Default")
      (node (ref "U1") (pin "19") (pinfunction "P3[7]/EMC_D[7]_19") (pintype "bidirectional"))
    )
    (net (code "307") (name "unconnected-(U1-P3[23]{slash}EMC_D[23]{slash}PWM1_CAP0{slash}T0_CAP0-Pad45)") (class "Default")
      (node (ref "U1") (pin "45") (pinfunction "P3[23]/EMC_D[23]/PWM1_CAP0/T0_CAP0_45") (pintype "bidirectional"))
    )
    (net (code "308") (name "unconnected-(U1-P3[24]{slash}EMC_D[24]{slash}PWM1[1]{slash}T0_CAP1-Pad40)") (class "Default")
      (node (ref "U1") (pin "40") (pinfunction "P3[24]/EMC_D[24]/PWM1[1]/T0_CAP1_40") (pintype "bidirectional"))
    )
    (net (code "309") (name "unconnected-(U1-P4[0]{slash}EMC_A[0]-Pad52)") (class "Default")
      (node (ref "U1") (pin "52") (pinfunction "P4[0]/EMC_A[0]_52") (pintype "bidirectional"))
    )
    (net (code "310") (name "unconnected-(U1-P4[1]{slash}EMC_A[1]-Pad55)") (class "Default")
      (node (ref "U1") (pin "55") (pinfunction "P4[1]/EMC_A[1]_55") (pintype "bidirectional"))
    )
    (net (code "311") (name "unconnected-(U1-P4[2]{slash}EMC_A[2]-Pad58)") (class "Default")
      (node (ref "U1") (pin "58") (pinfunction "P4[2]/EMC_A[2]_58") (pintype "bidirectional"))
    )
    (net (code "312") (name "unconnected-(U1-P4[5]{slash}EMC_A[5]-Pad74)") (class "Default")
      (node (ref "U1") (pin "74") (pinfunction "P4[5]/EMC_A[5]_74") (pintype "bidirectional"))
    )
    (net (code "313") (name "unconnected-(U1-P4[6]{slash}EMC_A[6]-Pad78)") (class "Default")
      (node (ref "U1") (pin "78") (pinfunction "P4[6]/EMC_A[6]_78") (pintype "bidirectional"))
    )
    (net (code "314") (name "unconnected-(U1-P4[7]{slash}EMC_A[7]-Pad84)") (class "Default")
      (node (ref "U1") (pin "84") (pinfunction "P4[7]/EMC_A[7]_84") (pintype "bidirectional"))
    )
    (net (code "315") (name "unconnected-(U1-P4[8]{slash}EMC_A[8]-Pad88)") (class "Default")
      (node (ref "U1") (pin "88") (pinfunction "P4[8]/EMC_A[8]_88") (pintype "bidirectional"))
    )
    (net (code "316") (name "unconnected-(U1-P4[9]{slash}EMC_A[9]-Pad91)") (class "Default")
      (node (ref "U1") (pin "91") (pinfunction "P4[9]/EMC_A[9]_91") (pintype "bidirectional"))
    )
    (net (code "317") (name "unconnected-(U1-P4[11]{slash}EMC_A[11]-Pad101)") (class "Default")
      (node (ref "U1") (pin "101") (pinfunction "P4[11]/EMC_A[11]_101") (pintype "bidirectional"))
    )
    (net (code "318") (name "unconnected-(U1-P4[12]{slash}EMC_A[12]-Pad104)") (class "Default")
      (node (ref "U1") (pin "104") (pinfunction "P4[12]/EMC_A[12]_104") (pintype "bidirectional"))
    )
    (net (code "319") (name "unconnected-(U1-P4[13]{slash}EMC_A[13]-Pad108)") (class "Default")
      (node (ref "U1") (pin "108") (pinfunction "P4[13]/EMC_A[13]_108") (pintype "bidirectional"))
    )
    (net (code "320") (name "unconnected-(U1-P4[14]{slash}EMC_A[14]-Pad110)") (class "Default")
      (node (ref "U1") (pin "110") (pinfunction "P4[14]/EMC_A[14]_110") (pintype "bidirectional"))
    )
    (net (code "321") (name "unconnected-(U1-P4[24]{slash}EMC_OE-Pad127)") (class "Default")
      (node (ref "U1") (pin "127") (pinfunction "P4[24]/EMC_OE_127") (pintype "bidirectional"))
    )
    (net (code "322") (name "unconnected-(U1-P4[30]{slash}EMC_CS0-Pad130)") (class "Default")
      (node (ref "U1") (pin "130") (pinfunction "P4[30]/EMC_CS0_130") (pintype "bidirectional"))
    )
    (net (code "323") (name "unconnected-(U1-P4[31]{slash}EMC_CS1-Pad134)") (class "Default")
      (node (ref "U1") (pin "134") (pinfunction "P4[31]/EMC_CS1_134") (pintype "bidirectional"))
    )
    (net (code "324") (name "unconnected-(U1-P5[1]{slash}EMC_BLS3{slash}U3_RXD{slash}T2_MAT1{slash}I2C2_SCL-Pad21)") (class "Default")
      (node (ref "U1") (pin "21") (pinfunction "P5[1]/EMC_BLS3/U3_RXD/T2_MAT1/I2C2_SCL_21") (pintype "bidirectional"))
    )
    (net (code "325") (name "unconnected-(U1-P5[2]{slash}T3_MAT2{slash}I2C0{slash}SDA-Pad81)") (class "Default")
      (node (ref "U1") (pin "81") (pinfunction "P5[2]/T3_MAT2/I2C0/SDA_81") (pintype "bidirectional"))
    )
    (net (code "326") (name "unconnected-(U1-RSTOUT-Pad20)") (class "Default")
      (node (ref "U1") (pin "20") (pinfunction "RSTOUT_20") (pintype "bidirectional"))
    )
    (net (code "327") (name "unconnected-(U1-RTC_ALARM-Pad26)") (class "Default")
      (node (ref "U1") (pin "26") (pinfunction "RTC_ALARM_26") (pintype "bidirectional"))
    )
    (net (code "328") (name "unconnected-(U5-SS-Pad8)") (class "Default")
      (node (ref "U5") (pin "8") (pinfunction "SS_8") (pintype "passive"))
    )
    (net (code "329") (name "unconnected-(U6-~{PFO}-Pad5)") (class "Default")
      (node (ref "U6") (pin "5") (pinfunction "~{PFO}_5") (pintype "passive+no_connect"))
    )
    (net (code "330") (name "unconnected-(U9A-DNC-Pad7)") (class "Default")
      (node (ref "U9") (pin "7") (pinfunction "DNC_7") (pintype "bidirectional"))
    )
    (net (code "331") (name "unconnected-(U9B-VBG-Pad18)") (class "Default")
      (node (ref "U9") (pin "18") (pinfunction "VBG_18") (pintype "output"))
    )
    (net (code "332") (name "unconnected-(U12-NC-Pad4)") (class "Default")
      (node (ref "U12") (pin "4") (pinfunction "NC_4") (pintype "passive"))
    )
    (net (code "333") (name "unconnected-(U12-NC-Pad5)") (class "Default")
      (node (ref "U12") (pin "5") (pinfunction "NC_5") (pintype "passive"))
    )
    (net (code "334") (name "unconnected-(U16-R2IN-Pad8)") (class "Default")
      (node (ref "U16") (pin "8") (pinfunction "R2IN_8") (pintype "passive"))
    )
    (net (code "335") (name "unconnected-(U16-R2OUT-Pad9)") (class "Default")
      (node (ref "U16") (pin "9") (pinfunction "R2OUT_9") (pintype "passive"))
    )
    (net (code "336") (name "unconnected-(U16-T2IN-Pad10)") (class "Default")
      (node (ref "U16") (pin "10") (pinfunction "T2IN_10") (pintype "passive"))
    )
    (net (code "337") (name "unconnected-(U16-T2OUT-Pad7)") (class "Default")
      (node (ref "U16") (pin "7") (pinfunction "T2OUT_7") (pintype "passive"))
    )
    (net (code "338") (name "unconnected-(U17-A2-Pad4)") (class "Default")
      (node (ref "U17") (pin "4") (pinfunction "A2_4") (pintype "passive"))
    )
    (net (code "339") (name "unconnected-(U17-A4-Pad6)") (class "Default")
      (node (ref "U17") (pin "6") (pinfunction "A4_6") (pintype "passive"))
    )
    (net (code "340") (name "unconnected-(U17-A5-Pad7)") (class "Default")
      (node (ref "U17") (pin "7") (pinfunction "A5_7") (pintype "passive"))
    )
    (net (code "341") (name "unconnected-(U17-A7-Pad9)") (class "Default")
      (node (ref "U17") (pin "9") (pinfunction "A7_9") (pintype "passive"))
    )
    (net (code "342") (name "unconnected-(U17-B2-Pad16)") (class "Default")
      (node (ref "U17") (pin "16") (pinfunction "B2_16") (pintype "passive"))
    )
    (net (code "343") (name "unconnected-(U17-B4-Pad14)") (class "Default")
      (node (ref "U17") (pin "14") (pinfunction "B4_14") (pintype "passive"))
    )
    (net (code "344") (name "unconnected-(U17-B5-Pad13)") (class "Default")
      (node (ref "U17") (pin "13") (pinfunction "B5_13") (pintype "passive"))
    )
    (net (code "345") (name "unconnected-(U17-B7-Pad11)") (class "Default")
      (node (ref "U17") (pin "11") (pinfunction "B7_11") (pintype "passive"))
    )
  )
)
